# Full.net
KiCad netlist of a schematic drawn in EAGLE
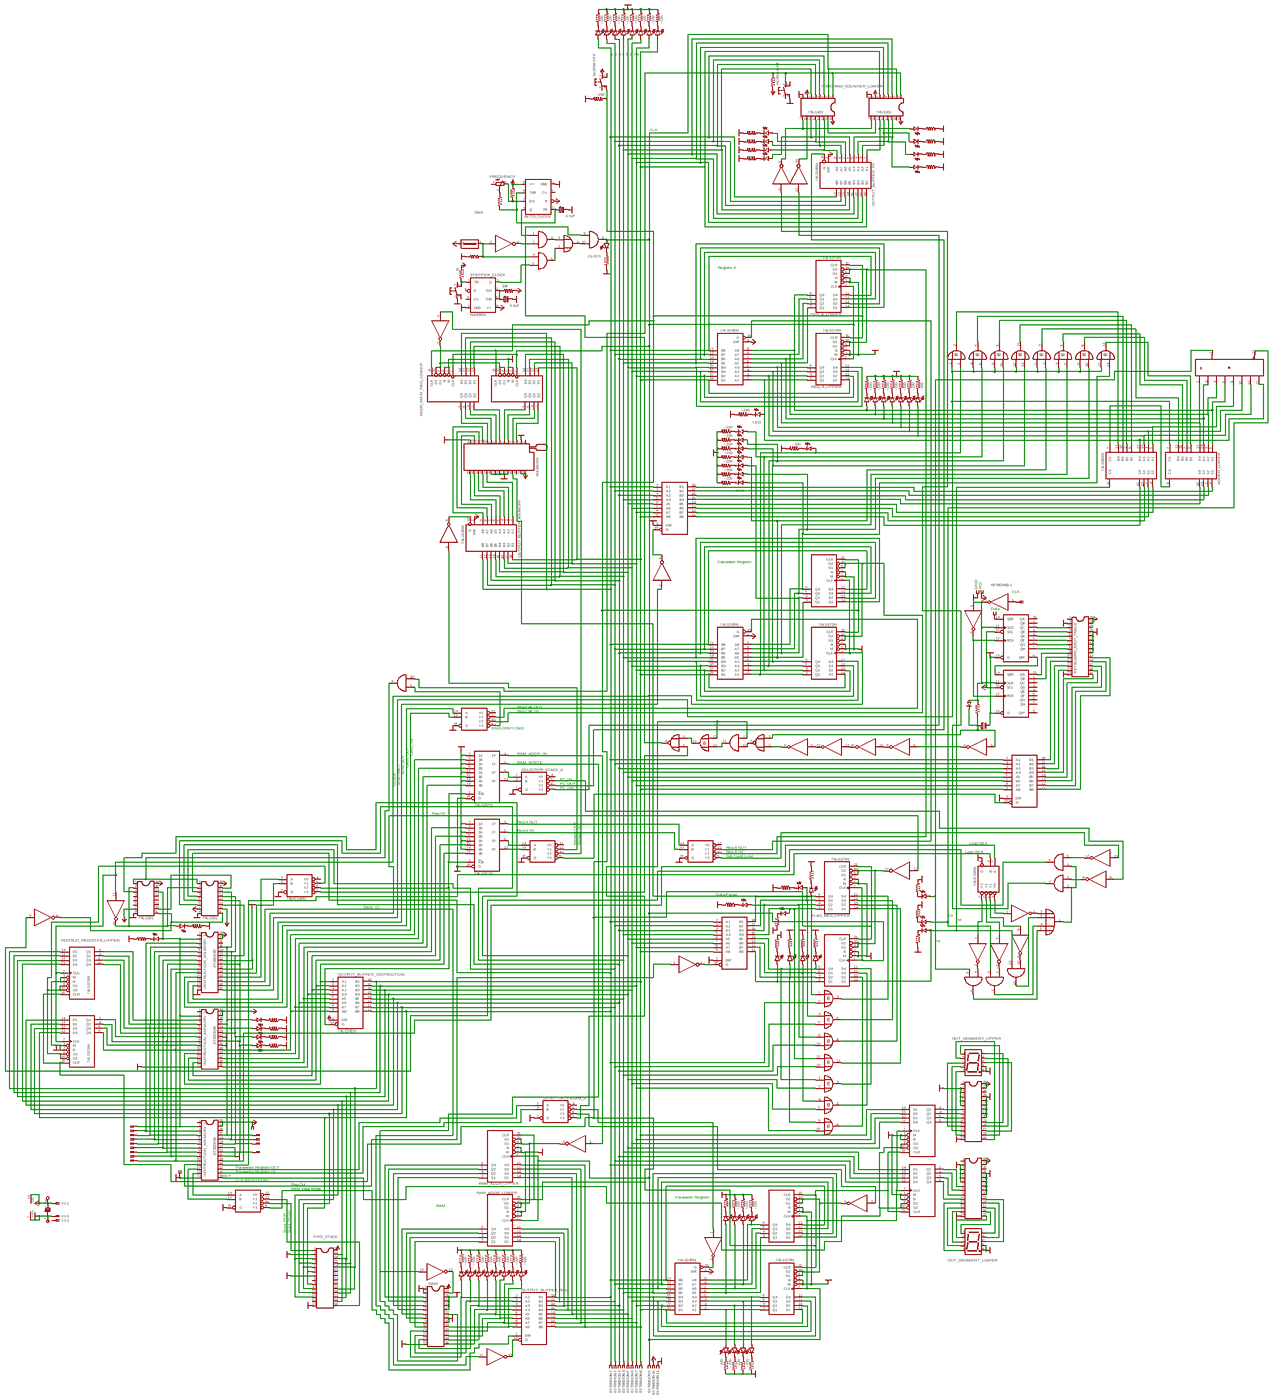
[diagram p0: schematic, sheet 1, overview]
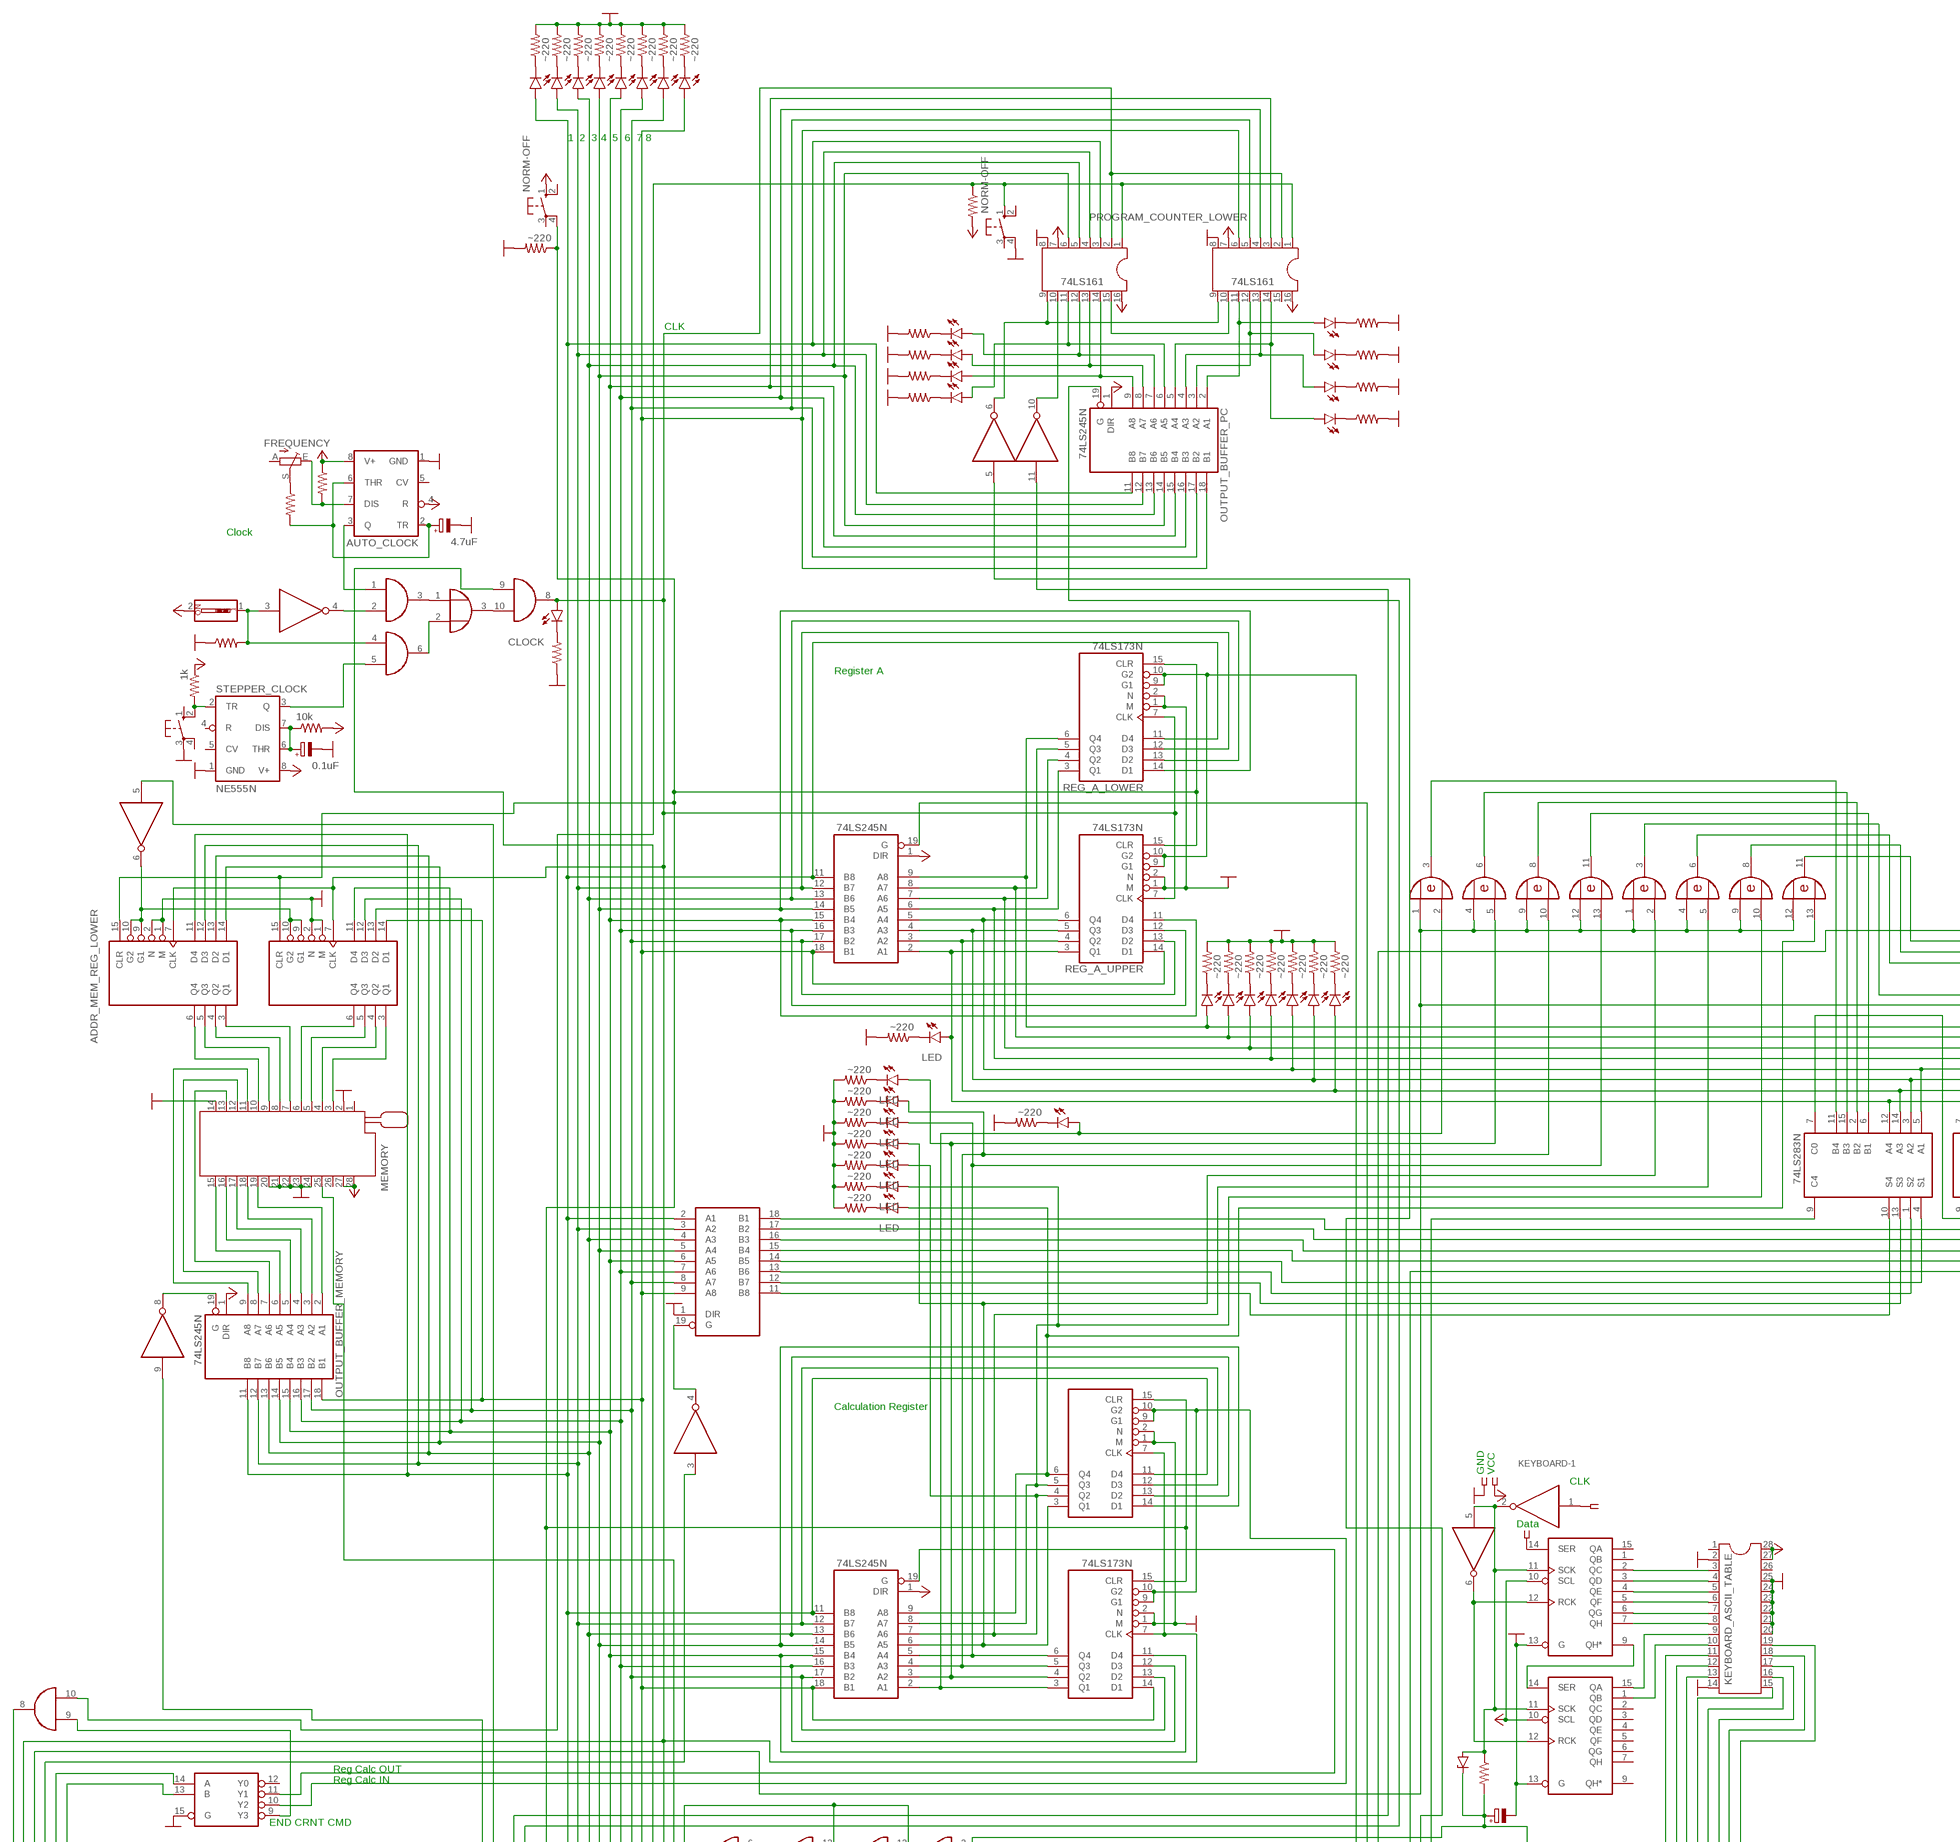
[diagram p1: schematic, sheet 1, part 1 of 4]
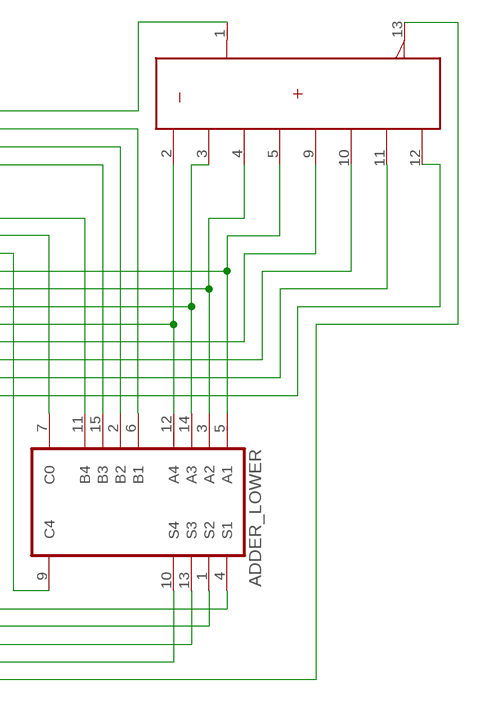
[diagram p2: schematic, sheet 1, part 2 of 4]
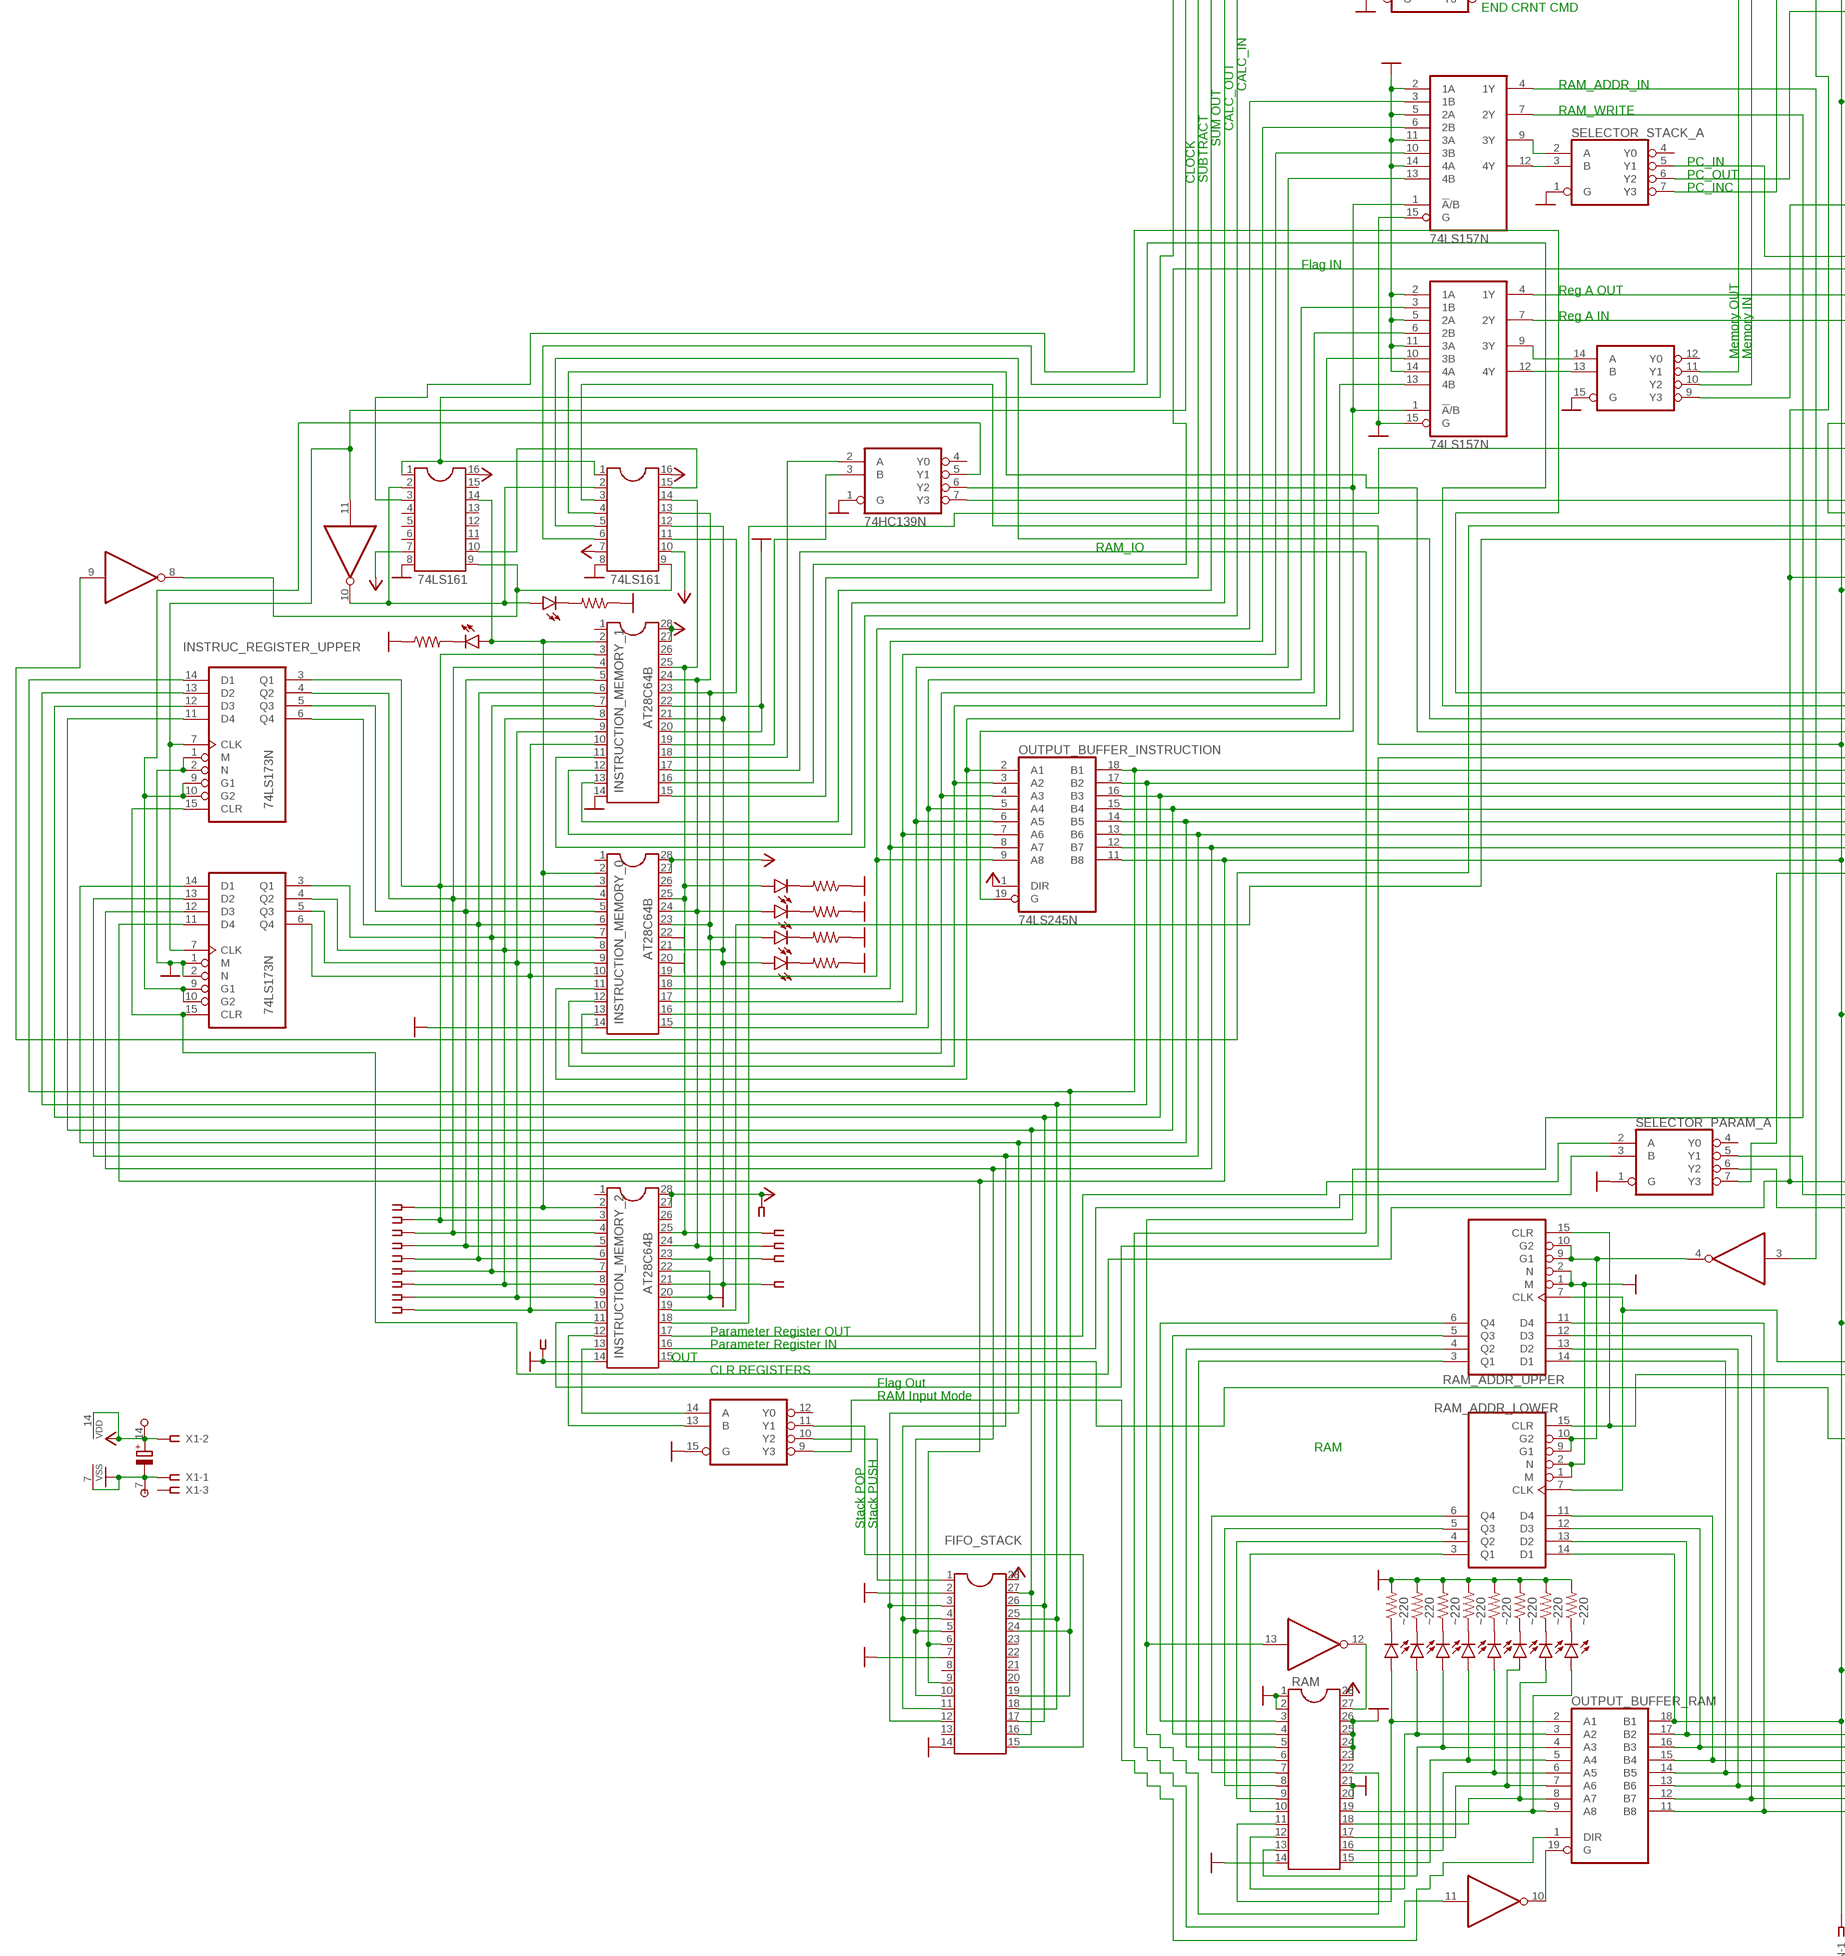
[diagram p3: schematic, sheet 1, part 3 of 4]
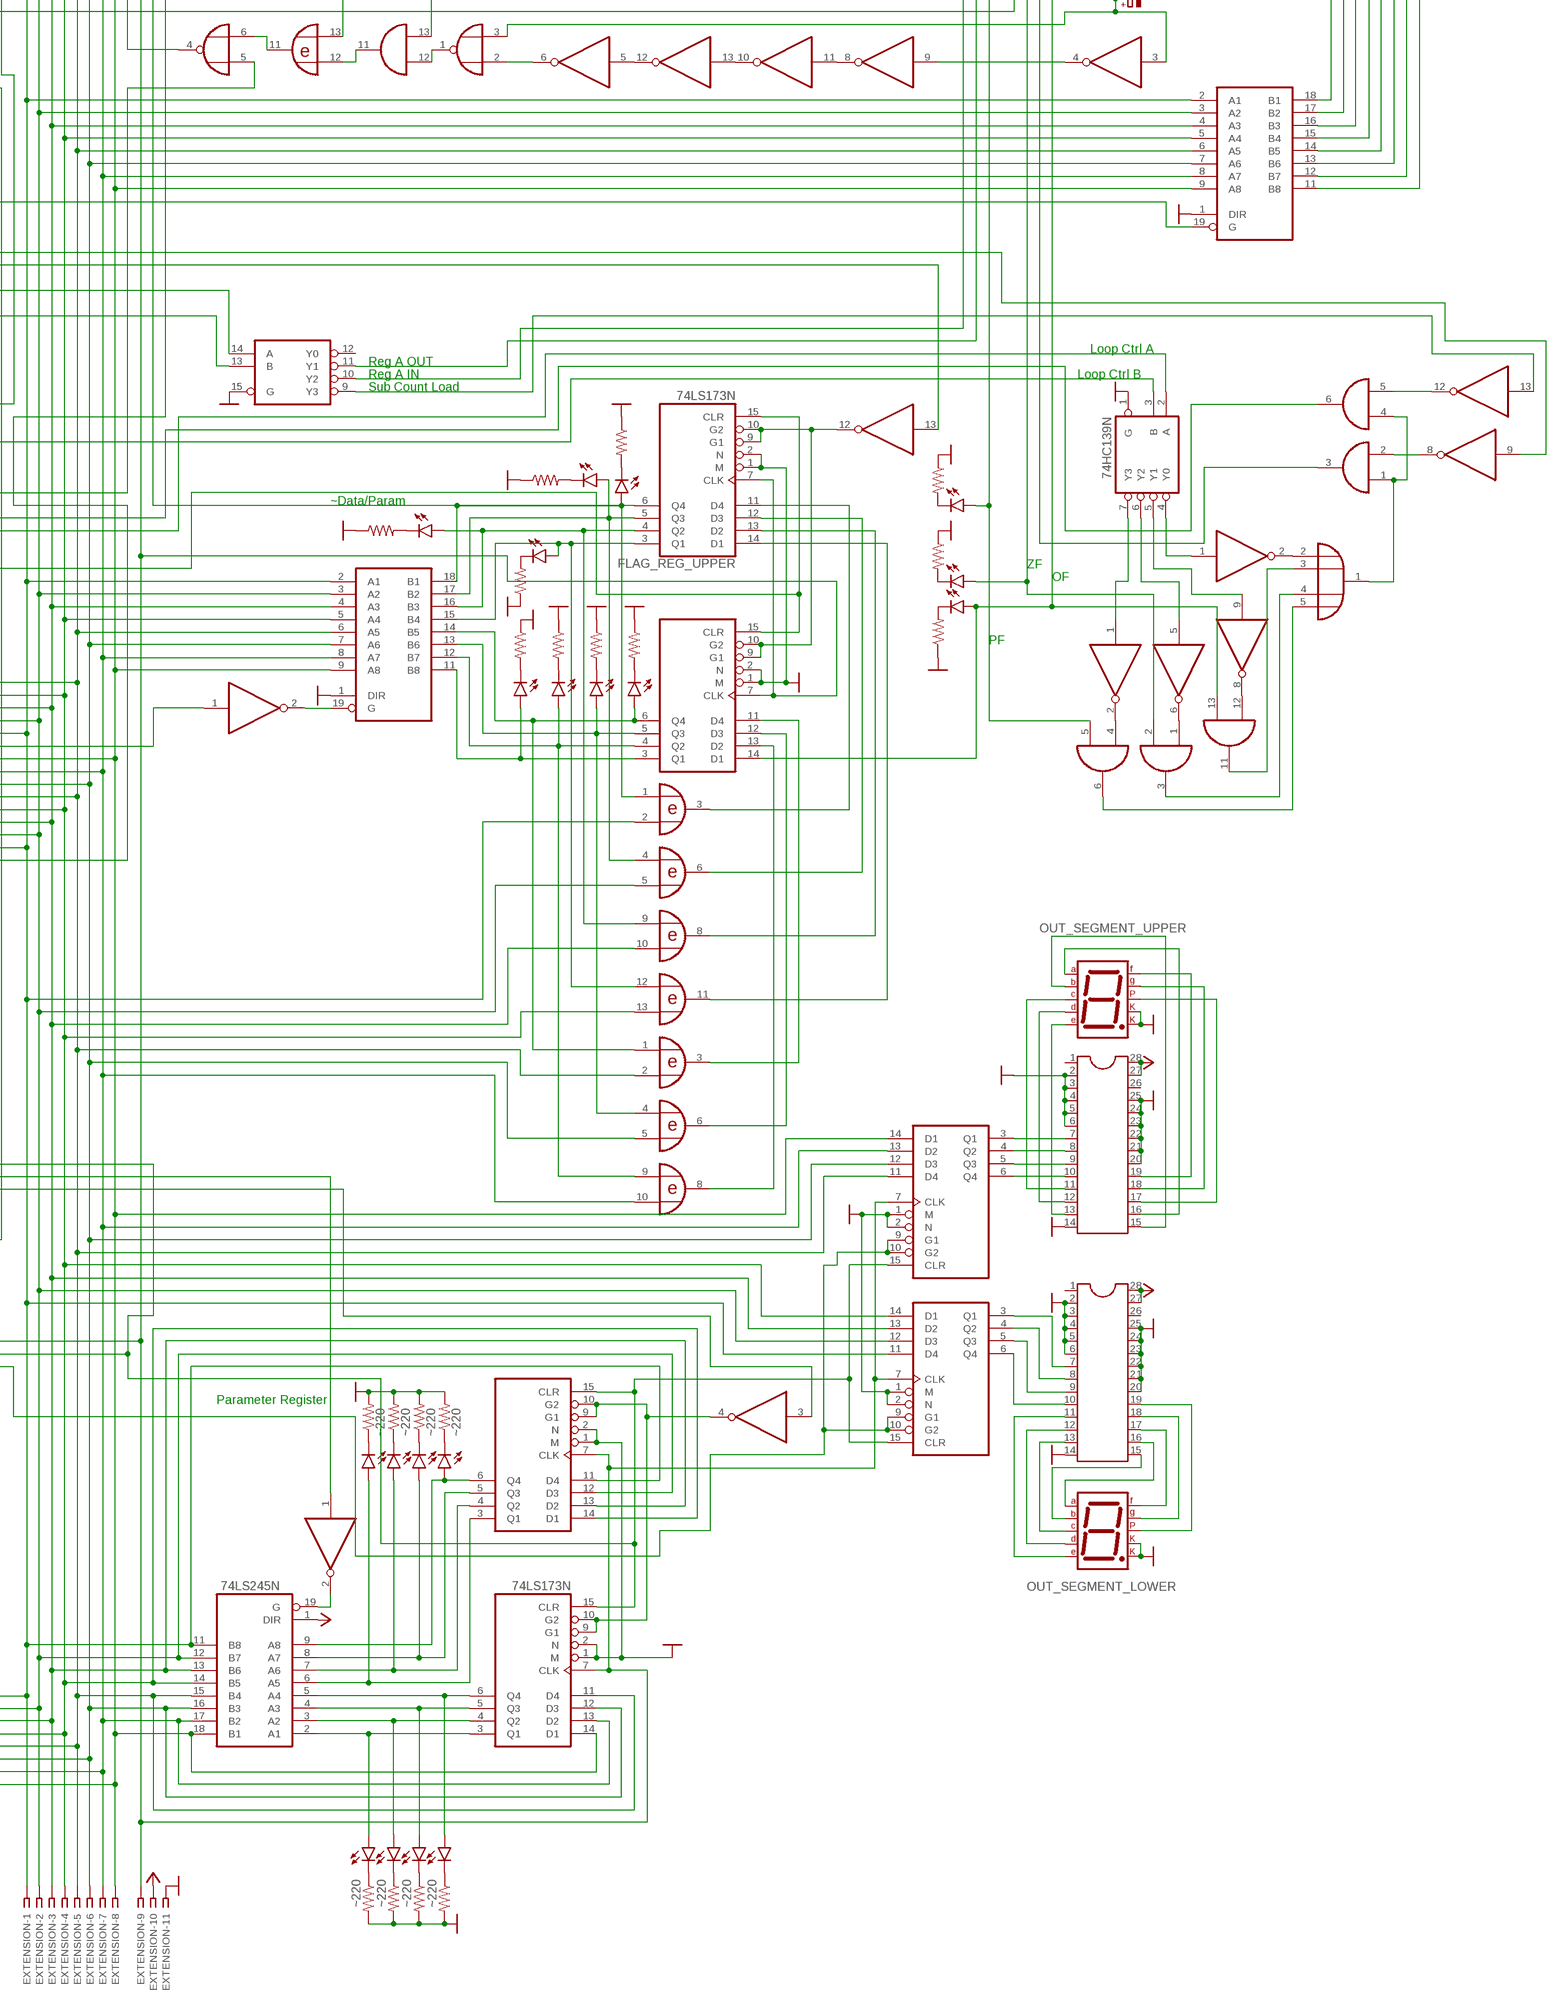
[diagram p4: schematic, sheet 1, part 4 of 4]

(export (version "E")
  (design (tool "Eeschema 10.0.6"))
  (components
    (comp (ref "4_INP_OR_GATE")
      (value "4072N")
      (footprint "eagle-import:DIL14")
      (libsource (lib "eagle-import") (part "4072N"))
    )
    (comp (ref "ADDER_LOWER")
      (value "74LS283N")
      (footprint "eagle-import:DIL16")
      (libsource (lib "eagle-import") (part "74283NLS"))
    )
    (comp (ref "ADDER_UPPER")
      (value "74LS283N")
      (footprint "eagle-import:DIL16")
      (libsource (lib "eagle-import") (part "74283NLS"))
    )
    (comp (ref "ADDR_MEM_REG_LOWER")
      (value "74LS173N")
      (footprint "eagle-import:DIL16")
      (libsource (lib "eagle-import") (part "74173NLS"))
    )
    (comp (ref "ADDR_MEM_REG_UPPER")
      (value "74LS173N")
      (footprint "eagle-import:DIL16")
      (libsource (lib "eagle-import") (part "74173NLS"))
    )
    (comp (ref "AND_GATE3_")
      (value "74LS08N")
      (footprint "eagle-import:DIL14")
      (libsource (lib "eagle-import") (part "7408NLS"))
    )
    (comp (ref "AND_GATE4_")
      (value "74LS08N")
      (footprint "eagle-import:DIL14")
      (libsource (lib "eagle-import") (part "7408NLS"))
    )
    (comp (ref "AND_GATE_")
      (value "74LS08N")
      (footprint "eagle-import:DIL14")
      (libsource (lib "eagle-import") (part "7408NLS"))
    )
    (comp (ref "AUTO_CLOCK")
      (value "NE555N")
      (footprint "eagle-import:DIL08")
      (libsource (lib "eagle-import") (part "555NNE"))
    )
    (comp (ref "C1")
      (value "4.7uF")
      (footprint "eagle-import:E2-5")
      (libsource (lib "eagle-import") (part "CPOL-EUE2-5"))
    )
    (comp (ref "C2")
      (value "0.1uF")
      (footprint "eagle-import:E2-5")
      (libsource (lib "eagle-import") (part "CPOL-EUE2-5"))
    )
    (comp (ref "C3")
      (value "0.1uF")
      (footprint "eagle-import:E2-5")
      (libsource (lib "eagle-import") (part "CPOL-EUE2-5"))
    )
    (comp (ref "C4")
      (value "0.1uF")
      (footprint "eagle-import:E2-5")
      (libsource (lib "eagle-import") (part "CPOL-EUE2-5"))
    )
    (comp (ref "CLK_MODE")
      (value "SWITCH")
      (footprint "eagle-import:EDG-01")
      (libsource (lib "eagle-import") (part "SW_DIP-1"))
    )
    (comp (ref "CLK_TRIGGER")
      (value "SWITCH")
      (footprint "eagle-import:B3F-10XX")
      (fields (field (name "MPN") "B3F-1000"))
      (libsource (lib "eagle-import") (part "10-XX"))
    )
    (comp (ref "CLOCK")
      (value "Yellow")
      (footprint "eagle-import:LED5MM")
      (libsource (lib "eagle-import") (part "LED5MM"))
    )
    (comp (ref "D1")
      (value "1N4728")
      (footprint "eagle-import:DO41Z10")
      (libsource (lib "eagle-import") (part "1N4728"))
    )
    (comp (ref "DATABUS_1")
      (value "LED")
      (footprint "eagle-import:LED5MM")
      (libsource (lib "eagle-import") (part "LED5MM"))
    )
    (comp (ref "DATABUS_2")
      (value "LED")
      (footprint "eagle-import:LED5MM")
      (libsource (lib "eagle-import") (part "LED5MM"))
    )
    (comp (ref "DATABUS_3")
      (value "LED")
      (footprint "eagle-import:LED5MM")
      (libsource (lib "eagle-import") (part "LED5MM"))
    )
    (comp (ref "DATABUS_4")
      (value "LED")
      (footprint "eagle-import:LED5MM")
      (libsource (lib "eagle-import") (part "LED5MM"))
    )
    (comp (ref "DATABUS_5")
      (value "LED")
      (footprint "eagle-import:LED5MM")
      (libsource (lib "eagle-import") (part "LED5MM"))
    )
    (comp (ref "DATABUS_6")
      (value "LED")
      (footprint "eagle-import:LED5MM")
      (libsource (lib "eagle-import") (part "LED5MM"))
    )
    (comp (ref "DATABUS_7")
      (value "LED")
      (footprint "eagle-import:LED5MM")
      (libsource (lib "eagle-import") (part "LED5MM"))
    )
    (comp (ref "DATABUS_8")
      (value "LED")
      (footprint "eagle-import:LED5MM")
      (libsource (lib "eagle-import") (part "LED5MM"))
    )
    (comp (ref "EXTENSION")
      (value "SSW-111-02-G-S")
      (footprint "eagle-import:SSW-111-02-G-S")
      (fields (field (name "MF") "Samtec Inc."))
      (libsource (lib "eagle-import") (part "SSW-111-02-G-S"))
    )
    (comp (ref "FIFO_STACK")
      (value "71256SA15TPG")
      (footprint "eagle-import:DIL28-3")
      (libsource (lib "eagle-import") (part "DIL28-3"))
    )
    (comp (ref "FLAG_1")
      (value "LED")
      (footprint "eagle-import:LED5MM")
      (libsource (lib "eagle-import") (part "LED5MM"))
    )
    (comp (ref "FLAG_2")
      (value "LED")
      (footprint "eagle-import:LED5MM")
      (libsource (lib "eagle-import") (part "LED5MM"))
    )
    (comp (ref "FLAG_3")
      (value "LED")
      (footprint "eagle-import:LED5MM")
      (libsource (lib "eagle-import") (part "LED5MM"))
    )
    (comp (ref "FLAG_4")
      (value "LED")
      (footprint "eagle-import:LED5MM")
      (libsource (lib "eagle-import") (part "LED5MM"))
    )
    (comp (ref "FLAG_5")
      (value "LED")
      (footprint "eagle-import:LED5MM")
      (libsource (lib "eagle-import") (part "LED5MM"))
    )
    (comp (ref "FLAG_6")
      (value "LED")
      (footprint "eagle-import:LED5MM")
      (libsource (lib "eagle-import") (part "LED5MM"))
    )
    (comp (ref "FLAG_7")
      (value "LED")
      (footprint "eagle-import:LED5MM")
      (libsource (lib "eagle-import") (part "LED5MM"))
    )
    (comp (ref "FLAG_8")
      (value "LED")
      (footprint "eagle-import:LED5MM")
      (libsource (lib "eagle-import") (part "LED5MM"))
    )
    (comp (ref "FLAG_REG_LOWER")
      (value "74LS173N")
      (footprint "eagle-import:DIL16")
      (libsource (lib "eagle-import") (part "74173NLS"))
    )
    (comp (ref "FLAG_REG_UPPER")
      (value "74LS173N")
      (footprint "eagle-import:DIL16")
      (libsource (lib "eagle-import") (part "74173NLS"))
    )
    (comp (ref "FREQUENCY")
      (value "100k")
      (footprint "eagle-import:RJ9W")
      (libsource (lib "eagle-import") (part "TRIM_EU-RJ9W"))
    )
    (comp (ref "INSTRUCTIONS_EXTENSION")
      (value "SSW-115-02-G-S")
      (footprint "eagle-import:SSW-115-02-G-S")
      (fields (field (name "MF") "Samtec Inc."))
      (libsource (lib "eagle-import") (part "SSW-115-02-G-S"))
    )
    (comp (ref "INSTRUCTION_MEMORY_0")
      (value "AT28C64B")
      (footprint "eagle-import:DIL28-6")
      (libsource (lib "eagle-import") (part "DIL28"))
    )
    (comp (ref "INSTRUCTION_MEMORY_1")
      (value "AT28C64B")
      (footprint "eagle-import:DIL28-6")
      (libsource (lib "eagle-import") (part "DIL28"))
    )
    (comp (ref "INSTRUCTION_MEMORY_2")
      (value "AT28C64B")
      (footprint "eagle-import:DIL28-6")
      (libsource (lib "eagle-import") (part "DIL28"))
    )
    (comp (ref "INSTRUC_REGISTER_LOWER")
      (value "74LS173N")
      (footprint "eagle-import:DIL16")
      (libsource (lib "eagle-import") (part "74173NLS"))
    )
    (comp (ref "INSTRUC_REGISTER_UPPER")
      (value "74LS173N")
      (footprint "eagle-import:DIL16")
      (libsource (lib "eagle-import") (part "74173NLS"))
    )
    (comp (ref "INVERTED_CLK_LED")
      (value "LED")
      (footprint "eagle-import:LED5MM")
      (libsource (lib "eagle-import") (part "LED5MM"))
    )
    (comp (ref "KEYBOARD")
      (value "SSW-104-02-G-S")
      (footprint "eagle-import:SSW-104-02-G-S")
      (fields (field (name "MF") "Samtec Inc."))
      (libsource (lib "eagle-import") (part "SSW-104-02-G-S"))
    )
    (comp (ref "KEYBOARD_ASCII_TABLE")
      (value "AT28C64B")
      (footprint "eagle-import:DIL28-6")
      (libsource (lib "eagle-import") (part "DIL28"))
    )
    (comp (ref "KEYBOARD_SHIFT_LOWER")
      (value "74LS595N")
      (footprint "eagle-import:DIL16")
      (libsource (lib "eagle-import") (part "74595NLS"))
    )
    (comp (ref "KEYBOARD_SHIFT_UPPER")
      (value "74LS595N")
      (footprint "eagle-import:DIL16")
      (libsource (lib "eagle-import") (part "74595NLS"))
    )
    (comp (ref "LED_A_REG_1")
      (value "LED")
      (footprint "eagle-import:LED5MM")
      (libsource (lib "eagle-import") (part "LED5MM"))
    )
    (comp (ref "LED_A_REG_2")
      (value "LED")
      (footprint "eagle-import:LED5MM")
      (libsource (lib "eagle-import") (part "LED5MM"))
    )
    (comp (ref "LED_A_REG_3")
      (value "LED")
      (footprint "eagle-import:LED5MM")
      (libsource (lib "eagle-import") (part "LED5MM"))
    )
    (comp (ref "LED_A_REG_4")
      (value "LED")
      (footprint "eagle-import:LED5MM")
      (libsource (lib "eagle-import") (part "LED5MM"))
    )
    (comp (ref "LED_A_REG_5")
      (value "LED")
      (footprint "eagle-import:LED5MM")
      (libsource (lib "eagle-import") (part "LED5MM"))
    )
    (comp (ref "LED_A_REG_6")
      (value "LED")
      (footprint "eagle-import:LED5MM")
      (libsource (lib "eagle-import") (part "LED5MM"))
    )
    (comp (ref "LED_A_REG_7")
      (value "LED")
      (footprint "eagle-import:LED5MM")
      (libsource (lib "eagle-import") (part "LED5MM"))
    )
    (comp (ref "LED_A_REG_8")
      (value "LED")
      (footprint "eagle-import:LED5MM")
      (libsource (lib "eagle-import") (part "LED5MM"))
    )
    (comp (ref "LED_B_REG_1")
      (value "LED")
      (footprint "eagle-import:LED5MM")
      (libsource (lib "eagle-import") (part "LED5MM"))
    )
    (comp (ref "LED_B_REG_2")
      (value "LED")
      (footprint "eagle-import:LED5MM")
      (libsource (lib "eagle-import") (part "LED5MM"))
    )
    (comp (ref "LED_B_REG_3")
      (value "LED")
      (footprint "eagle-import:LED5MM")
      (libsource (lib "eagle-import") (part "LED5MM"))
    )
    (comp (ref "LED_B_REG_4")
      (value "LED")
      (footprint "eagle-import:LED5MM")
      (libsource (lib "eagle-import") (part "LED5MM"))
    )
    (comp (ref "LED_B_REG_5")
      (value "LED")
      (footprint "eagle-import:LED5MM")
      (libsource (lib "eagle-import") (part "LED5MM"))
    )
    (comp (ref "LED_B_REG_6")
      (value "LED")
      (footprint "eagle-import:LED5MM")
      (libsource (lib "eagle-import") (part "LED5MM"))
    )
    (comp (ref "LED_B_REG_7")
      (value "LED")
      (footprint "eagle-import:LED5MM")
      (libsource (lib "eagle-import") (part "LED5MM"))
    )
    (comp (ref "LED_B_REG_8")
      (value "LED")
      (footprint "eagle-import:LED5MM")
      (libsource (lib "eagle-import") (part "LED5MM"))
    )
    (comp (ref "MEMORY")
      (value "228-1277-00-0602J")
      (footprint "eagle-import:228-1277-00-0602J")
      (fields (field (name "MF") "3M"))
      (libsource (lib "eagle-import") (part "228-?00-0602J1277-"))
    )
    (comp (ref "MICRO_COUNTER_LOWER")
      (value "74LS161")
      (footprint "eagle-import:DIL16")
      (libsource (lib "eagle-import") (part "DIL16"))
    )
    (comp (ref "MICRO_COUNTER_UPPER")
      (value "74LS161")
      (footprint "eagle-import:DIL16")
      (libsource (lib "eagle-import") (part "DIL16"))
    )
    (comp (ref "NOR_GATE_")
      (value "74LS02N")
      (footprint "eagle-import:DIL14")
      (libsource (lib "eagle-import") (part "7402NLS"))
    )
    (comp (ref "NOT_GATE1_")
      (value "74LS04N")
      (footprint "eagle-import:DIL14")
      (libsource (lib "eagle-import") (part "7404NLS"))
    )
    (comp (ref "NOT_GATE2_")
      (value "74LS04N")
      (footprint "eagle-import:DIL14")
      (libsource (lib "eagle-import") (part "7404NLS"))
    )
    (comp (ref "NOT_GATE3_")
      (value "74LS04N")
      (footprint "eagle-import:DIL14")
      (libsource (lib "eagle-import") (part "7404NLS"))
    )
    (comp (ref "NOT_GATE4_")
      (value "74LS04N")
      (footprint "eagle-import:DIL14")
      (fields (field (name "SPICEPREFIX") "B"))
      (libsource (lib "eagle-import") (part "7404NLS"))
    )
    (comp (ref "NOT_GATE_")
      (value "74LS04N")
      (footprint "eagle-import:DIL14")
      (libsource (lib "eagle-import") (part "7404NLS"))
    )
    (comp (ref "OR_GATE_")
      (value "74LS32N")
      (footprint "eagle-import:DIL14")
      (libsource (lib "eagle-import") (part "7432NLS"))
    )
    (comp (ref "OUTPUT_BUFFER_ALU")
      (value "74LS245N")
      (footprint "eagle-import:DIL20")
      (libsource (lib "eagle-import") (part "74245NLS"))
    )
    (comp (ref "OUTPUT_BUFFER_CALC_REG")
      (value "74LS245N")
      (footprint "eagle-import:DIL20")
      (libsource (lib "eagle-import") (part "74245NLS"))
    )
    (comp (ref "OUTPUT_BUFFER_FLAGS")
      (value "74HC245N")
      (footprint "eagle-import:DIL20")
      (libsource (lib "eagle-import") (part "74245NHC"))
    )
    (comp (ref "OUTPUT_BUFFER_INSTRUCTION")
      (value "74LS245N")
      (footprint "eagle-import:DIL20")
      (libsource (lib "eagle-import") (part "74xx-us_88_74245NLS"))
    )
    (comp (ref "OUTPUT_BUFFER_KEYBOARD")
      (value "74LS245N")
      (footprint "eagle-import:DIL20")
      (libsource (lib "eagle-import") (part "74245NLS"))
    )
    (comp (ref "OUTPUT_BUFFER_MEMORY")
      (value "74LS245N")
      (footprint "eagle-import:DIL20")
      (libsource (lib "eagle-import") (part "74245NLS"))
    )
    (comp (ref "OUTPUT_BUFFER_PARAM_REG")
      (value "74LS245N")
      (footprint "eagle-import:DIL20")
      (libsource (lib "eagle-import") (part "74245NLS"))
    )
    (comp (ref "OUTPUT_BUFFER_PC")
      (value "74LS245N")
      (footprint "eagle-import:DIL20")
      (libsource (lib "eagle-import") (part "74245NLS"))
    )
    (comp (ref "OUTPUT_BUFFER_RAM")
      (value "74HC245N")
      (footprint "eagle-import:DIL20")
      (libsource (lib "eagle-import") (part "74245NHC"))
    )
    (comp (ref "OUTPUT_BUFFER_REG_A")
      (value "74LS245N")
      (footprint "eagle-import:DIL20")
      (libsource (lib "eagle-import") (part "74245NLS"))
    )
    (comp (ref "OUT_REG_LOWER")
      (value "74LS173N")
      (footprint "eagle-import:DIL16")
      (libsource (lib "eagle-import") (part "74173NLS"))
    )
    (comp (ref "OUT_REG_UPPER")
      (value "74LS173N")
      (footprint "eagle-import:DIL16")
      (libsource (lib "eagle-import") (part "74173NLS"))
    )
    (comp (ref "OUT_ROM_LOWER")
      (value "AT28C64B")
      (footprint "eagle-import:DIL28-6")
      (libsource (lib "eagle-import") (part "DIL28"))
    )
    (comp (ref "OUT_ROM_UPPER")
      (value "AT28C64B")
      (footprint "eagle-import:DIL28-6")
      (libsource (lib "eagle-import") (part "DIL28"))
    )
    (comp (ref "OUT_SEGMENT_LOWER")
      (value "LED")
      (footprint "eagle-import:7SEG-13")
      (libsource (lib "eagle-import") (part "7SEG-CK"))
    )
    (comp (ref "OUT_SEGMENT_UPPER")
      (value "LED")
      (footprint "eagle-import:7SEG-13")
      (libsource (lib "eagle-import") (part "7SEG-CK"))
    )
    (comp (ref "OVERFLOW_FLAG")
      (value "LED")
      (footprint "eagle-import:LED5MM")
      (libsource (lib "eagle-import") (part "LED5MM"))
    )
    (comp (ref "PARAM_LED_1")
      (value "LED3MM")
      (footprint "eagle-import:LED3MM")
      (libsource (lib "eagle-import") (part "LED3MM"))
    )
    (comp (ref "PARAM_LED_2")
      (value "LED3MM")
      (footprint "eagle-import:LED3MM")
      (libsource (lib "eagle-import") (part "LED3MM"))
    )
    (comp (ref "PARAM_LED_3")
      (value "LED3MM")
      (footprint "eagle-import:LED3MM")
      (libsource (lib "eagle-import") (part "LED3MM"))
    )
    (comp (ref "PARAM_LED_4")
      (value "LED3MM")
      (footprint "eagle-import:LED3MM")
      (libsource (lib "eagle-import") (part "LED3MM"))
    )
    (comp (ref "PARAM_LED_5")
      (value "LED3MM")
      (footprint "eagle-import:LED3MM")
      (libsource (lib "eagle-import") (part "LED3MM"))
    )
    (comp (ref "PARAM_LED_6")
      (value "LED3MM")
      (footprint "eagle-import:LED3MM")
      (libsource (lib "eagle-import") (part "LED3MM"))
    )
    (comp (ref "PARAM_LED_7")
      (value "LED3MM")
      (footprint "eagle-import:LED3MM")
      (libsource (lib "eagle-import") (part "LED3MM"))
    )
    (comp (ref "PARAM_LED_8")
      (value "LED3MM")
      (footprint "eagle-import:LED3MM")
      (libsource (lib "eagle-import") (part "LED3MM"))
    )
    (comp (ref "PC_1")
      (value "LED5MM")
      (footprint "eagle-import:LED5MM")
      (libsource (lib "eagle-import") (part "LED5MM"))
    )
    (comp (ref "PC_2")
      (value "LED5MM")
      (footprint "eagle-import:LED5MM")
      (libsource (lib "eagle-import") (part "LED5MM"))
    )
    (comp (ref "PC_3")
      (value "LED5MM")
      (footprint "eagle-import:LED5MM")
      (libsource (lib "eagle-import") (part "LED5MM"))
    )
    (comp (ref "PC_4")
      (value "LED5MM")
      (footprint "eagle-import:LED5MM")
      (libsource (lib "eagle-import") (part "LED5MM"))
    )
    (comp (ref "PC_5")
      (value "LED5MM")
      (footprint "eagle-import:LED5MM")
      (libsource (lib "eagle-import") (part "LED5MM"))
    )
    (comp (ref "PC_6")
      (value "LED5MM")
      (footprint "eagle-import:LED5MM")
      (libsource (lib "eagle-import") (part "LED5MM"))
    )
    (comp (ref "PC_7")
      (value "LED5MM")
      (footprint "eagle-import:LED5MM")
      (libsource (lib "eagle-import") (part "LED5MM"))
    )
    (comp (ref "PC_8")
      (value "LED5MM")
      (footprint "eagle-import:LED5MM")
      (libsource (lib "eagle-import") (part "LED5MM"))
    )
    (comp (ref "POSITIVE_FLAG")
      (value "LED")
      (footprint "eagle-import:LED5MM")
      (libsource (lib "eagle-import") (part "LED5MM"))
    )
    (comp (ref "PROGRAM_COUNTER_LOWER")
      (value "74LS161")
      (footprint "eagle-import:DIL16")
      (libsource (lib "eagle-import") (part "DIL16"))
    )
    (comp (ref "PROGRAM_COUNTER_UPPER")
      (value "74LS161")
      (footprint "eagle-import:DIL16")
      (libsource (lib "eagle-import") (part "DIL16"))
    )
    (comp (ref "R1")
      (value "1k")
      (footprint "eagle-import:0204_7")
      (libsource (lib "eagle-import") (part "R-US_0204/7"))
    )
    (comp (ref "R2")
      (value "1k")
      (footprint "eagle-import:0204_7")
      (libsource (lib "eagle-import") (part "R-US_0204/7"))
    )
    (comp (ref "R3")
      (value "10k")
      (footprint "eagle-import:0204_7")
      (libsource (lib "eagle-import") (part "R-US_0204/7"))
    )
    (comp (ref "R4")
      (value "220")
      (footprint "eagle-import:0204_7")
      (libsource (lib "eagle-import") (part "R-US_0204/7"))
    )
    (comp (ref "R5")
      (value "~220")
      (footprint "eagle-import:0204_7")
      (libsource (lib "eagle-import") (part "R-US_0204/7"))
    )
    (comp (ref "R6")
      (value "~220")
      (footprint "eagle-import:0204_7")
      (libsource (lib "eagle-import") (part "R-US_0204/7"))
    )
    (comp (ref "R7")
      (value "220")
      (footprint "eagle-import:0204_7")
      (libsource (lib "eagle-import") (part "R-US_0204/7"))
    )
    (comp (ref "R8")
      (value "~220")
      (footprint "eagle-import:0204_7")
      (libsource (lib "eagle-import") (part "R-US_0204/7"))
    )
    (comp (ref "R9")
      (value "~220")
      (footprint "eagle-import:0204_7")
      (libsource (lib "eagle-import") (part "R-US_0204/7"))
    )
    (comp (ref "R10")
      (value "~220")
      (footprint "eagle-import:0204_7")
      (libsource (lib "eagle-import") (part "R-US_0204/7"))
    )
    (comp (ref "R11")
      (value "~220")
      (footprint "eagle-import:0204_7")
      (libsource (lib "eagle-import") (part "R-US_0204/7"))
    )
    (comp (ref "R12")
      (value "~220")
      (footprint "eagle-import:0204_7")
      (libsource (lib "eagle-import") (part "R-US_0204/7"))
    )
    (comp (ref "R13")
      (value "~220")
      (footprint "eagle-import:0204_7")
      (libsource (lib "eagle-import") (part "R-US_0204/7"))
    )
    (comp (ref "R14")
      (value "~220")
      (footprint "eagle-import:0204_7")
      (libsource (lib "eagle-import") (part "R-US_0204/7"))
    )
    (comp (ref "R15")
      (value "~220")
      (footprint "eagle-import:0204_7")
      (libsource (lib "eagle-import") (part "R-US_0204/7"))
    )
    (comp (ref "R16")
      (value "~220")
      (footprint "eagle-import:0204_7")
      (libsource (lib "eagle-import") (part "R-US_0204/7"))
    )
    (comp (ref "R17")
      (value "~220")
      (footprint "eagle-import:0204_7")
      (libsource (lib "eagle-import") (part "R-US_0204/7"))
    )
    (comp (ref "R18")
      (value "~220")
      (footprint "eagle-import:0204_7")
      (libsource (lib "eagle-import") (part "R-US_0204/7"))
    )
    (comp (ref "R19")
      (value "~220")
      (footprint "eagle-import:0204_7")
      (libsource (lib "eagle-import") (part "R-US_0204/7"))
    )
    (comp (ref "R20")
      (value "~220")
      (footprint "eagle-import:0204_7")
      (libsource (lib "eagle-import") (part "R-US_0204/7"))
    )
    (comp (ref "R21")
      (value "~220")
      (footprint "eagle-import:0204_7")
      (libsource (lib "eagle-import") (part "R-US_0204/7"))
    )
    (comp (ref "R22")
      (value "~220")
      (footprint "eagle-import:0204_7")
      (libsource (lib "eagle-import") (part "R-US_0204/7"))
    )
    (comp (ref "R23")
      (value "~220")
      (footprint "eagle-import:0204_7")
      (libsource (lib "eagle-import") (part "R-US_0204/7"))
    )
    (comp (ref "R24")
      (value "~220")
      (footprint "eagle-import:0204_7")
      (libsource (lib "eagle-import") (part "R-US_0204/7"))
    )
    (comp (ref "R25")
      (value "~220")
      (footprint "eagle-import:0204_7")
      (libsource (lib "eagle-import") (part "R-US_0204/7"))
    )
    (comp (ref "R26")
      (value "~220")
      (footprint "eagle-import:0204_7")
      (libsource (lib "eagle-import") (part "R-US_0204/7"))
    )
    (comp (ref "R27")
      (value "~220")
      (footprint "eagle-import:0204_7")
      (libsource (lib "eagle-import") (part "R-US_0204/7"))
    )
    (comp (ref "R28")
      (value "~220")
      (footprint "eagle-import:0204_7")
      (libsource (lib "eagle-import") (part "R-US_0204/7"))
    )
    (comp (ref "R29")
      (value "~220")
      (footprint "eagle-import:0204_7")
      (libsource (lib "eagle-import") (part "R-US_0204/7"))
    )
    (comp (ref "R30")
      (value "~220")
      (footprint "eagle-import:0204_7")
      (libsource (lib "eagle-import") (part "R-US_0204/7"))
    )
    (comp (ref "R31")
      (value "~220")
      (footprint "eagle-import:0204_7")
      (libsource (lib "eagle-import") (part "R-US_0204/7"))
    )
    (comp (ref "R32")
      (value "~220")
      (footprint "eagle-import:0204_7")
      (libsource (lib "eagle-import") (part "R-US_0204/7"))
    )
    (comp (ref "R33")
      (value "~220")
      (footprint "eagle-import:0204_7")
      (libsource (lib "eagle-import") (part "R-US_0204/7"))
    )
    (comp (ref "R34")
      (value "~220")
      (footprint "eagle-import:0204_7")
      (libsource (lib "eagle-import") (part "R-US_0204/7"))
    )
    (comp (ref "R35")
      (value "~220")
      (footprint "eagle-import:0204_7")
      (libsource (lib "eagle-import") (part "R-US_0204/7"))
    )
    (comp (ref "R36")
      (value "~220")
      (footprint "eagle-import:0204_7")
      (libsource (lib "eagle-import") (part "R-US_0204/7"))
    )
    (comp (ref "R37")
      (value "~220")
      (footprint "eagle-import:0204_7")
      (libsource (lib "eagle-import") (part "R-US_0204/7"))
    )
    (comp (ref "R38")
      (value "~220")
      (footprint "eagle-import:0204_7")
      (libsource (lib "eagle-import") (part "R-US_0204/7"))
    )
    (comp (ref "R39")
      (value "~220")
      (footprint "eagle-import:0204_7")
      (libsource (lib "eagle-import") (part "R-US_0204/7"))
    )
    (comp (ref "R40")
      (value "~220")
      (footprint "eagle-import:0204_7")
      (libsource (lib "eagle-import") (part "R-US_0204/7"))
    )
    (comp (ref "R41")
      (value "~220")
      (footprint "eagle-import:0204_7")
      (libsource (lib "eagle-import") (part "R-US_0204/7"))
    )
    (comp (ref "R42")
      (value "~220")
      (footprint "eagle-import:0204_7")
      (libsource (lib "eagle-import") (part "R-US_0204/7"))
    )
    (comp (ref "R43")
      (value "~220")
      (footprint "eagle-import:0204_7")
      (libsource (lib "eagle-import") (part "R-US_0204/7"))
    )
    (comp (ref "R44")
      (value "~220")
      (footprint "eagle-import:0204_7")
      (libsource (lib "eagle-import") (part "R-US_0204/7"))
    )
    (comp (ref "R45")
      (value "~220")
      (footprint "eagle-import:0204_7")
      (libsource (lib "eagle-import") (part "R-US_0204/7"))
    )
    (comp (ref "R53")
      (value "~220")
      (footprint "eagle-import:0204_7")
      (libsource (lib "eagle-import") (part "R-US_0204/7"))
    )
    (comp (ref "R54")
      (value "~220")
      (footprint "eagle-import:0204_7")
      (libsource (lib "eagle-import") (part "R-US_0204/7"))
    )
    (comp (ref "R55")
      (value "~220")
      (footprint "eagle-import:0204_7")
      (libsource (lib "eagle-import") (part "R-US_0204/7"))
    )
    (comp (ref "R56")
      (value "~220")
      (footprint "eagle-import:0204_7")
      (libsource (lib "eagle-import") (part "R-US_0204/7"))
    )
    (comp (ref "R57")
      (value "~220")
      (footprint "eagle-import:0204_7")
      (libsource (lib "eagle-import") (part "R-US_0204/7"))
    )
    (comp (ref "R58")
      (value "~220")
      (footprint "eagle-import:0204_7")
      (libsource (lib "eagle-import") (part "R-US_0204/7"))
    )
    (comp (ref "R59")
      (value "~220")
      (footprint "eagle-import:0204_7")
      (libsource (lib "eagle-import") (part "R-US_0204/7"))
    )
    (comp (ref "R60")
      (value "~220")
      (footprint "eagle-import:0204_7")
      (libsource (lib "eagle-import") (part "R-US_0204/7"))
    )
    (comp (ref "R61")
      (value "~220")
      (footprint "eagle-import:0204_7")
      (libsource (lib "eagle-import") (part "R-US_0204/7"))
    )
    (comp (ref "R62")
      (value "~220")
      (footprint "eagle-import:0204_7")
      (libsource (lib "eagle-import") (part "R-US_0204/7"))
    )
    (comp (ref "R63")
      (value "~220")
      (footprint "eagle-import:0204_7")
      (libsource (lib "eagle-import") (part "R-US_0204/7"))
    )
    (comp (ref "R64")
      (value "~220")
      (footprint "eagle-import:0204_7")
      (libsource (lib "eagle-import") (part "R-US_0204/7"))
    )
    (comp (ref "R65")
      (value "~220")
      (footprint "eagle-import:0204_7")
      (libsource (lib "eagle-import") (part "R-US_0204/7"))
    )
    (comp (ref "R66")
      (value "~220")
      (footprint "eagle-import:0204_7")
      (libsource (lib "eagle-import") (part "R-US_0204/7"))
    )
    (comp (ref "R67")
      (value "~220")
      (footprint "eagle-import:0204_7")
      (libsource (lib "eagle-import") (part "R-US_0204/7"))
    )
    (comp (ref "R68")
      (value "~220")
      (footprint "eagle-import:0204_7")
      (libsource (lib "eagle-import") (part "R-US_0204/7"))
    )
    (comp (ref "R69")
      (value "~220")
      (footprint "eagle-import:0204_7")
      (libsource (lib "eagle-import") (part "R-US_0204/7"))
    )
    (comp (ref "R70")
      (value "~220")
      (footprint "eagle-import:0204_7")
      (libsource (lib "eagle-import") (part "R-US_0204/7"))
    )
    (comp (ref "R71")
      (value "~220")
      (footprint "eagle-import:0204_7")
      (libsource (lib "eagle-import") (part "R-US_0204/7"))
    )
    (comp (ref "R72")
      (value "~220")
      (footprint "eagle-import:0204_7")
      (libsource (lib "eagle-import") (part "R-US_0204/7"))
    )
    (comp (ref "R73")
      (value "~220")
      (footprint "eagle-import:0204_7")
      (libsource (lib "eagle-import") (part "R-US_0204/7"))
    )
    (comp (ref "R74")
      (value "~220")
      (footprint "eagle-import:0204_7")
      (libsource (lib "eagle-import") (part "R-US_0204/7"))
    )
    (comp (ref "R75")
      (value "~220")
      (footprint "eagle-import:0204_7")
      (libsource (lib "eagle-import") (part "R-US_0204/7"))
    )
    (comp (ref "R76")
      (value "~220")
      (footprint "eagle-import:0204_7")
      (libsource (lib "eagle-import") (part "R-US_0204/7"))
    )
    (comp (ref "R77")
      (value "~220")
      (footprint "eagle-import:0204_7")
      (libsource (lib "eagle-import") (part "R-US_0204/7"))
    )
    (comp (ref "R78")
      (value "~220")
      (footprint "eagle-import:0204_7")
      (libsource (lib "eagle-import") (part "R-US_0204/7"))
    )
    (comp (ref "R79")
      (value "~220")
      (footprint "eagle-import:0204_7")
      (libsource (lib "eagle-import") (part "R-US_0204/7"))
    )
    (comp (ref "R80")
      (value "~220")
      (footprint "eagle-import:0204_7")
      (libsource (lib "eagle-import") (part "R-US_0204/7"))
    )
    (comp (ref "R81")
      (value "~220")
      (footprint "eagle-import:0204_7")
      (libsource (lib "eagle-import") (part "R-US_0204/7"))
    )
    (comp (ref "RAM")
      (value "71256SA15TPG")
      (footprint "eagle-import:DIL28-3")
      (libsource (lib "eagle-import") (part "DIL28-3"))
    )
    (comp (ref "RAM_ADDR_LOWER")
      (value "74LS173N")
      (footprint "eagle-import:DIL16")
      (libsource (lib "eagle-import") (part "74173NLS"))
    )
    (comp (ref "RAM_ADDR_UPPER")
      (value "74LS173N")
      (footprint "eagle-import:DIL16")
      (libsource (lib "eagle-import") (part "74173NLS"))
    )
    (comp (ref "RAM_LED_1")
      (value "LED3MM")
      (footprint "eagle-import:LED3MM")
      (libsource (lib "eagle-import") (part "LED3MM"))
    )
    (comp (ref "RAM_LED_2")
      (value "LED3MM")
      (footprint "eagle-import:LED3MM")
      (libsource (lib "eagle-import") (part "LED3MM"))
    )
    (comp (ref "RAM_LED_3")
      (value "LED3MM")
      (footprint "eagle-import:LED3MM")
      (libsource (lib "eagle-import") (part "LED3MM"))
    )
    (comp (ref "RAM_LED_4")
      (value "LED3MM")
      (footprint "eagle-import:LED3MM")
      (libsource (lib "eagle-import") (part "LED3MM"))
    )
    (comp (ref "RAM_LED_5")
      (value "LED3MM")
      (footprint "eagle-import:LED3MM")
      (libsource (lib "eagle-import") (part "LED3MM"))
    )
    (comp (ref "RAM_LED_6")
      (value "LED3MM")
      (footprint "eagle-import:LED3MM")
      (libsource (lib "eagle-import") (part "LED3MM"))
    )
    (comp (ref "RAM_LED_7")
      (value "LED3MM")
      (footprint "eagle-import:LED3MM")
      (libsource (lib "eagle-import") (part "LED3MM"))
    )
    (comp (ref "RAM_LED_8")
      (value "LED3MM")
      (footprint "eagle-import:LED3MM")
      (libsource (lib "eagle-import") (part "LED3MM"))
    )
    (comp (ref "REG_A_LOWER")
      (value "74LS173N")
      (footprint "eagle-import:DIL16")
      (libsource (lib "eagle-import") (part "74173NLS"))
    )
    (comp (ref "REG_A_UPPER")
      (value "74LS173N")
      (footprint "eagle-import:DIL16")
      (libsource (lib "eagle-import") (part "74173NLS"))
    )
    (comp (ref "REG_CALC_LOWER")
      (value "74LS173N")
      (footprint "eagle-import:DIL16")
      (libsource (lib "eagle-import") (part "74173NLS"))
    )
    (comp (ref "REG_CALC_UPPER")
      (value "74LS173N")
      (footprint "eagle-import:DIL16")
      (libsource (lib "eagle-import") (part "74173NLS"))
    )
    (comp (ref "REG_PARAM_LOWER")
      (value "74LS173N")
      (footprint "eagle-import:DIL16")
      (libsource (lib "eagle-import") (part "74173NLS"))
    )
    (comp (ref "REG_PARAM_UPPER")
      (value "74LS173N")
      (footprint "eagle-import:DIL16")
      (libsource (lib "eagle-import") (part "74173NLS"))
    )
    (comp (ref "RESET_PC")
      (value "NORM-OFF")
      (footprint "eagle-import:B3F-10XX")
      (fields (field (name "MPN") "B3F-1000"))
      (libsource (lib "eagle-import") (part "10-XX"))
    )
    (comp (ref "RESET_REGS")
      (value "NORM-OFF")
      (footprint "eagle-import:B3F-10XX")
      (fields (field (name "MPN") "B3F-1000"))
      (libsource (lib "eagle-import") (part "10-XX"))
    )
    (comp (ref "SELECTOR_BRANCH_")
      (value "74HC139N")
      (footprint "eagle-import:DIL16")
      (libsource (lib "eagle-import") (part "74139NHC"))
    )
    (comp (ref "SELECTOR_INSRUCTION_LOWER")
      (value "74LS157N")
      (footprint "eagle-import:DIL16")
      (libsource (lib "eagle-import") (part "74157NLS"))
    )
    (comp (ref "SELECTOR_INSRUCTION_UPPER")
      (value "74LS157N")
      (footprint "eagle-import:DIL16")
      (libsource (lib "eagle-import") (part "74157NLS"))
    )
    (comp (ref "SELECTOR_LOGIC_")
      (value "74HC139N")
      (footprint "eagle-import:DIL16")
      (libsource (lib "eagle-import") (part "74139NHC"))
    )
    (comp (ref "SELECTOR_PARAM_")
      (value "74LS139N")
      (footprint "eagle-import:DIL16")
      (libsource (lib "eagle-import") (part "74139NLS"))
    )
    (comp (ref "SELECTOR_STACK_")
      (value "74LS139N")
      (footprint "eagle-import:DIL16")
      (libsource (lib "eagle-import") (part "74139NLS"))
    )
    (comp (ref "STEPPER_CLOCK")
      (value "NE555N")
      (footprint "eagle-import:DIL08")
      (libsource (lib "eagle-import") (part "555NNE"))
    )
    (comp (ref "SUBTRACT_INVRTR_LOWER_")
      (value "74LS86N")
      (footprint "eagle-import:DIL14")
      (libsource (lib "eagle-import") (part "7486NLS"))
    )
    (comp (ref "SUBTRACT_INVRTR_UPPER_")
      (value "74LS86N")
      (footprint "eagle-import:DIL14")
      (libsource (lib "eagle-import") (part "7486NLS"))
    )
    (comp (ref "USTEP_1")
      (value "LED")
      (footprint "eagle-import:LED5MM")
      (libsource (lib "eagle-import") (part "LED5MM"))
    )
    (comp (ref "USTEP_2")
      (value "LED")
      (footprint "eagle-import:LED5MM")
      (libsource (lib "eagle-import") (part "LED5MM"))
    )
    (comp (ref "USTEP_3")
      (value "LED")
      (footprint "eagle-import:LED5MM")
      (libsource (lib "eagle-import") (part "LED5MM"))
    )
    (comp (ref "USTEP_4")
      (value "LED")
      (footprint "eagle-import:LED5MM")
      (libsource (lib "eagle-import") (part "LED5MM"))
    )
    (comp (ref "USTEP_5")
      (value "LED")
      (footprint "eagle-import:LED5MM")
      (libsource (lib "eagle-import") (part "LED5MM"))
    )
    (comp (ref "X1")
      (value "SSW-103-02-G-S")
      (footprint "eagle-import:SSW-103-02-G-S")
      (fields (field (name "MF") "Samtec Inc."))
      (libsource (lib "eagle-import") (part "SSW-103-02-G-S"))
    )
    (comp (ref "XOR_GATE_1")
      (value "74LS86N")
      (footprint "eagle-import:DIL14")
      (libsource (lib "eagle-import") (part "7486NLS"))
    )
    (comp (ref "XOR_GATE_2")
      (value "74LS86N")
      (footprint "eagle-import:DIL14")
      (libsource (lib "eagle-import") (part "7486NLS"))
    )
    (comp (ref "ZERO_FLAG")
      (value "220")
      (footprint "eagle-import:LED5MM")
      (libsource (lib "eagle-import") (part "LED5MM"))
    )
    (comp (ref "ZERO_POS_FLAG_IDENTIFIER")
      (value "744078N")
      (footprint "eagle-import:DIL14")
      (libsource (lib "eagle-import") (part "744078N"))
    )
  )
  (nets
    (net (code "1") (name "GND") (class "Default")
      (node (ref "4_INP_OR_GATE") (pin "7") (pinfunction "VSS_7") (pintype "power_in"))
      (node (ref "ADDR_MEM_REG_LOWER") (pin "1") (pinfunction "M_1") (pintype "input"))
      (node (ref "ADDR_MEM_REG_LOWER") (pin "2") (pinfunction "N_2") (pintype "input"))
      (node (ref "ADDR_MEM_REG_UPPER") (pin "1") (pinfunction "M_1") (pintype "input"))
      (node (ref "ADDR_MEM_REG_UPPER") (pin "2") (pinfunction "N_2") (pintype "input"))
      (node (ref "AUTO_CLOCK") (pin "1") (pinfunction "GND_1") (pintype "power_in"))
      (node (ref "C1") (pin "-") (pinfunction "-_-") (pintype "passive"))
      (node (ref "C2") (pin "-") (pinfunction "-_-") (pintype "passive"))
      (node (ref "C3") (pin "-") (pinfunction "-_-") (pintype "passive"))
      (node (ref "C4") (pin "-") (pinfunction "-_-") (pintype "passive"))
      (node (ref "CLK_TRIGGER") (pin "3") (pinfunction "P_3") (pintype "passive"))
      (node (ref "EXTENSION") (pin "11") (pinfunction "1_11") (pintype "passive"))
      (node (ref "FIFO_STACK") (pin "14") (pinfunction "14_14") (pintype "passive"))
      (node (ref "FIFO_STACK") (pin "2") (pinfunction "2_2") (pintype "passive"))
      (node (ref "FIFO_STACK") (pin "7") (pinfunction "7_7") (pintype "passive"))
      (node (ref "FLAG_REG_LOWER") (pin "1") (pinfunction "M_1") (pintype "input"))
      (node (ref "FLAG_REG_LOWER") (pin "2") (pinfunction "N_2") (pintype "input"))
      (node (ref "FLAG_REG_UPPER") (pin "1") (pinfunction "M_1") (pintype "input"))
      (node (ref "FLAG_REG_UPPER") (pin "2") (pinfunction "N_2") (pintype "input"))
      (node (ref "INSTRUCTIONS_EXTENSION") (pin "15") (pinfunction "1_15") (pintype "passive"))
      (node (ref "INSTRUCTION_MEMORY_0") (pin "14") (pinfunction "14_14") (pintype "passive"))
      (node (ref "INSTRUCTION_MEMORY_0") (pin "20") (pinfunction "20_20") (pintype "passive"))
      (node (ref "INSTRUCTION_MEMORY_0") (pin "22") (pinfunction "22_22") (pintype "passive"))
      (node (ref "INSTRUCTION_MEMORY_1") (pin "14") (pinfunction "14_14") (pintype "passive"))
      (node (ref "INSTRUCTION_MEMORY_1") (pin "20") (pinfunction "20_20") (pintype "passive"))
      (node (ref "INSTRUCTION_MEMORY_1") (pin "22") (pinfunction "22_22") (pintype "passive"))
      (node (ref "INSTRUCTION_MEMORY_2") (pin "14") (pinfunction "14_14") (pintype "passive"))
      (node (ref "INSTRUCTION_MEMORY_2") (pin "20") (pinfunction "20_20") (pintype "passive"))
      (node (ref "INSTRUCTION_MEMORY_2") (pin "22") (pinfunction "22_22") (pintype "passive"))
      (node (ref "INSTRUC_REGISTER_LOWER") (pin "1") (pinfunction "M_1") (pintype "input"))
      (node (ref "INSTRUC_REGISTER_LOWER") (pin "2") (pinfunction "N_2") (pintype "input"))
      (node (ref "INSTRUC_REGISTER_UPPER") (pin "1") (pinfunction "M_1") (pintype "input"))
      (node (ref "INSTRUC_REGISTER_UPPER") (pin "2") (pinfunction "N_2") (pintype "input"))
      (node (ref "KEYBOARD") (pin "4") (pinfunction "1_4") (pintype "passive"))
      (node (ref "KEYBOARD_ASCII_TABLE") (pin "14") (pinfunction "14_14") (pintype "passive"))
      (node (ref "KEYBOARD_ASCII_TABLE") (pin "2") (pinfunction "2_2") (pintype "passive"))
      (node (ref "KEYBOARD_ASCII_TABLE") (pin "20") (pinfunction "20_20") (pintype "passive"))
      (node (ref "KEYBOARD_ASCII_TABLE") (pin "21") (pinfunction "21_21") (pintype "passive"))
      (node (ref "KEYBOARD_ASCII_TABLE") (pin "22") (pinfunction "22_22") (pintype "passive"))
      (node (ref "KEYBOARD_ASCII_TABLE") (pin "23") (pinfunction "23_23") (pintype "passive"))
      (node (ref "KEYBOARD_ASCII_TABLE") (pin "24") (pinfunction "24_24") (pintype "passive"))
      (node (ref "KEYBOARD_ASCII_TABLE") (pin "25") (pinfunction "25_25") (pintype "passive"))
      (node (ref "KEYBOARD_SHIFT_LOWER") (pin "13") (pinfunction "G_13") (pintype "input"))
      (node (ref "KEYBOARD_SHIFT_UPPER") (pin "13") (pinfunction "G_13") (pintype "input"))
      (node (ref "MEMORY") (pin "14") (pinfunction "14_14") (pintype "passive"))
      (node (ref "MEMORY") (pin "2") (pinfunction "2_2") (pintype "passive"))
      (node (ref "MEMORY") (pin "20") (pinfunction "20_20") (pintype "passive"))
      (node (ref "MEMORY") (pin "21") (pinfunction "21_21") (pintype "passive"))
      (node (ref "MEMORY") (pin "22") (pinfunction "22_22") (pintype "passive"))
      (node (ref "MEMORY") (pin "23") (pinfunction "23_23") (pintype "passive"))
      (node (ref "MEMORY") (pin "24") (pinfunction "24_24") (pintype "passive"))
      (node (ref "MICRO_COUNTER_LOWER") (pin "8") (pinfunction "8_8") (pintype "passive"))
      (node (ref "MICRO_COUNTER_UPPER") (pin "8") (pinfunction "8_8") (pintype "passive"))
      (node (ref "OUTPUT_BUFFER_ALU") (pin "1") (pinfunction "DIR_1") (pintype "input"))
      (node (ref "OUTPUT_BUFFER_FLAGS") (pin "1") (pinfunction "DIR_1") (pintype "input"))
      (node (ref "OUTPUT_BUFFER_KEYBOARD") (pin "1") (pinfunction "DIR_1") (pintype "input"))
      (node (ref "OUT_REG_LOWER") (pin "1") (pinfunction "M_1") (pintype "input"))
      (node (ref "OUT_REG_LOWER") (pin "2") (pinfunction "N_2") (pintype "input"))
      (node (ref "OUT_REG_UPPER") (pin "1") (pinfunction "M_1") (pintype "input"))
      (node (ref "OUT_REG_UPPER") (pin "2") (pinfunction "N_2") (pintype "input"))
      (node (ref "OUT_ROM_LOWER") (pin "14") (pinfunction "14_14") (pintype "passive"))
      (node (ref "OUT_ROM_LOWER") (pin "2") (pinfunction "2_2") (pintype "passive"))
      (node (ref "OUT_ROM_LOWER") (pin "20") (pinfunction "20_20") (pintype "passive"))
      (node (ref "OUT_ROM_LOWER") (pin "21") (pinfunction "21_21") (pintype "passive"))
      (node (ref "OUT_ROM_LOWER") (pin "22") (pinfunction "22_22") (pintype "passive"))
      (node (ref "OUT_ROM_LOWER") (pin "23") (pinfunction "23_23") (pintype "passive"))
      (node (ref "OUT_ROM_LOWER") (pin "24") (pinfunction "24_24") (pintype "passive"))
      (node (ref "OUT_ROM_LOWER") (pin "25") (pinfunction "25_25") (pintype "passive"))
      (node (ref "OUT_ROM_LOWER") (pin "3") (pinfunction "3_3") (pintype "passive"))
      (node (ref "OUT_ROM_LOWER") (pin "4") (pinfunction "4_4") (pintype "passive"))
      (node (ref "OUT_ROM_LOWER") (pin "5") (pinfunction "5_5") (pintype "passive"))
      (node (ref "OUT_ROM_LOWER") (pin "6") (pinfunction "6_6") (pintype "passive"))
      (node (ref "OUT_ROM_UPPER") (pin "14") (pinfunction "14_14") (pintype "passive"))
      (node (ref "OUT_ROM_UPPER") (pin "2") (pinfunction "2_2") (pintype "passive"))
      (node (ref "OUT_ROM_UPPER") (pin "20") (pinfunction "20_20") (pintype "passive"))
      (node (ref "OUT_ROM_UPPER") (pin "21") (pinfunction "21_21") (pintype "passive"))
      (node (ref "OUT_ROM_UPPER") (pin "22") (pinfunction "22_22") (pintype "passive"))
      (node (ref "OUT_ROM_UPPER") (pin "23") (pinfunction "23_23") (pintype "passive"))
      (node (ref "OUT_ROM_UPPER") (pin "24") (pinfunction "24_24") (pintype "passive"))
      (node (ref "OUT_ROM_UPPER") (pin "25") (pinfunction "25_25") (pintype "passive"))
      (node (ref "OUT_ROM_UPPER") (pin "3") (pinfunction "3_3") (pintype "passive"))
      (node (ref "OUT_ROM_UPPER") (pin "4") (pinfunction "4_4") (pintype "passive"))
      (node (ref "OUT_ROM_UPPER") (pin "5") (pinfunction "5_5") (pintype "passive"))
      (node (ref "OUT_ROM_UPPER") (pin "6") (pinfunction "6_6") (pintype "passive"))
      (node (ref "OUT_SEGMENT_LOWER") (pin "3") (pinfunction "CK1_3") (pintype "passive"))
      (node (ref "OUT_SEGMENT_LOWER") (pin "8") (pinfunction "CK2_8") (pintype "passive"))
      (node (ref "OUT_SEGMENT_UPPER") (pin "3") (pinfunction "CK1_3") (pintype "passive"))
      (node (ref "OUT_SEGMENT_UPPER") (pin "8") (pinfunction "CK2_8") (pintype "passive"))
      (node (ref "PROGRAM_COUNTER_LOWER") (pin "8") (pinfunction "8_8") (pintype "passive"))
      (node (ref "PROGRAM_COUNTER_UPPER") (pin "8") (pinfunction "8_8") (pintype "passive"))
      (node (ref "R10") (pin "1") (pinfunction "1_1") (pintype "passive"))
      (node (ref "R11") (pin "1") (pinfunction "1_1") (pintype "passive"))
      (node (ref "R12") (pin "1") (pinfunction "1_1") (pintype "passive"))
      (node (ref "R13") (pin "1") (pinfunction "1_1") (pintype "passive"))
      (node (ref "R14") (pin "1") (pinfunction "1_1") (pintype "passive"))
      (node (ref "R15") (pin "1") (pinfunction "1_1") (pintype "passive"))
      (node (ref "R16") (pin "2") (pinfunction "2_2") (pintype "passive"))
      (node (ref "R17") (pin "2") (pinfunction "2_2") (pintype "passive"))
      (node (ref "R18") (pin "2") (pinfunction "2_2") (pintype "passive"))
      (node (ref "R19") (pin "2") (pinfunction "2_2") (pintype "passive"))
      (node (ref "R20") (pin "2") (pinfunction "2_2") (pintype "passive"))
      (node (ref "R21") (pin "2") (pinfunction "2_2") (pintype "passive"))
      (node (ref "R22") (pin "2") (pinfunction "2_2") (pintype "passive"))
      (node (ref "R23") (pin "2") (pinfunction "2_2") (pintype "passive"))
      (node (ref "R24") (pin "2") (pinfunction "2_2") (pintype "passive"))
      (node (ref "R25") (pin "2") (pinfunction "2_2") (pintype "passive"))
      (node (ref "R26") (pin "2") (pinfunction "2_2") (pintype "passive"))
      (node (ref "R27") (pin "2") (pinfunction "2_2") (pintype "passive"))
      (node (ref "R28") (pin "2") (pinfunction "2_2") (pintype "passive"))
      (node (ref "R29") (pin "2") (pinfunction "2_2") (pintype "passive"))
      (node (ref "R30") (pin "2") (pinfunction "2_2") (pintype "passive"))
      (node (ref "R31") (pin "2") (pinfunction "2_2") (pintype "passive"))
      (node (ref "R32") (pin "2") (pinfunction "2_2") (pintype "passive"))
      (node (ref "R33") (pin "2") (pinfunction "2_2") (pintype "passive"))
      (node (ref "R34") (pin "2") (pinfunction "2_2") (pintype "passive"))
      (node (ref "R35") (pin "2") (pinfunction "2_2") (pintype "passive"))
      (node (ref "R36") (pin "2") (pinfunction "2_2") (pintype "passive"))
      (node (ref "R37") (pin "2") (pinfunction "2_2") (pintype "passive"))
      (node (ref "R38") (pin "2") (pinfunction "2_2") (pintype "passive"))
      (node (ref "R39") (pin "2") (pinfunction "2_2") (pintype "passive"))
      (node (ref "R4") (pin "1") (pinfunction "1_1") (pintype "passive"))
      (node (ref "R40") (pin "1") (pinfunction "1_1") (pintype "passive"))
      (node (ref "R41") (pin "1") (pinfunction "1_1") (pintype "passive"))
      (node (ref "R42") (pin "1") (pinfunction "1_1") (pintype "passive"))
      (node (ref "R43") (pin "1") (pinfunction "1_1") (pintype "passive"))
      (node (ref "R44") (pin "1") (pinfunction "1_1") (pintype "passive"))
      (node (ref "R45") (pin "1") (pinfunction "1_1") (pintype "passive"))
      (node (ref "R5") (pin "1") (pinfunction "1_1") (pintype "passive"))
      (node (ref "R53") (pin "2") (pinfunction "2_2") (pintype "passive"))
      (node (ref "R54") (pin "2") (pinfunction "2_2") (pintype "passive"))
      (node (ref "R55") (pin "2") (pinfunction "2_2") (pintype "passive"))
      (node (ref "R56") (pin "2") (pinfunction "2_2") (pintype "passive"))
      (node (ref "R57") (pin "2") (pinfunction "2_2") (pintype "passive"))
      (node (ref "R58") (pin "2") (pinfunction "2_2") (pintype "passive"))
      (node (ref "R59") (pin "2") (pinfunction "2_2") (pintype "passive"))
      (node (ref "R60") (pin "2") (pinfunction "2_2") (pintype "passive"))
      (node (ref "R61") (pin "2") (pinfunction "2_2") (pintype "passive"))
      (node (ref "R62") (pin "2") (pinfunction "2_2") (pintype "passive"))
      (node (ref "R63") (pin "2") (pinfunction "2_2") (pintype "passive"))
      (node (ref "R64") (pin "2") (pinfunction "2_2") (pintype "passive"))
      (node (ref "R65") (pin "2") (pinfunction "2_2") (pintype "passive"))
      (node (ref "R66") (pin "2") (pinfunction "2_2") (pintype "passive"))
      (node (ref "R67") (pin "2") (pinfunction "2_2") (pintype "passive"))
      (node (ref "R68") (pin "2") (pinfunction "2_2") (pintype "passive"))
      (node (ref "R69") (pin "2") (pinfunction "2_2") (pintype "passive"))
      (node (ref "R70") (pin "2") (pinfunction "2_2") (pintype "passive"))
      (node (ref "R71") (pin "2") (pinfunction "2_2") (pintype "passive"))
      (node (ref "R72") (pin "2") (pinfunction "2_2") (pintype "passive"))
      (node (ref "R73") (pin "2") (pinfunction "2_2") (pintype "passive"))
      (node (ref "R74") (pin "2") (pinfunction "2_2") (pintype "passive"))
      (node (ref "R75") (pin "2") (pinfunction "2_2") (pintype "passive"))
      (node (ref "R76") (pin "2") (pinfunction "2_2") (pintype "passive"))
      (node (ref "R77") (pin "1") (pinfunction "1_1") (pintype "passive"))
      (node (ref "R78") (pin "1") (pinfunction "1_1") (pintype "passive"))
      (node (ref "R79") (pin "1") (pinfunction "1_1") (pintype "passive"))
      (node (ref "R8") (pin "1") (pinfunction "1_1") (pintype "passive"))
      (node (ref "R81") (pin "2") (pinfunction "2_2") (pintype "passive"))
      (node (ref "R9") (pin "1") (pinfunction "1_1") (pintype "passive"))
      (node (ref "RAM") (pin "1") (pinfunction "1_1") (pintype "passive"))
      (node (ref "RAM") (pin "14") (pinfunction "14_14") (pintype "passive"))
      (node (ref "RAM") (pin "2") (pinfunction "2_2") (pintype "passive"))
      (node (ref "RAM") (pin "20") (pinfunction "20_20") (pintype "passive"))
      (node (ref "RAM") (pin "21") (pinfunction "21_21") (pintype "passive"))
      (node (ref "RAM") (pin "23") (pinfunction "23_23") (pintype "passive"))
      (node (ref "RAM") (pin "24") (pinfunction "24_24") (pintype "passive"))
      (node (ref "RAM") (pin "25") (pinfunction "25_25") (pintype "passive"))
      (node (ref "RAM") (pin "26") (pinfunction "26_26") (pintype "passive"))
      (node (ref "RAM_ADDR_LOWER") (pin "1") (pinfunction "M_1") (pintype "input"))
      (node (ref "RAM_ADDR_LOWER") (pin "2") (pinfunction "N_2") (pintype "input"))
      (node (ref "RAM_ADDR_UPPER") (pin "1") (pinfunction "M_1") (pintype "input"))
      (node (ref "RAM_ADDR_UPPER") (pin "2") (pinfunction "N_2") (pintype "input"))
      (node (ref "REG_A_LOWER") (pin "1") (pinfunction "M_1") (pintype "input"))
      (node (ref "REG_A_LOWER") (pin "2") (pinfunction "N_2") (pintype "input"))
      (node (ref "REG_A_UPPER") (pin "1") (pinfunction "M_1") (pintype "input"))
      (node (ref "REG_A_UPPER") (pin "2") (pinfunction "N_2") (pintype "input"))
      (node (ref "REG_CALC_LOWER") (pin "1") (pinfunction "M_1") (pintype "input"))
      (node (ref "REG_CALC_LOWER") (pin "2") (pinfunction "N_2") (pintype "input"))
      (node (ref "REG_CALC_UPPER") (pin "1") (pinfunction "M_1") (pintype "input"))
      (node (ref "REG_CALC_UPPER") (pin "2") (pinfunction "N_2") (pintype "input"))
      (node (ref "REG_PARAM_LOWER") (pin "1") (pinfunction "M_1") (pintype "input"))
      (node (ref "REG_PARAM_LOWER") (pin "2") (pinfunction "N_2") (pintype "input"))
      (node (ref "REG_PARAM_UPPER") (pin "1") (pinfunction "M_1") (pintype "input"))
      (node (ref "REG_PARAM_UPPER") (pin "2") (pinfunction "N_2") (pintype "input"))
      (node (ref "RESET_PC") (pin "4") (pinfunction "P1_4") (pintype "passive"))
      (node (ref "SELECTOR_BRANCH_") (pin "1") (pinfunction "G_1") (pintype "input"))
      (node (ref "SELECTOR_BRANCH_") (pin "15") (pinfunction "G_15") (pintype "input"))
      (node (ref "SELECTOR_INSRUCTION_LOWER") (pin "11") (pinfunction "3A_11") (pintype "input"))
      (node (ref "SELECTOR_INSRUCTION_LOWER") (pin "14") (pinfunction "4A_14") (pintype "input"))
      (node (ref "SELECTOR_INSRUCTION_LOWER") (pin "15") (pinfunction "G_15") (pintype "input"))
      (node (ref "SELECTOR_INSRUCTION_LOWER") (pin "2") (pinfunction "1A_2") (pintype "input"))
      (node (ref "SELECTOR_INSRUCTION_LOWER") (pin "5") (pinfunction "2A_5") (pintype "input"))
      (node (ref "SELECTOR_INSRUCTION_UPPER") (pin "11") (pinfunction "3A_11") (pintype "input"))
      (node (ref "SELECTOR_INSRUCTION_UPPER") (pin "14") (pinfunction "4A_14") (pintype "input"))
      (node (ref "SELECTOR_INSRUCTION_UPPER") (pin "15") (pinfunction "G_15") (pintype "input"))
      (node (ref "SELECTOR_INSRUCTION_UPPER") (pin "2") (pinfunction "1A_2") (pintype "input"))
      (node (ref "SELECTOR_INSRUCTION_UPPER") (pin "5") (pinfunction "2A_5") (pintype "input"))
      (node (ref "SELECTOR_LOGIC_") (pin "1") (pinfunction "G_1") (pintype "input"))
      (node (ref "SELECTOR_LOGIC_") (pin "15") (pinfunction "G_15") (pintype "input"))
      (node (ref "SELECTOR_PARAM_") (pin "1") (pinfunction "G_1") (pintype "input"))
      (node (ref "SELECTOR_PARAM_") (pin "15") (pinfunction "G_15") (pintype "input"))
      (node (ref "SELECTOR_STACK_") (pin "1") (pinfunction "G_1") (pintype "input"))
      (node (ref "SELECTOR_STACK_") (pin "15") (pinfunction "G_15") (pintype "input"))
      (node (ref "STEPPER_CLOCK") (pin "1") (pinfunction "GND_1") (pintype "power_in"))
      (node (ref "X1") (pin "1") (pinfunction "1_1") (pintype "passive"))
      (node (ref "ZERO_POS_FLAG_IDENTIFIER") (pin "7") (pinfunction "-UB_7") (pintype "power_in"))
    )
    (net (code "2") (name "Net-(4_INP_OR_GATEA-I0)") (class "Default")
      (node (ref "4_INP_OR_GATE") (pin "2") (pinfunction "I0_2") (pintype "input"))
      (node (ref "NOT_GATE4_") (pin "2") (pinfunction "O_2") (pintype "output"))
    )
    (net (code "3") (name "Net-(4_INP_OR_GATEA-I1)") (class "Default")
      (node (ref "4_INP_OR_GATE") (pin "3") (pinfunction "I1_3") (pintype "input"))
      (node (ref "AND_GATE3_") (pin "11") (pinfunction "O_11") (pintype "output"))
    )
    (net (code "4") (name "Net-(4_INP_OR_GATEA-I2)") (class "Default")
      (node (ref "4_INP_OR_GATE") (pin "4") (pinfunction "I2_4") (pintype "input"))
      (node (ref "AND_GATE4_") (pin "3") (pinfunction "O_3") (pintype "output"))
    )
    (net (code "5") (name "Net-(4_INP_OR_GATEA-I3)") (class "Default")
      (node (ref "4_INP_OR_GATE") (pin "5") (pinfunction "I3_5") (pintype "input"))
      (node (ref "AND_GATE4_") (pin "6") (pinfunction "O_6") (pintype "output"))
    )
    (net (code "6") (name "Net-(4_INP_OR_GATEA-O)") (class "Default")
      (node (ref "4_INP_OR_GATE") (pin "1") (pinfunction "O_1") (pintype "output"))
      (node (ref "AND_GATE3_") (pin "1") (pinfunction "I0_1") (pintype "input"))
      (node (ref "AND_GATE3_") (pin "4") (pinfunction "I0_4") (pintype "input"))
    )
    (net (code "7") (name "Net-(ADDER_LOWERA-A1)") (class "Default")
      (node (ref "ADDER_LOWER") (pin "5") (pinfunction "A1_5") (pintype "input"))
      (node (ref "LED_A_REG_1") (pin "A") (pinfunction "A_A") (pintype "passive"))
      (node (ref "OUTPUT_BUFFER_REG_A") (pin "9") (pinfunction "A8_9") (pintype "bidirectional"))
      (node (ref "REG_A_LOWER") (pin "6") (pinfunction "Q4_6") (pintype "tri_state"))
      (node (ref "ZERO_POS_FLAG_IDENTIFIER") (pin "5") (pinfunction "D_5") (pintype "input"))
    )
    (net (code "8") (name "Net-(ADDER_LOWERA-A2)") (class "Default")
      (node (ref "ADDER_LOWER") (pin "3") (pinfunction "A2_3") (pintype "input"))
      (node (ref "LED_A_REG_2") (pin "A") (pinfunction "A_A") (pintype "passive"))
      (node (ref "OUTPUT_BUFFER_REG_A") (pin "8") (pinfunction "A7_8") (pintype "bidirectional"))
      (node (ref "REG_A_LOWER") (pin "5") (pinfunction "Q3_5") (pintype "tri_state"))
      (node (ref "ZERO_POS_FLAG_IDENTIFIER") (pin "4") (pinfunction "C_4") (pintype "input"))
    )
    (net (code "9") (name "Net-(ADDER_LOWERA-A3)") (class "Default")
      (node (ref "ADDER_LOWER") (pin "14") (pinfunction "A3_14") (pintype "input"))
      (node (ref "LED_A_REG_3") (pin "A") (pinfunction "A_A") (pintype "passive"))
      (node (ref "OUTPUT_BUFFER_REG_A") (pin "7") (pinfunction "A6_7") (pintype "bidirectional"))
      (node (ref "REG_A_LOWER") (pin "4") (pinfunction "Q2_4") (pintype "tri_state"))
      (node (ref "ZERO_POS_FLAG_IDENTIFIER") (pin "3") (pinfunction "B_3") (pintype "input"))
    )
    (net (code "10") (name "Net-(ADDER_LOWERA-A4)") (class "Default")
      (node (ref "ADDER_LOWER") (pin "12") (pinfunction "A4_12") (pintype "input"))
      (node (ref "LED_A_REG_4") (pin "A") (pinfunction "A_A") (pintype "passive"))
      (node (ref "OUTPUT_BUFFER_REG_A") (pin "6") (pinfunction "A5_6") (pintype "bidirectional"))
      (node (ref "REG_A_LOWER") (pin "3") (pinfunction "Q1_3") (pintype "tri_state"))
      (node (ref "ZERO_POS_FLAG_IDENTIFIER") (pin "2") (pinfunction "A_2") (pintype "input"))
    )
    (net (code "11") (name "Net-(ADDER_LOWERA-B1)") (class "Default")
      (node (ref "ADDER_LOWER") (pin "6") (pinfunction "B1_6") (pintype "input"))
      (node (ref "SUBTRACT_INVRTR_LOWER_") (pin "11") (pinfunction "O_11") (pintype "output"))
    )
    (net (code "12") (name "Net-(ADDER_LOWERA-B2)") (class "Default")
      (node (ref "ADDER_LOWER") (pin "2") (pinfunction "B2_2") (pintype "input"))
      (node (ref "SUBTRACT_INVRTR_LOWER_") (pin "8") (pinfunction "O_8") (pintype "output"))
    )
    (net (code "13") (name "Net-(ADDER_LOWERA-B3)") (class "Default")
      (node (ref "ADDER_LOWER") (pin "15") (pinfunction "B3_15") (pintype "input"))
      (node (ref "SUBTRACT_INVRTR_LOWER_") (pin "6") (pinfunction "O_6") (pintype "output"))
    )
    (net (code "14") (name "Net-(ADDER_LOWERA-B4)") (class "Default")
      (node (ref "ADDER_LOWER") (pin "11") (pinfunction "B4_11") (pintype "input"))
      (node (ref "SUBTRACT_INVRTR_LOWER_") (pin "3") (pinfunction "O_3") (pintype "output"))
    )
    (net (code "15") (name "Net-(ADDER_LOWERA-C0)") (class "Default")
      (node (ref "ADDER_LOWER") (pin "7") (pinfunction "C0_7") (pintype "input"))
      (node (ref "INSTRUCTION_MEMORY_1") (pin "15") (pinfunction "15_15") (pintype "passive"))
      (node (ref "SUBTRACT_INVRTR_LOWER_") (pin "1") (pinfunction "I0_1") (pintype "input"))
      (node (ref "SUBTRACT_INVRTR_LOWER_") (pin "12") (pinfunction "I0_12") (pintype "input"))
      (node (ref "SUBTRACT_INVRTR_LOWER_") (pin "4") (pinfunction "I0_4") (pintype "input"))
      (node (ref "SUBTRACT_INVRTR_LOWER_") (pin "9") (pinfunction "I0_9") (pintype "input"))
      (node (ref "SUBTRACT_INVRTR_UPPER_") (pin "1") (pinfunction "I0_1") (pintype "input"))
      (node (ref "SUBTRACT_INVRTR_UPPER_") (pin "12") (pinfunction "I0_12") (pintype "input"))
      (node (ref "SUBTRACT_INVRTR_UPPER_") (pin "4") (pinfunction "I0_4") (pintype "input"))
      (node (ref "SUBTRACT_INVRTR_UPPER_") (pin "9") (pinfunction "I0_9") (pintype "input"))
    )
    (net (code "16") (name "Net-(ADDER_LOWERA-C4)") (class "Default")
      (node (ref "ADDER_LOWER") (pin "9") (pinfunction "C4_9") (pintype "output"))
      (node (ref "ADDER_UPPER") (pin "7") (pinfunction "C0_7") (pintype "input"))
    )
    (net (code "17") (name "Net-(ADDER_LOWERA-S1)") (class "Default")
      (node (ref "ADDER_LOWER") (pin "4") (pinfunction "S1_4") (pintype "output"))
      (node (ref "OUTPUT_BUFFER_ALU") (pin "18") (pinfunction "B1_18") (pintype "bidirectional"))
    )
    (net (code "18") (name "Net-(ADDER_LOWERA-S2)") (class "Default")
      (node (ref "ADDER_LOWER") (pin "1") (pinfunction "S2_1") (pintype "output"))
      (node (ref "OUTPUT_BUFFER_ALU") (pin "17") (pinfunction "B2_17") (pintype "bidirectional"))
    )
    (net (code "19") (name "Net-(ADDER_LOWERA-S3)") (class "Default")
      (node (ref "ADDER_LOWER") (pin "13") (pinfunction "S3_13") (pintype "output"))
      (node (ref "OUTPUT_BUFFER_ALU") (pin "16") (pinfunction "B3_16") (pintype "bidirectional"))
    )
    (net (code "20") (name "Net-(ADDER_LOWERA-S4)") (class "Default")
      (node (ref "ADDER_LOWER") (pin "10") (pinfunction "S4_10") (pintype "output"))
      (node (ref "OUTPUT_BUFFER_ALU") (pin "15") (pinfunction "B4_15") (pintype "bidirectional"))
    )
    (net (code "21") (name "Net-(ADDER_UPPERA-A1)") (class "Default")
      (node (ref "ADDER_UPPER") (pin "5") (pinfunction "A1_5") (pintype "input"))
      (node (ref "LED_A_REG_5") (pin "A") (pinfunction "A_A") (pintype "passive"))
      (node (ref "OUTPUT_BUFFER_REG_A") (pin "5") (pinfunction "A4_5") (pintype "bidirectional"))
      (node (ref "REG_A_UPPER") (pin "6") (pinfunction "Q4_6") (pintype "tri_state"))
      (node (ref "ZERO_POS_FLAG_IDENTIFIER") (pin "9") (pinfunction "E_9") (pintype "input"))
    )
    (net (code "22") (name "Net-(ADDER_UPPERA-A2)") (class "Default")
      (node (ref "ADDER_UPPER") (pin "3") (pinfunction "A2_3") (pintype "input"))
      (node (ref "LED_A_REG_6") (pin "A") (pinfunction "A_A") (pintype "passive"))
      (node (ref "OUTPUT_BUFFER_REG_A") (pin "4") (pinfunction "A3_4") (pintype "bidirectional"))
      (node (ref "REG_A_UPPER") (pin "5") (pinfunction "Q3_5") (pintype "tri_state"))
      (node (ref "ZERO_POS_FLAG_IDENTIFIER") (pin "10") (pinfunction "F_10") (pintype "input"))
    )
    (net (code "23") (name "Net-(ADDER_UPPERA-A3)") (class "Default")
      (node (ref "ADDER_UPPER") (pin "14") (pinfunction "A3_14") (pintype "input"))
      (node (ref "LED_A_REG_7") (pin "A") (pinfunction "A_A") (pintype "passive"))
      (node (ref "OUTPUT_BUFFER_REG_A") (pin "3") (pinfunction "A2_3") (pintype "bidirectional"))
      (node (ref "REG_A_UPPER") (pin "4") (pinfunction "Q2_4") (pintype "tri_state"))
      (node (ref "ZERO_POS_FLAG_IDENTIFIER") (pin "11") (pinfunction "G_11") (pintype "input"))
    )
    (net (code "24") (name "Net-(ADDER_UPPERA-A4)") (class "Default")
      (node (ref "ADDER_UPPER") (pin "12") (pinfunction "A4_12") (pintype "input"))
      (node (ref "LED_A_REG_8") (pin "A") (pinfunction "A_A") (pintype "passive"))
      (node (ref "OUTPUT_BUFFER_REG_A") (pin "2") (pinfunction "A1_2") (pintype "bidirectional"))
      (node (ref "REG_A_UPPER") (pin "3") (pinfunction "Q1_3") (pintype "tri_state"))
      (node (ref "ZERO_POS_FLAG_IDENTIFIER") (pin "12") (pinfunction "H_12") (pintype "input"))
    )
    (net (code "25") (name "Net-(ADDER_UPPERA-B1)") (class "Default")
      (node (ref "ADDER_UPPER") (pin "6") (pinfunction "B1_6") (pintype "input"))
      (node (ref "SUBTRACT_INVRTR_UPPER_") (pin "11") (pinfunction "O_11") (pintype "output"))
    )
    (net (code "26") (name "Net-(ADDER_UPPERA-B2)") (class "Default")
      (node (ref "ADDER_UPPER") (pin "2") (pinfunction "B2_2") (pintype "input"))
      (node (ref "SUBTRACT_INVRTR_UPPER_") (pin "8") (pinfunction "O_8") (pintype "output"))
    )
    (net (code "27") (name "Net-(ADDER_UPPERA-B3)") (class "Default")
      (node (ref "ADDER_UPPER") (pin "15") (pinfunction "B3_15") (pintype "input"))
      (node (ref "SUBTRACT_INVRTR_UPPER_") (pin "6") (pinfunction "O_6") (pintype "output"))
    )
    (net (code "28") (name "Net-(ADDER_UPPERA-B4)") (class "Default")
      (node (ref "ADDER_UPPER") (pin "11") (pinfunction "B4_11") (pintype "input"))
      (node (ref "SUBTRACT_INVRTR_UPPER_") (pin "3") (pinfunction "O_3") (pintype "output"))
    )
    (net (code "29") (name "Net-(ADDER_UPPERA-C4)") (class "Default")
      (node (ref "ADDER_UPPER") (pin "9") (pinfunction "C4_9") (pintype "output"))
      (node (ref "AND_GATE3_") (pin "13") (pinfunction "I1_13") (pintype "input"))
      (node (ref "FLAG_REG_LOWER") (pin "14") (pinfunction "D1_14") (pintype "input"))
      (node (ref "OVERFLOW_FLAG") (pin "A") (pinfunction "A_A") (pintype "passive"))
    )
    (net (code "30") (name "Net-(ADDER_UPPERA-S1)") (class "Default")
      (node (ref "ADDER_UPPER") (pin "4") (pinfunction "S1_4") (pintype "output"))
      (node (ref "OUTPUT_BUFFER_ALU") (pin "14") (pinfunction "B5_14") (pintype "bidirectional"))
    )
    (net (code "31") (name "Net-(ADDER_UPPERA-S2)") (class "Default")
      (node (ref "ADDER_UPPER") (pin "1") (pinfunction "S2_1") (pintype "output"))
      (node (ref "OUTPUT_BUFFER_ALU") (pin "13") (pinfunction "B6_13") (pintype "bidirectional"))
    )
    (net (code "32") (name "Net-(ADDER_UPPERA-S3)") (class "Default")
      (node (ref "ADDER_UPPER") (pin "13") (pinfunction "S3_13") (pintype "output"))
      (node (ref "OUTPUT_BUFFER_ALU") (pin "12") (pinfunction "B7_12") (pintype "bidirectional"))
    )
    (net (code "33") (name "Net-(ADDER_UPPERA-S4)") (class "Default")
      (node (ref "ADDER_UPPER") (pin "10") (pinfunction "S4_10") (pintype "output"))
      (node (ref "OUTPUT_BUFFER_ALU") (pin "11") (pinfunction "B8_11") (pintype "bidirectional"))
    )
    (net (code "34") (name "Net-(ADDR_MEM_REG_LOWERA-CLK)") (class "Default")
      (node (ref "ADDR_MEM_REG_LOWER") (pin "7") (pinfunction "CLK_7") (pintype "input"))
      (node (ref "ADDR_MEM_REG_UPPER") (pin "7") (pinfunction "CLK_7") (pintype "input"))
      (node (ref "AND_GATE_") (pin "8") (pinfunction "O_8") (pintype "output"))
      (node (ref "CLOCK") (pin "A") (pinfunction "A_A") (pintype "passive"))
      (node (ref "EXTENSION") (pin "9") (pinfunction "1_9") (pintype "passive"))
      (node (ref "FLAG_REG_LOWER") (pin "7") (pinfunction "CLK_7") (pintype "input"))
      (node (ref "FLAG_REG_UPPER") (pin "7") (pinfunction "CLK_7") (pintype "input"))
      (node (ref "INSTRUC_REGISTER_LOWER") (pin "7") (pinfunction "CLK_7") (pintype "input"))
      (node (ref "INSTRUC_REGISTER_UPPER") (pin "7") (pinfunction "CLK_7") (pintype "input"))
      (node (ref "NOT_GATE1_") (pin "11") (pinfunction "I_11") (pintype "input"))
      (node (ref "OUT_REG_LOWER") (pin "7") (pinfunction "CLK_7") (pintype "input"))
      (node (ref "OUT_REG_UPPER") (pin "7") (pinfunction "CLK_7") (pintype "input"))
      (node (ref "PROGRAM_COUNTER_LOWER") (pin "2") (pinfunction "2_2") (pintype "passive"))
      (node (ref "PROGRAM_COUNTER_UPPER") (pin "2") (pinfunction "2_2") (pintype "passive"))
      (node (ref "RAM_ADDR_LOWER") (pin "7") (pinfunction "CLK_7") (pintype "input"))
      (node (ref "RAM_ADDR_UPPER") (pin "7") (pinfunction "CLK_7") (pintype "input"))
      (node (ref "REG_A_LOWER") (pin "7") (pinfunction "CLK_7") (pintype "input"))
      (node (ref "REG_A_UPPER") (pin "7") (pinfunction "CLK_7") (pintype "input"))
      (node (ref "REG_CALC_LOWER") (pin "7") (pinfunction "CLK_7") (pintype "input"))
      (node (ref "REG_CALC_UPPER") (pin "7") (pinfunction "CLK_7") (pintype "input"))
      (node (ref "REG_PARAM_LOWER") (pin "7") (pinfunction "CLK_7") (pintype "input"))
      (node (ref "REG_PARAM_UPPER") (pin "7") (pinfunction "CLK_7") (pintype "input"))
    )
    (net (code "35") (name "Net-(ADDR_MEM_REG_LOWERA-CLR)") (class "Default")
      (node (ref "ADDR_MEM_REG_LOWER") (pin "15") (pinfunction "CLR_15") (pintype "input"))
      (node (ref "ADDR_MEM_REG_UPPER") (pin "15") (pinfunction "CLR_15") (pintype "input"))
      (node (ref "FLAG_REG_LOWER") (pin "15") (pinfunction "CLR_15") (pintype "input"))
      (node (ref "FLAG_REG_UPPER") (pin "15") (pinfunction "CLR_15") (pintype "input"))
      (node (ref "INSTRUC_REGISTER_LOWER") (pin "15") (pinfunction "CLR_15") (pintype "input"))
      (node (ref "INSTRUC_REGISTER_UPPER") (pin "15") (pinfunction "CLR_15") (pintype "input"))
      (node (ref "OUT_REG_LOWER") (pin "15") (pinfunction "CLR_15") (pintype "input"))
      (node (ref "OUT_REG_UPPER") (pin "15") (pinfunction "CLR_15") (pintype "input"))
      (node (ref "R81") (pin "1") (pinfunction "1_1") (pintype "passive"))
      (node (ref "RAM_ADDR_LOWER") (pin "15") (pinfunction "CLR_15") (pintype "input"))
      (node (ref "RAM_ADDR_UPPER") (pin "15") (pinfunction "CLR_15") (pintype "input"))
      (node (ref "REG_A_LOWER") (pin "15") (pinfunction "CLR_15") (pintype "input"))
      (node (ref "REG_A_UPPER") (pin "15") (pinfunction "CLR_15") (pintype "input"))
      (node (ref "REG_CALC_LOWER") (pin "15") (pinfunction "CLR_15") (pintype "input"))
      (node (ref "REG_CALC_UPPER") (pin "15") (pinfunction "CLR_15") (pintype "input"))
      (node (ref "REG_PARAM_LOWER") (pin "15") (pinfunction "CLR_15") (pintype "input"))
      (node (ref "REG_PARAM_UPPER") (pin "15") (pinfunction "CLR_15") (pintype "input"))
      (node (ref "RESET_REGS") (pin "4") (pinfunction "P1_4") (pintype "passive"))
    )
    (net (code "36") (name "Net-(ADDR_MEM_REG_LOWERA-D1)") (class "Default")
      (node (ref "ADDR_MEM_REG_LOWER") (pin "14") (pinfunction "D1_14") (pintype "input"))
      (node (ref "DATABUS_4") (pin "A") (pinfunction "A_A") (pintype "passive"))
      (node (ref "EXTENSION") (pin "4") (pinfunction "1_4") (pintype "passive"))
      (node (ref "FIFO_STACK") (pin "12") (pinfunction "12_12") (pintype "passive"))
      (node (ref "FIFO_STACK") (pin "3") (pinfunction "3_3") (pintype "passive"))
      (node (ref "INSTRUC_REGISTER_LOWER") (pin "14") (pinfunction "D1_14") (pintype "input"))
      (node (ref "MICRO_COUNTER_LOWER") (pin "6") (pinfunction "6_6") (pintype "passive"))
      (node (ref "OUTPUT_BUFFER_ALU") (pin "5") (pinfunction "A4_5") (pintype "bidirectional"))
      (node (ref "OUTPUT_BUFFER_CALC_REG") (pin "14") (pinfunction "B5_14") (pintype "bidirectional"))
      (node (ref "OUTPUT_BUFFER_FLAGS") (pin "5") (pinfunction "A4_5") (pintype "bidirectional"))
      (node (ref "OUTPUT_BUFFER_INSTRUCTION") (pin "14") (pinfunction "B5_14") (pintype "bidirectional"))
      (node (ref "OUTPUT_BUFFER_KEYBOARD") (pin "5") (pinfunction "A4_5") (pintype "bidirectional"))
      (node (ref "OUTPUT_BUFFER_MEMORY") (pin "14") (pinfunction "B5_14") (pintype "bidirectional"))
      (node (ref "OUTPUT_BUFFER_PARAM_REG") (pin "14") (pinfunction "B5_14") (pintype "bidirectional"))
      (node (ref "OUTPUT_BUFFER_PC") (pin "14") (pinfunction "B5_14") (pintype "bidirectional"))
      (node (ref "OUTPUT_BUFFER_RAM") (pin "15") (pinfunction "B4_15") (pintype "bidirectional"))
      (node (ref "OUTPUT_BUFFER_REG_A") (pin "14") (pinfunction "B5_14") (pintype "bidirectional"))
      (node (ref "OUT_REG_LOWER") (pin "14") (pinfunction "D1_14") (pintype "input"))
      (node (ref "PROGRAM_COUNTER_LOWER") (pin "6") (pinfunction "6_6") (pintype "passive"))
      (node (ref "RAM_ADDR_LOWER") (pin "11") (pinfunction "D4_11") (pintype "input"))
      (node (ref "REG_A_LOWER") (pin "14") (pinfunction "D1_14") (pintype "input"))
      (node (ref "REG_CALC_LOWER") (pin "14") (pinfunction "D1_14") (pintype "input"))
      (node (ref "REG_PARAM_LOWER") (pin "14") (pinfunction "D1_14") (pintype "input"))
      (node (ref "XOR_GATE_1") (pin "13") (pinfunction "I1_13") (pintype "input"))
    )
    (net (code "37") (name "Net-(ADDR_MEM_REG_LOWERA-D2)") (class "Default")
      (node (ref "ADDR_MEM_REG_LOWER") (pin "13") (pinfunction "D2_13") (pintype "input"))
      (node (ref "DATABUS_3") (pin "A") (pinfunction "A_A") (pintype "passive"))
      (node (ref "EXTENSION") (pin "3") (pinfunction "1_3") (pintype "passive"))
      (node (ref "FIFO_STACK") (pin "11") (pinfunction "11_11") (pintype "passive"))
      (node (ref "FIFO_STACK") (pin "4") (pinfunction "4_4") (pintype "passive"))
      (node (ref "INSTRUC_REGISTER_LOWER") (pin "13") (pinfunction "D2_13") (pintype "input"))
      (node (ref "MICRO_COUNTER_LOWER") (pin "5") (pinfunction "5_5") (pintype "passive"))
      (node (ref "OUTPUT_BUFFER_ALU") (pin "4") (pinfunction "A3_4") (pintype "bidirectional"))
      (node (ref "OUTPUT_BUFFER_CALC_REG") (pin "13") (pinfunction "B6_13") (pintype "bidirectional"))
      (node (ref "OUTPUT_BUFFER_FLAGS") (pin "4") (pinfunction "A3_4") (pintype "bidirectional"))
      (node (ref "OUTPUT_BUFFER_INSTRUCTION") (pin "13") (pinfunction "B6_13") (pintype "bidirectional"))
      (node (ref "OUTPUT_BUFFER_KEYBOARD") (pin "4") (pinfunction "A3_4") (pintype "bidirectional"))
      (node (ref "OUTPUT_BUFFER_MEMORY") (pin "13") (pinfunction "B6_13") (pintype "bidirectional"))
      (node (ref "OUTPUT_BUFFER_PARAM_REG") (pin "13") (pinfunction "B6_13") (pintype "bidirectional"))
      (node (ref "OUTPUT_BUFFER_PC") (pin "13") (pinfunction "B6_13") (pintype "bidirectional"))
      (node (ref "OUTPUT_BUFFER_RAM") (pin "16") (pinfunction "B3_16") (pintype "bidirectional"))
      (node (ref "OUTPUT_BUFFER_REG_A") (pin "13") (pinfunction "B6_13") (pintype "bidirectional"))
      (node (ref "OUT_REG_LOWER") (pin "13") (pinfunction "D2_13") (pintype "input"))
      (node (ref "PROGRAM_COUNTER_LOWER") (pin "5") (pinfunction "5_5") (pintype "passive"))
      (node (ref "RAM_ADDR_LOWER") (pin "12") (pinfunction "D3_12") (pintype "input"))
      (node (ref "REG_A_LOWER") (pin "13") (pinfunction "D2_13") (pintype "input"))
      (node (ref "REG_CALC_LOWER") (pin "13") (pinfunction "D2_13") (pintype "input"))
      (node (ref "REG_PARAM_LOWER") (pin "13") (pinfunction "D2_13") (pintype "input"))
      (node (ref "XOR_GATE_1") (pin "10") (pinfunction "I1_10") (pintype "input"))
    )
    (net (code "38") (name "Net-(ADDR_MEM_REG_LOWERA-D3)") (class "Default")
      (node (ref "ADDR_MEM_REG_LOWER") (pin "12") (pinfunction "D3_12") (pintype "input"))
      (node (ref "DATABUS_2") (pin "A") (pinfunction "A_A") (pintype "passive"))
      (node (ref "EXTENSION") (pin "2") (pinfunction "1_2") (pintype "passive"))
      (node (ref "FIFO_STACK") (pin "10") (pinfunction "10_10") (pintype "passive"))
      (node (ref "FIFO_STACK") (pin "5") (pinfunction "5_5") (pintype "passive"))
      (node (ref "INSTRUC_REGISTER_LOWER") (pin "12") (pinfunction "D3_12") (pintype "input"))
      (node (ref "MICRO_COUNTER_LOWER") (pin "4") (pinfunction "4_4") (pintype "passive"))
      (node (ref "OUTPUT_BUFFER_ALU") (pin "3") (pinfunction "A2_3") (pintype "bidirectional"))
      (node (ref "OUTPUT_BUFFER_CALC_REG") (pin "12") (pinfunction "B7_12") (pintype "bidirectional"))
      (node (ref "OUTPUT_BUFFER_FLAGS") (pin "3") (pinfunction "A2_3") (pintype "bidirectional"))
      (node (ref "OUTPUT_BUFFER_INSTRUCTION") (pin "12") (pinfunction "B7_12") (pintype "bidirectional"))
      (node (ref "OUTPUT_BUFFER_KEYBOARD") (pin "3") (pinfunction "A2_3") (pintype "bidirectional"))
      (node (ref "OUTPUT_BUFFER_MEMORY") (pin "12") (pinfunction "B7_12") (pintype "bidirectional"))
      (node (ref "OUTPUT_BUFFER_PARAM_REG") (pin "12") (pinfunction "B7_12") (pintype "bidirectional"))
      (node (ref "OUTPUT_BUFFER_PC") (pin "12") (pinfunction "B7_12") (pintype "bidirectional"))
      (node (ref "OUTPUT_BUFFER_RAM") (pin "17") (pinfunction "B2_17") (pintype "bidirectional"))
      (node (ref "OUTPUT_BUFFER_REG_A") (pin "12") (pinfunction "B7_12") (pintype "bidirectional"))
      (node (ref "OUT_REG_LOWER") (pin "12") (pinfunction "D3_12") (pintype "input"))
      (node (ref "PROGRAM_COUNTER_LOWER") (pin "4") (pinfunction "4_4") (pintype "passive"))
      (node (ref "RAM_ADDR_LOWER") (pin "13") (pinfunction "D2_13") (pintype "input"))
      (node (ref "REG_A_LOWER") (pin "12") (pinfunction "D3_12") (pintype "input"))
      (node (ref "REG_CALC_LOWER") (pin "12") (pinfunction "D3_12") (pintype "input"))
      (node (ref "REG_PARAM_LOWER") (pin "12") (pinfunction "D3_12") (pintype "input"))
      (node (ref "XOR_GATE_1") (pin "5") (pinfunction "I1_5") (pintype "input"))
    )
    (net (code "39") (name "Net-(ADDR_MEM_REG_LOWERA-D4)") (class "Default")
      (node (ref "ADDR_MEM_REG_LOWER") (pin "11") (pinfunction "D4_11") (pintype "input"))
      (node (ref "DATABUS_1") (pin "A") (pinfunction "A_A") (pintype "passive"))
      (node (ref "EXTENSION") (pin "1") (pinfunction "1_1") (pintype "passive"))
      (node (ref "FIFO_STACK") (pin "6") (pinfunction "6_6") (pintype "passive"))
      (node (ref "FIFO_STACK") (pin "9") (pinfunction "9_9") (pintype "passive"))
      (node (ref "INSTRUC_REGISTER_LOWER") (pin "11") (pinfunction "D4_11") (pintype "input"))
      (node (ref "MICRO_COUNTER_LOWER") (pin "3") (pinfunction "3_3") (pintype "passive"))
      (node (ref "OUTPUT_BUFFER_ALU") (pin "2") (pinfunction "A1_2") (pintype "bidirectional"))
      (node (ref "OUTPUT_BUFFER_CALC_REG") (pin "11") (pinfunction "B8_11") (pintype "bidirectional"))
      (node (ref "OUTPUT_BUFFER_FLAGS") (pin "2") (pinfunction "A1_2") (pintype "bidirectional"))
      (node (ref "OUTPUT_BUFFER_INSTRUCTION") (pin "11") (pinfunction "B8_11") (pintype "bidirectional"))
      (node (ref "OUTPUT_BUFFER_KEYBOARD") (pin "2") (pinfunction "A1_2") (pintype "bidirectional"))
      (node (ref "OUTPUT_BUFFER_MEMORY") (pin "11") (pinfunction "B8_11") (pintype "bidirectional"))
      (node (ref "OUTPUT_BUFFER_PARAM_REG") (pin "11") (pinfunction "B8_11") (pintype "bidirectional"))
      (node (ref "OUTPUT_BUFFER_PC") (pin "11") (pinfunction "B8_11") (pintype "bidirectional"))
      (node (ref "OUTPUT_BUFFER_RAM") (pin "18") (pinfunction "B1_18") (pintype "bidirectional"))
      (node (ref "OUTPUT_BUFFER_REG_A") (pin "11") (pinfunction "B8_11") (pintype "bidirectional"))
      (node (ref "OUT_REG_LOWER") (pin "11") (pinfunction "D4_11") (pintype "input"))
      (node (ref "PROGRAM_COUNTER_LOWER") (pin "3") (pinfunction "3_3") (pintype "passive"))
      (node (ref "RAM_ADDR_LOWER") (pin "14") (pinfunction "D1_14") (pintype "input"))
      (node (ref "REG_A_LOWER") (pin "11") (pinfunction "D4_11") (pintype "input"))
      (node (ref "REG_CALC_LOWER") (pin "11") (pinfunction "D4_11") (pintype "input"))
      (node (ref "REG_PARAM_LOWER") (pin "11") (pinfunction "D4_11") (pintype "input"))
      (node (ref "XOR_GATE_1") (pin "2") (pinfunction "I1_2") (pintype "input"))
    )
    (net (code "40") (name "Net-(ADDR_MEM_REG_LOWERA-G1)") (class "Default")
      (node (ref "ADDR_MEM_REG_LOWER") (pin "10") (pinfunction "G2_10") (pintype "input"))
      (node (ref "ADDR_MEM_REG_LOWER") (pin "9") (pinfunction "G1_9") (pintype "input"))
      (node (ref "ADDR_MEM_REG_UPPER") (pin "10") (pinfunction "G2_10") (pintype "input"))
      (node (ref "ADDR_MEM_REG_UPPER") (pin "9") (pinfunction "G1_9") (pintype "input"))
      (node (ref "NOT_GATE1_") (pin "6") (pinfunction "O_6") (pintype "output"))
    )
    (net (code "41") (name "Net-(ADDR_MEM_REG_LOWERA-Q1)") (class "Default")
      (node (ref "ADDR_MEM_REG_LOWER") (pin "3") (pinfunction "Q1_3") (pintype "tri_state"))
      (node (ref "MEMORY") (pin "7") (pinfunction "7_7") (pintype "passive"))
    )
    (net (code "42") (name "Net-(ADDR_MEM_REG_LOWERA-Q2)") (class "Default")
      (node (ref "ADDR_MEM_REG_LOWER") (pin "4") (pinfunction "Q2_4") (pintype "tri_state"))
      (node (ref "MEMORY") (pin "8") (pinfunction "8_8") (pintype "passive"))
    )
    (net (code "43") (name "Net-(ADDR_MEM_REG_LOWERA-Q3)") (class "Default")
      (node (ref "ADDR_MEM_REG_LOWER") (pin "5") (pinfunction "Q3_5") (pintype "tri_state"))
      (node (ref "MEMORY") (pin "9") (pinfunction "9_9") (pintype "passive"))
    )
    (net (code "44") (name "Net-(ADDR_MEM_REG_LOWERA-Q4)") (class "Default")
      (node (ref "ADDR_MEM_REG_LOWER") (pin "6") (pinfunction "Q4_6") (pintype "tri_state"))
      (node (ref "MEMORY") (pin "10") (pinfunction "10_10") (pintype "passive"))
    )
    (net (code "45") (name "Net-(ADDR_MEM_REG_UPPERA-D1)") (class "Default")
      (node (ref "ADDR_MEM_REG_UPPER") (pin "14") (pinfunction "D1_14") (pintype "input"))
      (node (ref "DATABUS_8") (pin "A") (pinfunction "A_A") (pintype "passive"))
      (node (ref "EXTENSION") (pin "8") (pinfunction "1_8") (pintype "passive"))
      (node (ref "FIFO_STACK") (pin "19") (pinfunction "19_19") (pintype "passive"))
      (node (ref "FIFO_STACK") (pin "24") (pinfunction "24_24") (pintype "passive"))
      (node (ref "INSTRUC_REGISTER_UPPER") (pin "14") (pinfunction "D1_14") (pintype "input"))
      (node (ref "OUTPUT_BUFFER_ALU") (pin "9") (pinfunction "A8_9") (pintype "bidirectional"))
      (node (ref "OUTPUT_BUFFER_CALC_REG") (pin "18") (pinfunction "B1_18") (pintype "bidirectional"))
      (node (ref "OUTPUT_BUFFER_FLAGS") (pin "9") (pinfunction "A8_9") (pintype "bidirectional"))
      (node (ref "OUTPUT_BUFFER_INSTRUCTION") (pin "18") (pinfunction "B1_18") (pintype "bidirectional"))
      (node (ref "OUTPUT_BUFFER_KEYBOARD") (pin "9") (pinfunction "A8_9") (pintype "bidirectional"))
      (node (ref "OUTPUT_BUFFER_MEMORY") (pin "18") (pinfunction "B1_18") (pintype "bidirectional"))
      (node (ref "OUTPUT_BUFFER_PARAM_REG") (pin "18") (pinfunction "B1_18") (pintype "bidirectional"))
      (node (ref "OUTPUT_BUFFER_PC") (pin "18") (pinfunction "B1_18") (pintype "bidirectional"))
      (node (ref "OUTPUT_BUFFER_RAM") (pin "11") (pinfunction "B8_11") (pintype "bidirectional"))
      (node (ref "OUTPUT_BUFFER_REG_A") (pin "18") (pinfunction "B1_18") (pintype "bidirectional"))
      (node (ref "OUT_REG_UPPER") (pin "14") (pinfunction "D1_14") (pintype "input"))
      (node (ref "PROGRAM_COUNTER_UPPER") (pin "6") (pinfunction "6_6") (pintype "passive"))
      (node (ref "RAM_ADDR_UPPER") (pin "11") (pinfunction "D4_11") (pintype "input"))
      (node (ref "REG_A_UPPER") (pin "14") (pinfunction "D1_14") (pintype "input"))
      (node (ref "REG_CALC_UPPER") (pin "14") (pinfunction "D1_14") (pintype "input"))
      (node (ref "REG_PARAM_UPPER") (pin "14") (pinfunction "D1_14") (pintype "input"))
    )
    (net (code "46") (name "Net-(ADDR_MEM_REG_UPPERA-D2)") (class "Default")
      (node (ref "ADDR_MEM_REG_UPPER") (pin "13") (pinfunction "D2_13") (pintype "input"))
      (node (ref "DATABUS_7") (pin "A") (pinfunction "A_A") (pintype "passive"))
      (node (ref "EXTENSION") (pin "7") (pinfunction "1_7") (pintype "passive"))
      (node (ref "FIFO_STACK") (pin "18") (pinfunction "18_18") (pintype "passive"))
      (node (ref "FIFO_STACK") (pin "25") (pinfunction "25_25") (pintype "passive"))
      (node (ref "INSTRUC_REGISTER_UPPER") (pin "13") (pinfunction "D2_13") (pintype "input"))
      (node (ref "OUTPUT_BUFFER_ALU") (pin "8") (pinfunction "A7_8") (pintype "bidirectional"))
      (node (ref "OUTPUT_BUFFER_CALC_REG") (pin "17") (pinfunction "B2_17") (pintype "bidirectional"))
      (node (ref "OUTPUT_BUFFER_FLAGS") (pin "8") (pinfunction "A7_8") (pintype "bidirectional"))
      (node (ref "OUTPUT_BUFFER_INSTRUCTION") (pin "17") (pinfunction "B2_17") (pintype "bidirectional"))
      (node (ref "OUTPUT_BUFFER_KEYBOARD") (pin "8") (pinfunction "A7_8") (pintype "bidirectional"))
      (node (ref "OUTPUT_BUFFER_MEMORY") (pin "17") (pinfunction "B2_17") (pintype "bidirectional"))
      (node (ref "OUTPUT_BUFFER_PARAM_REG") (pin "17") (pinfunction "B2_17") (pintype "bidirectional"))
      (node (ref "OUTPUT_BUFFER_PC") (pin "17") (pinfunction "B2_17") (pintype "bidirectional"))
      (node (ref "OUTPUT_BUFFER_RAM") (pin "12") (pinfunction "B7_12") (pintype "bidirectional"))
      (node (ref "OUTPUT_BUFFER_REG_A") (pin "17") (pinfunction "B2_17") (pintype "bidirectional"))
      (node (ref "OUT_REG_UPPER") (pin "13") (pinfunction "D2_13") (pintype "input"))
      (node (ref "PROGRAM_COUNTER_UPPER") (pin "5") (pinfunction "5_5") (pintype "passive"))
      (node (ref "RAM_ADDR_UPPER") (pin "12") (pinfunction "D3_12") (pintype "input"))
      (node (ref "REG_A_UPPER") (pin "13") (pinfunction "D2_13") (pintype "input"))
      (node (ref "REG_CALC_UPPER") (pin "13") (pinfunction "D2_13") (pintype "input"))
      (node (ref "REG_PARAM_UPPER") (pin "13") (pinfunction "D2_13") (pintype "input"))
      (node (ref "XOR_GATE_2") (pin "10") (pinfunction "I1_10") (pintype "input"))
    )
    (net (code "47") (name "Net-(ADDR_MEM_REG_UPPERA-D3)") (class "Default")
      (node (ref "ADDR_MEM_REG_UPPER") (pin "12") (pinfunction "D3_12") (pintype "input"))
      (node (ref "DATABUS_6") (pin "A") (pinfunction "A_A") (pintype "passive"))
      (node (ref "EXTENSION") (pin "6") (pinfunction "1_6") (pintype "passive"))
      (node (ref "FIFO_STACK") (pin "17") (pinfunction "17_17") (pintype "passive"))
      (node (ref "FIFO_STACK") (pin "26") (pinfunction "26_26") (pintype "passive"))
      (node (ref "INSTRUC_REGISTER_UPPER") (pin "12") (pinfunction "D3_12") (pintype "input"))
      (node (ref "OUTPUT_BUFFER_ALU") (pin "7") (pinfunction "A6_7") (pintype "bidirectional"))
      (node (ref "OUTPUT_BUFFER_CALC_REG") (pin "16") (pinfunction "B3_16") (pintype "bidirectional"))
      (node (ref "OUTPUT_BUFFER_FLAGS") (pin "7") (pinfunction "A6_7") (pintype "bidirectional"))
      (node (ref "OUTPUT_BUFFER_INSTRUCTION") (pin "16") (pinfunction "B3_16") (pintype "bidirectional"))
      (node (ref "OUTPUT_BUFFER_KEYBOARD") (pin "7") (pinfunction "A6_7") (pintype "bidirectional"))
      (node (ref "OUTPUT_BUFFER_MEMORY") (pin "16") (pinfunction "B3_16") (pintype "bidirectional"))
      (node (ref "OUTPUT_BUFFER_PARAM_REG") (pin "16") (pinfunction "B3_16") (pintype "bidirectional"))
      (node (ref "OUTPUT_BUFFER_PC") (pin "16") (pinfunction "B3_16") (pintype "bidirectional"))
      (node (ref "OUTPUT_BUFFER_RAM") (pin "13") (pinfunction "B6_13") (pintype "bidirectional"))
      (node (ref "OUTPUT_BUFFER_REG_A") (pin "16") (pinfunction "B3_16") (pintype "bidirectional"))
      (node (ref "OUT_REG_UPPER") (pin "12") (pinfunction "D3_12") (pintype "input"))
      (node (ref "PROGRAM_COUNTER_UPPER") (pin "4") (pinfunction "4_4") (pintype "passive"))
      (node (ref "RAM_ADDR_UPPER") (pin "13") (pinfunction "D2_13") (pintype "input"))
      (node (ref "REG_A_UPPER") (pin "12") (pinfunction "D3_12") (pintype "input"))
      (node (ref "REG_CALC_UPPER") (pin "12") (pinfunction "D3_12") (pintype "input"))
      (node (ref "REG_PARAM_UPPER") (pin "12") (pinfunction "D3_12") (pintype "input"))
      (node (ref "XOR_GATE_2") (pin "5") (pinfunction "I1_5") (pintype "input"))
    )
    (net (code "48") (name "Net-(ADDR_MEM_REG_UPPERA-D4)") (class "Default")
      (node (ref "ADDR_MEM_REG_UPPER") (pin "11") (pinfunction "D4_11") (pintype "input"))
      (node (ref "DATABUS_5") (pin "A") (pinfunction "A_A") (pintype "passive"))
      (node (ref "EXTENSION") (pin "5") (pinfunction "1_5") (pintype "passive"))
      (node (ref "FIFO_STACK") (pin "16") (pinfunction "16_16") (pintype "passive"))
      (node (ref "FIFO_STACK") (pin "27") (pinfunction "27_27") (pintype "passive"))
      (node (ref "INSTRUC_REGISTER_UPPER") (pin "11") (pinfunction "D4_11") (pintype "input"))
      (node (ref "MICRO_COUNTER_UPPER") (pin "3") (pinfunction "3_3") (pintype "passive"))
      (node (ref "OUTPUT_BUFFER_ALU") (pin "6") (pinfunction "A5_6") (pintype "bidirectional"))
      (node (ref "OUTPUT_BUFFER_CALC_REG") (pin "15") (pinfunction "B4_15") (pintype "bidirectional"))
      (node (ref "OUTPUT_BUFFER_FLAGS") (pin "6") (pinfunction "A5_6") (pintype "bidirectional"))
      (node (ref "OUTPUT_BUFFER_INSTRUCTION") (pin "15") (pinfunction "B4_15") (pintype "bidirectional"))
      (node (ref "OUTPUT_BUFFER_KEYBOARD") (pin "6") (pinfunction "A5_6") (pintype "bidirectional"))
      (node (ref "OUTPUT_BUFFER_MEMORY") (pin "15") (pinfunction "B4_15") (pintype "bidirectional"))
      (node (ref "OUTPUT_BUFFER_PARAM_REG") (pin "15") (pinfunction "B4_15") (pintype "bidirectional"))
      (node (ref "OUTPUT_BUFFER_PC") (pin "15") (pinfunction "B4_15") (pintype "bidirectional"))
      (node (ref "OUTPUT_BUFFER_RAM") (pin "14") (pinfunction "B5_14") (pintype "bidirectional"))
      (node (ref "OUTPUT_BUFFER_REG_A") (pin "15") (pinfunction "B4_15") (pintype "bidirectional"))
      (node (ref "OUT_REG_UPPER") (pin "11") (pinfunction "D4_11") (pintype "input"))
      (node (ref "PROGRAM_COUNTER_UPPER") (pin "3") (pinfunction "3_3") (pintype "passive"))
      (node (ref "RAM_ADDR_UPPER") (pin "14") (pinfunction "D1_14") (pintype "input"))
      (node (ref "REG_A_UPPER") (pin "11") (pinfunction "D4_11") (pintype "input"))
      (node (ref "REG_CALC_UPPER") (pin "11") (pinfunction "D4_11") (pintype "input"))
      (node (ref "REG_PARAM_UPPER") (pin "11") (pinfunction "D4_11") (pintype "input"))
      (node (ref "XOR_GATE_2") (pin "2") (pinfunction "I1_2") (pintype "input"))
    )
    (net (code "49") (name "Net-(ADDR_MEM_REG_UPPERA-Q1)") (class "Default")
      (node (ref "ADDR_MEM_REG_UPPER") (pin "3") (pinfunction "Q1_3") (pintype "tri_state"))
      (node (ref "MEMORY") (pin "3") (pinfunction "3_3") (pintype "passive"))
    )
    (net (code "50") (name "Net-(ADDR_MEM_REG_UPPERA-Q2)") (class "Default")
      (node (ref "ADDR_MEM_REG_UPPER") (pin "4") (pinfunction "Q2_4") (pintype "tri_state"))
      (node (ref "MEMORY") (pin "4") (pinfunction "4_4") (pintype "passive"))
    )
    (net (code "51") (name "Net-(ADDR_MEM_REG_UPPERA-Q3)") (class "Default")
      (node (ref "ADDR_MEM_REG_UPPER") (pin "5") (pinfunction "Q3_5") (pintype "tri_state"))
      (node (ref "MEMORY") (pin "5") (pinfunction "5_5") (pintype "passive"))
    )
    (net (code "52") (name "Net-(ADDR_MEM_REG_UPPERA-Q4)") (class "Default")
      (node (ref "ADDR_MEM_REG_UPPER") (pin "6") (pinfunction "Q4_6") (pintype "tri_state"))
      (node (ref "MEMORY") (pin "6") (pinfunction "6_6") (pintype "passive"))
    )
    (net (code "53") (name "Net-(AND_GATE3_A-I1)") (class "Default")
      (node (ref "AND_GATE3_") (pin "2") (pinfunction "I1_2") (pintype "input"))
      (node (ref "NOT_GATE_") (pin "8") (pinfunction "O_8") (pintype "output"))
    )
    (net (code "54") (name "Net-(AND_GATE3_A-O)") (class "Default")
      (node (ref "AND_GATE3_") (pin "3") (pinfunction "O_3") (pintype "output"))
      (node (ref "NOT_GATE4_") (pin "5") (pinfunction "I_5") (pintype "input"))
    )
    (net (code "55") (name "Net-(AND_GATE3_B-I1)") (class "Default")
      (node (ref "AND_GATE3_") (pin "5") (pinfunction "I1_5") (pintype "input"))
      (node (ref "NOT_GATE4_") (pin "12") (pinfunction "O_12") (pintype "output"))
    )
    (net (code "56") (name "Net-(AND_GATE3_B-O)") (class "Default")
      (node (ref "AND_GATE3_") (pin "6") (pinfunction "O_6") (pintype "output"))
      (node (ref "NOT_GATE4_") (pin "9") (pinfunction "I_9") (pintype "input"))
    )
    (net (code "57") (name "Net-(AND_GATE3_C-I0)") (class "Default")
      (node (ref "AND_GATE3_") (pin "9") (pinfunction "I0_9") (pintype "input"))
      (node (ref "SELECTOR_LOGIC_") (pin "9") (pinfunction "Y3_9") (pintype "output"))
    )
    (net (code "58") (name "Net-(AND_GATE3_C-I1)") (class "Default")
      (node (ref "AND_GATE3_") (pin "10") (pinfunction "I1_10") (pintype "input"))
      (node (ref "PROGRAM_COUNTER_LOWER") (pin "1") (pinfunction "1_1") (pintype "passive"))
      (node (ref "PROGRAM_COUNTER_UPPER") (pin "1") (pinfunction "1_1") (pintype "passive"))
      (node (ref "R80") (pin "1") (pinfunction "1_1") (pintype "passive"))
      (node (ref "RESET_PC") (pin "1") (pinfunction "S_1") (pintype "passive"))
    )
    (net (code "59") (name "Net-(AND_GATE3_C-O)") (class "Default")
      (node (ref "AND_GATE3_") (pin "8") (pinfunction "O_8") (pintype "output"))
      (node (ref "MICRO_COUNTER_LOWER") (pin "1") (pinfunction "1_1") (pintype "passive"))
      (node (ref "MICRO_COUNTER_UPPER") (pin "1") (pinfunction "1_1") (pintype "passive"))
    )
    (net (code "60") (name "Net-(AND_GATE3_D-I0)") (class "Default")
      (node (ref "AND_GATE3_") (pin "12") (pinfunction "I0_12") (pintype "input"))
      (node (ref "NOT_GATE2_") (pin "8") (pinfunction "O_8") (pintype "output"))
    )
    (net (code "61") (name "Net-(AND_GATE4_A-I0)") (class "Default")
      (node (ref "AND_GATE4_") (pin "1") (pinfunction "I0_1") (pintype "input"))
      (node (ref "NOT_GATE2_") (pin "6") (pinfunction "O_6") (pintype "output"))
    )
    (net (code "62") (name "Net-(AND_GATE4_A-I1)") (class "Default")
      (node (ref "AND_GATE4_") (pin "2") (pinfunction "I1_2") (pintype "input"))
      (node (ref "ZERO_FLAG") (pin "A") (pinfunction "A_A") (pintype "passive"))
      (node (ref "ZERO_POS_FLAG_IDENTIFIER") (pin "13") (pinfunction "W_13") (pintype "output"))
    )
    (net (code "63") (name "Net-(AND_GATE4_B-I0)") (class "Default")
      (node (ref "AND_GATE4_") (pin "4") (pinfunction "I0_4") (pintype "input"))
      (node (ref "NOT_GATE1_") (pin "2") (pinfunction "O_2") (pintype "output"))
    )
    (net (code "64") (name "Net-(AND_GATE4_B-I1)") (class "Default")
      (node (ref "AND_GATE4_") (pin "5") (pinfunction "I1_5") (pintype "input"))
      (node (ref "POSITIVE_FLAG") (pin "A") (pinfunction "A_A") (pintype "passive"))
      (node (ref "ZERO_POS_FLAG_IDENTIFIER") (pin "1") (pinfunction "Y_1") (pintype "output"))
    )
    (net (code "65") (name "Net-(AND_GATE_A-I0)") (class "Default")
      (node (ref "AND_GATE_") (pin "1") (pinfunction "I0_1") (pintype "input"))
      (node (ref "AUTO_CLOCK") (pin "3") (pinfunction "Q_3") (pintype "output"))
    )
    (net (code "66") (name "Net-(AND_GATE_A-I1)") (class "Default")
      (node (ref "AND_GATE_") (pin "2") (pinfunction "I1_2") (pintype "input"))
      (node (ref "NOT_GATE1_") (pin "4") (pinfunction "O_4") (pintype "output"))
    )
    (net (code "67") (name "Net-(AND_GATE_A-O)") (class "Default")
      (node (ref "AND_GATE_") (pin "3") (pinfunction "O_3") (pintype "output"))
      (node (ref "OR_GATE_") (pin "1") (pinfunction "I0_1") (pintype "input"))
    )
    (net (code "68") (name "Net-(AND_GATE_B-I0)") (class "Default")
      (node (ref "AND_GATE_") (pin "4") (pinfunction "I0_4") (pintype "input"))
      (node (ref "CLK_MODE") (pin "1") (pinfunction "1_1") (pintype "passive"))
      (node (ref "NOT_GATE1_") (pin "3") (pinfunction "I_3") (pintype "input"))
      (node (ref "R4") (pin "2") (pinfunction "2_2") (pintype "passive"))
    )
    (net (code "69") (name "Net-(AND_GATE_B-I1)") (class "Default")
      (node (ref "AND_GATE_") (pin "5") (pinfunction "I1_5") (pintype "input"))
      (node (ref "STEPPER_CLOCK") (pin "3") (pinfunction "Q_3") (pintype "output"))
    )
    (net (code "70") (name "Net-(AND_GATE_B-O)") (class "Default")
      (node (ref "AND_GATE_") (pin "6") (pinfunction "O_6") (pintype "output"))
      (node (ref "OR_GATE_") (pin "2") (pinfunction "I1_2") (pintype "input"))
    )
    (net (code "71") (name "Net-(AND_GATE_C-I0)") (class "Default")
      (node (ref "AND_GATE_") (pin "9") (pinfunction "I0_9") (pintype "input"))
      (node (ref "NOR_GATE_") (pin "4") (pinfunction "O_4") (pintype "output"))
    )
    (net (code "72") (name "Net-(AND_GATE_C-I1)") (class "Default")
      (node (ref "AND_GATE_") (pin "10") (pinfunction "I1_10") (pintype "input"))
      (node (ref "OR_GATE_") (pin "3") (pinfunction "O_3") (pintype "output"))
    )
    (net (code "73") (name "Net-(AND_GATE_D-I0)") (class "Default")
      (node (ref "AND_GATE_") (pin "12") (pinfunction "I0_12") (pintype "input"))
      (node (ref "NOR_GATE_") (pin "1") (pinfunction "O_1") (pintype "output"))
    )
    (net (code "74") (name "Net-(AND_GATE_D-I1)") (class "Default")
      (node (ref "AND_GATE_") (pin "13") (pinfunction "I1_13") (pintype "input"))
      (node (ref "SELECTOR_PARAM_") (pin "7") (pinfunction "Y3_7") (pintype "output"))
      (node (ref "XOR_GATE_2") (pin "13") (pinfunction "I1_13") (pintype "input"))
    )
    (net (code "75") (name "Net-(AND_GATE_D-O)") (class "Default")
      (node (ref "AND_GATE_") (pin "11") (pinfunction "O_11") (pintype "output"))
      (node (ref "XOR_GATE_2") (pin "12") (pinfunction "I0_12") (pintype "input"))
    )
    (net (code "76") (name "Net-(AUTO_CLOCK-DIS)") (class "Default")
      (node (ref "AUTO_CLOCK") (pin "7") (pinfunction "DIS_7") (pintype "input"))
      (node (ref "FREQUENCY") (pin "E") (pinfunction "E_E") (pintype "passive"))
      (node (ref "R1") (pin "2") (pinfunction "2_2") (pintype "passive"))
    )
    (net (code "77") (name "Net-(AUTO_CLOCK-THR)") (class "Default")
      (node (ref "AUTO_CLOCK") (pin "2") (pinfunction "TR_2") (pintype "input"))
      (node (ref "AUTO_CLOCK") (pin "6") (pinfunction "THR_6") (pintype "input"))
      (node (ref "C1") (pin "+") (pinfunction "+_+") (pintype "passive"))
      (node (ref "R7") (pin "2") (pinfunction "2_2") (pintype "passive"))
    )
    (net (code "78") (name "Net-(CLK_TRIGGER-S1)") (class "Default")
      (node (ref "CLK_TRIGGER") (pin "2") (pinfunction "S1_2") (pintype "passive"))
      (node (ref "R2") (pin "2") (pinfunction "2_2") (pintype "passive"))
      (node (ref "STEPPER_CLOCK") (pin "2") (pinfunction "TR_2") (pintype "input"))
    )
    (net (code "79") (name "Net-(CLOCK-C)") (class "Default")
      (node (ref "CLOCK") (pin "K") (pinfunction "C_K") (pintype "passive"))
      (node (ref "R5") (pin "2") (pinfunction "2_2") (pintype "passive"))
    )
    (net (code "80") (name "Net-(DATABUS_1-C)") (class "Default")
      (node (ref "DATABUS_1") (pin "K") (pinfunction "C_K") (pintype "passive"))
      (node (ref "R24") (pin "1") (pinfunction "1_1") (pintype "passive"))
    )
    (net (code "81") (name "Net-(DATABUS_2-C)") (class "Default")
      (node (ref "DATABUS_2") (pin "K") (pinfunction "C_K") (pintype "passive"))
      (node (ref "R25") (pin "1") (pinfunction "1_1") (pintype "passive"))
    )
    (net (code "82") (name "Net-(DATABUS_3-C)") (class "Default")
      (node (ref "DATABUS_3") (pin "K") (pinfunction "C_K") (pintype "passive"))
      (node (ref "R26") (pin "1") (pinfunction "1_1") (pintype "passive"))
    )
    (net (code "83") (name "Net-(DATABUS_4-C)") (class "Default")
      (node (ref "DATABUS_4") (pin "K") (pinfunction "C_K") (pintype "passive"))
      (node (ref "R27") (pin "1") (pinfunction "1_1") (pintype "passive"))
    )
    (net (code "84") (name "Net-(DATABUS_5-C)") (class "Default")
      (node (ref "DATABUS_5") (pin "K") (pinfunction "C_K") (pintype "passive"))
      (node (ref "R28") (pin "1") (pinfunction "1_1") (pintype "passive"))
    )
    (net (code "85") (name "Net-(DATABUS_6-C)") (class "Default")
      (node (ref "DATABUS_6") (pin "K") (pinfunction "C_K") (pintype "passive"))
      (node (ref "R29") (pin "1") (pinfunction "1_1") (pintype "passive"))
    )
    (net (code "86") (name "Net-(DATABUS_7-C)") (class "Default")
      (node (ref "DATABUS_7") (pin "K") (pinfunction "C_K") (pintype "passive"))
      (node (ref "R30") (pin "1") (pinfunction "1_1") (pintype "passive"))
    )
    (net (code "87") (name "Net-(DATABUS_8-C)") (class "Default")
      (node (ref "DATABUS_8") (pin "K") (pinfunction "C_K") (pintype "passive"))
      (node (ref "R31") (pin "1") (pinfunction "1_1") (pintype "passive"))
    )
    (net (code "88") (name "Net-(FLAG_1-C)") (class "Default")
      (node (ref "FLAG_1") (pin "K") (pinfunction "C_K") (pintype "passive"))
      (node (ref "R15") (pin "2") (pinfunction "2_2") (pintype "passive"))
    )
    (net (code "89") (name "Net-(FLAG_2-C)") (class "Default")
      (node (ref "FLAG_2") (pin "K") (pinfunction "C_K") (pintype "passive"))
      (node (ref "R77") (pin "2") (pinfunction "2_2") (pintype "passive"))
    )
    (net (code "90") (name "Net-(FLAG_3-C)") (class "Default")
      (node (ref "FLAG_3") (pin "K") (pinfunction "C_K") (pintype "passive"))
      (node (ref "R78") (pin "2") (pinfunction "2_2") (pintype "passive"))
    )
    (net (code "91") (name "Net-(FLAG_4-C)") (class "Default")
      (node (ref "FLAG_4") (pin "K") (pinfunction "C_K") (pintype "passive"))
      (node (ref "R79") (pin "2") (pinfunction "2_2") (pintype "passive"))
    )
    (net (code "92") (name "Net-(FLAG_5-C)") (class "Default")
      (node (ref "FLAG_5") (pin "K") (pinfunction "C_K") (pintype "passive"))
      (node (ref "R11") (pin "2") (pinfunction "2_2") (pintype "passive"))
    )
    (net (code "93") (name "Net-(FLAG_6-C)") (class "Default")
      (node (ref "FLAG_6") (pin "K") (pinfunction "C_K") (pintype "passive"))
      (node (ref "R10") (pin "2") (pinfunction "2_2") (pintype "passive"))
    )
    (net (code "94") (name "Net-(FLAG_7-C)") (class "Default")
      (node (ref "FLAG_7") (pin "K") (pinfunction "C_K") (pintype "passive"))
      (node (ref "R9") (pin "2") (pinfunction "2_2") (pintype "passive"))
    )
    (net (code "95") (name "Net-(FLAG_8-C)") (class "Default")
      (node (ref "FLAG_8") (pin "K") (pinfunction "C_K") (pintype "passive"))
      (node (ref "R8") (pin "2") (pinfunction "2_2") (pintype "passive"))
    )
    (net (code "96") (name "Net-(FLAG_REG_LOWERA-D2)") (class "Default")
      (node (ref "FLAG_REG_LOWER") (pin "13") (pinfunction "D2_13") (pintype "input"))
      (node (ref "XOR_GATE_2") (pin "8") (pinfunction "O_8") (pintype "output"))
    )
    (net (code "97") (name "Net-(FLAG_REG_LOWERA-D3)") (class "Default")
      (node (ref "FLAG_REG_LOWER") (pin "12") (pinfunction "D3_12") (pintype "input"))
      (node (ref "XOR_GATE_2") (pin "6") (pinfunction "O_6") (pintype "output"))
    )
    (net (code "98") (name "Net-(FLAG_REG_LOWERA-D4)") (class "Default")
      (node (ref "FLAG_REG_LOWER") (pin "11") (pinfunction "D4_11") (pintype "input"))
      (node (ref "XOR_GATE_2") (pin "3") (pinfunction "O_3") (pintype "output"))
    )
    (net (code "99") (name "Net-(FLAG_REG_LOWERA-G1)") (class "Default")
      (node (ref "FLAG_REG_LOWER") (pin "10") (pinfunction "G2_10") (pintype "input"))
      (node (ref "FLAG_REG_LOWER") (pin "9") (pinfunction "G1_9") (pintype "input"))
      (node (ref "FLAG_REG_UPPER") (pin "10") (pinfunction "G2_10") (pintype "input"))
      (node (ref "FLAG_REG_UPPER") (pin "9") (pinfunction "G1_9") (pintype "input"))
      (node (ref "NOT_GATE1_") (pin "12") (pinfunction "O_12") (pintype "output"))
    )
    (net (code "100") (name "Net-(FLAG_REG_LOWERA-Q1)") (class "Default")
      (node (ref "FLAG_8") (pin "A") (pinfunction "A_A") (pintype "passive"))
      (node (ref "FLAG_REG_LOWER") (pin "3") (pinfunction "Q1_3") (pintype "tri_state"))
      (node (ref "OUTPUT_BUFFER_FLAGS") (pin "11") (pinfunction "B8_11") (pintype "bidirectional"))
    )
    (net (code "101") (name "Net-(FLAG_REG_LOWERA-Q2)") (class "Default")
      (node (ref "FLAG_7") (pin "A") (pinfunction "A_A") (pintype "passive"))
      (node (ref "FLAG_REG_LOWER") (pin "4") (pinfunction "Q2_4") (pintype "tri_state"))
      (node (ref "OUTPUT_BUFFER_FLAGS") (pin "12") (pinfunction "B7_12") (pintype "bidirectional"))
      (node (ref "XOR_GATE_2") (pin "9") (pinfunction "I0_9") (pintype "input"))
    )
    (net (code "102") (name "Net-(FLAG_REG_LOWERA-Q3)") (class "Default")
      (node (ref "FLAG_6") (pin "A") (pinfunction "A_A") (pintype "passive"))
      (node (ref "FLAG_REG_LOWER") (pin "5") (pinfunction "Q3_5") (pintype "tri_state"))
      (node (ref "OUTPUT_BUFFER_FLAGS") (pin "13") (pinfunction "B6_13") (pintype "bidirectional"))
      (node (ref "XOR_GATE_2") (pin "4") (pinfunction "I0_4") (pintype "input"))
    )
    (net (code "103") (name "Net-(FLAG_REG_LOWERA-Q4)") (class "Default")
      (node (ref "FLAG_5") (pin "A") (pinfunction "A_A") (pintype "passive"))
      (node (ref "FLAG_REG_LOWER") (pin "6") (pinfunction "Q4_6") (pintype "tri_state"))
      (node (ref "OUTPUT_BUFFER_FLAGS") (pin "14") (pinfunction "B5_14") (pintype "bidirectional"))
      (node (ref "XOR_GATE_2") (pin "1") (pinfunction "I0_1") (pintype "input"))
    )
    (net (code "104") (name "Net-(FLAG_REG_UPPERA-D1)") (class "Default")
      (node (ref "FLAG_REG_UPPER") (pin "14") (pinfunction "D1_14") (pintype "input"))
      (node (ref "XOR_GATE_1") (pin "11") (pinfunction "O_11") (pintype "output"))
    )
    (net (code "105") (name "Net-(FLAG_REG_UPPERA-D2)") (class "Default")
      (node (ref "FLAG_REG_UPPER") (pin "13") (pinfunction "D2_13") (pintype "input"))
      (node (ref "XOR_GATE_1") (pin "8") (pinfunction "O_8") (pintype "output"))
    )
    (net (code "106") (name "Net-(FLAG_REG_UPPERA-D3)") (class "Default")
      (node (ref "FLAG_REG_UPPER") (pin "12") (pinfunction "D3_12") (pintype "input"))
      (node (ref "XOR_GATE_1") (pin "6") (pinfunction "O_6") (pintype "output"))
    )
    (net (code "107") (name "Net-(FLAG_REG_UPPERA-D4)") (class "Default")
      (node (ref "FLAG_REG_UPPER") (pin "11") (pinfunction "D4_11") (pintype "input"))
      (node (ref "XOR_GATE_1") (pin "3") (pinfunction "O_3") (pintype "output"))
    )
    (net (code "108") (name "Net-(FLAG_REG_UPPERA-Q1)") (class "Default")
      (node (ref "FLAG_4") (pin "A") (pinfunction "A_A") (pintype "passive"))
      (node (ref "FLAG_REG_UPPER") (pin "3") (pinfunction "Q1_3") (pintype "tri_state"))
      (node (ref "OUTPUT_BUFFER_FLAGS") (pin "15") (pinfunction "B4_15") (pintype "bidirectional"))
      (node (ref "XOR_GATE_1") (pin "12") (pinfunction "I0_12") (pintype "input"))
    )
    (net (code "109") (name "Net-(FLAG_REG_UPPERA-Q2)") (class "Default")
      (node (ref "FLAG_3") (pin "A") (pinfunction "A_A") (pintype "passive"))
      (node (ref "FLAG_REG_UPPER") (pin "4") (pinfunction "Q2_4") (pintype "tri_state"))
      (node (ref "OUTPUT_BUFFER_FLAGS") (pin "16") (pinfunction "B3_16") (pintype "bidirectional"))
      (node (ref "XOR_GATE_1") (pin "9") (pinfunction "I0_9") (pintype "input"))
    )
    (net (code "110") (name "Net-(FLAG_REG_UPPERA-Q3)") (class "Default")
      (node (ref "FLAG_2") (pin "A") (pinfunction "A_A") (pintype "passive"))
      (node (ref "FLAG_REG_UPPER") (pin "5") (pinfunction "Q3_5") (pintype "tri_state"))
      (node (ref "OUTPUT_BUFFER_FLAGS") (pin "17") (pinfunction "B2_17") (pintype "bidirectional"))
      (node (ref "XOR_GATE_1") (pin "4") (pinfunction "I0_4") (pintype "input"))
    )
    (net (code "111") (name "Net-(FLAG_REG_UPPERA-Q4)") (class "Default")
      (node (ref "FLAG_1") (pin "A") (pinfunction "A_A") (pintype "passive"))
      (node (ref "FLAG_REG_UPPER") (pin "6") (pinfunction "Q4_6") (pintype "tri_state"))
      (node (ref "MEMORY") (pin "25") (pinfunction "25_25") (pintype "passive"))
      (node (ref "OUTPUT_BUFFER_FLAGS") (pin "18") (pinfunction "B1_18") (pintype "bidirectional"))
      (node (ref "XOR_GATE_1") (pin "1") (pinfunction "I0_1") (pintype "input"))
    )
    (net (code "112") (name "Net-(FREQUENCY-PadS)") (class "Default")
      (node (ref "FREQUENCY") (pin "S") (pinfunction "S_S") (pintype "passive"))
      (node (ref "R7") (pin "1") (pinfunction "1_1") (pintype "passive"))
    )
    (net (code "113") (name "Net-(INSTRUCTIONS_EXTENSIONB-1)") (class "Default")
      (node (ref "INSTRUCTIONS_EXTENSION") (pin "10") (pinfunction "1_10") (pintype "passive"))
      (node (ref "INSTRUCTION_MEMORY_0") (pin "24") (pinfunction "24_24") (pintype "passive"))
      (node (ref "INSTRUCTION_MEMORY_1") (pin "24") (pinfunction "24_24") (pintype "passive"))
      (node (ref "INSTRUCTION_MEMORY_2") (pin "24") (pinfunction "24_24") (pintype "passive"))
      (node (ref "MICRO_COUNTER_LOWER") (pin "13") (pinfunction "13_13") (pintype "passive"))
      (node (ref "USTEP_2") (pin "A") (pinfunction "A_A") (pintype "passive"))
    )
    (net (code "114") (name "Net-(INSTRUCTIONS_EXTENSIONC-1)") (class "Default")
      (node (ref "INSTRUCTIONS_EXTENSION") (pin "11") (pinfunction "1_11") (pintype "passive"))
      (node (ref "INSTRUCTION_MEMORY_0") (pin "21") (pinfunction "21_21") (pintype "passive"))
      (node (ref "INSTRUCTION_MEMORY_1") (pin "21") (pinfunction "21_21") (pintype "passive"))
      (node (ref "INSTRUCTION_MEMORY_2") (pin "21") (pinfunction "21_21") (pintype "passive"))
      (node (ref "MICRO_COUNTER_LOWER") (pin "12") (pinfunction "12_12") (pintype "passive"))
      (node (ref "USTEP_4") (pin "A") (pinfunction "A_A") (pintype "passive"))
    )
    (net (code "115") (name "Net-(INSTRUCTIONS_EXTENSIOND-1)") (class "Default")
      (node (ref "INSTRUCTIONS_EXTENSION") (pin "12") (pinfunction "1_12") (pintype "passive"))
      (node (ref "INSTRUCTION_MEMORY_0") (pin "23") (pinfunction "23_23") (pintype "passive"))
      (node (ref "INSTRUCTION_MEMORY_1") (pin "23") (pinfunction "23_23") (pintype "passive"))
      (node (ref "INSTRUCTION_MEMORY_2") (pin "23") (pinfunction "23_23") (pintype "passive"))
      (node (ref "MICRO_COUNTER_LOWER") (pin "11") (pinfunction "11_11") (pintype "passive"))
      (node (ref "USTEP_3") (pin "A") (pinfunction "A_A") (pintype "passive"))
    )
    (net (code "116") (name "Net-(INSTRUCTIONS_EXTENSIONE-1)") (class "Default")
      (node (ref "INSTRUCTIONS_EXTENSION") (pin "13") (pinfunction "1_13") (pintype "passive"))
      (node (ref "INSTRUCTION_MEMORY_0") (pin "2") (pinfunction "2_2") (pintype "passive"))
      (node (ref "INSTRUCTION_MEMORY_1") (pin "2") (pinfunction "2_2") (pintype "passive"))
      (node (ref "INSTRUCTION_MEMORY_2") (pin "2") (pinfunction "2_2") (pintype "passive"))
      (node (ref "MICRO_COUNTER_UPPER") (pin "14") (pinfunction "14_14") (pintype "passive"))
      (node (ref "USTEP_5") (pin "A") (pinfunction "A_A") (pintype "passive"))
    )
    (net (code "117") (name "Net-(INSTRUCTIONS_EXTENSIONH-1)") (class "Default")
      (node (ref "INSTRUCTIONS_EXTENSION") (pin "2") (pinfunction "1_2") (pintype "passive"))
      (node (ref "INSTRUCTION_MEMORY_0") (pin "9") (pinfunction "9_9") (pintype "passive"))
      (node (ref "INSTRUCTION_MEMORY_1") (pin "9") (pinfunction "9_9") (pintype "passive"))
      (node (ref "INSTRUCTION_MEMORY_2") (pin "9") (pinfunction "9_9") (pintype "passive"))
      (node (ref "INSTRUC_REGISTER_LOWER") (pin "5") (pinfunction "Q3_5") (pintype "tri_state"))
    )
    (net (code "118") (name "Net-(INSTRUCTIONS_EXTENSIONI-1)") (class "Default")
      (node (ref "INSTRUCTIONS_EXTENSION") (pin "3") (pinfunction "1_3") (pintype "passive"))
      (node (ref "INSTRUCTION_MEMORY_0") (pin "8") (pinfunction "8_8") (pintype "passive"))
      (node (ref "INSTRUCTION_MEMORY_1") (pin "8") (pinfunction "8_8") (pintype "passive"))
      (node (ref "INSTRUCTION_MEMORY_2") (pin "8") (pinfunction "8_8") (pintype "passive"))
      (node (ref "INSTRUC_REGISTER_LOWER") (pin "4") (pinfunction "Q2_4") (pintype "tri_state"))
    )
    (net (code "119") (name "Net-(INSTRUCTIONS_EXTENSIONJ-1)") (class "Default")
      (node (ref "INSTRUCTIONS_EXTENSION") (pin "4") (pinfunction "1_4") (pintype "passive"))
      (node (ref "INSTRUCTION_MEMORY_0") (pin "7") (pinfunction "7_7") (pintype "passive"))
      (node (ref "INSTRUCTION_MEMORY_1") (pin "7") (pinfunction "7_7") (pintype "passive"))
      (node (ref "INSTRUCTION_MEMORY_2") (pin "7") (pinfunction "7_7") (pintype "passive"))
      (node (ref "INSTRUC_REGISTER_LOWER") (pin "3") (pinfunction "Q1_3") (pintype "tri_state"))
    )
    (net (code "120") (name "Net-(INSTRUCTIONS_EXTENSIONK-1)") (class "Default")
      (node (ref "INSTRUCTIONS_EXTENSION") (pin "5") (pinfunction "1_5") (pintype "passive"))
      (node (ref "INSTRUCTION_MEMORY_0") (pin "6") (pinfunction "6_6") (pintype "passive"))
      (node (ref "INSTRUCTION_MEMORY_1") (pin "6") (pinfunction "6_6") (pintype "passive"))
      (node (ref "INSTRUCTION_MEMORY_2") (pin "6") (pinfunction "6_6") (pintype "passive"))
      (node (ref "INSTRUC_REGISTER_UPPER") (pin "6") (pinfunction "Q4_6") (pintype "tri_state"))
    )
    (net (code "121") (name "Net-(INSTRUCTIONS_EXTENSIONL-1)") (class "Default")
      (node (ref "INSTRUCTIONS_EXTENSION") (pin "6") (pinfunction "1_6") (pintype "passive"))
      (node (ref "INSTRUCTION_MEMORY_0") (pin "5") (pinfunction "5_5") (pintype "passive"))
      (node (ref "INSTRUCTION_MEMORY_1") (pin "5") (pinfunction "5_5") (pintype "passive"))
      (node (ref "INSTRUCTION_MEMORY_2") (pin "5") (pinfunction "5_5") (pintype "passive"))
      (node (ref "INSTRUC_REGISTER_UPPER") (pin "5") (pinfunction "Q3_5") (pintype "tri_state"))
    )
    (net (code "122") (name "Net-(INSTRUCTIONS_EXTENSIONM-1)") (class "Default")
      (node (ref "INSTRUCTIONS_EXTENSION") (pin "7") (pinfunction "1_7") (pintype "passive"))
      (node (ref "INSTRUCTION_MEMORY_0") (pin "4") (pinfunction "4_4") (pintype "passive"))
      (node (ref "INSTRUCTION_MEMORY_1") (pin "4") (pinfunction "4_4") (pintype "passive"))
      (node (ref "INSTRUCTION_MEMORY_2") (pin "4") (pinfunction "4_4") (pintype "passive"))
      (node (ref "INSTRUC_REGISTER_UPPER") (pin "4") (pinfunction "Q2_4") (pintype "tri_state"))
    )
    (net (code "123") (name "Net-(INSTRUCTIONS_EXTENSIONN-1)") (class "Default")
      (node (ref "INSTRUCTIONS_EXTENSION") (pin "8") (pinfunction "1_8") (pintype "passive"))
      (node (ref "INSTRUCTION_MEMORY_0") (pin "3") (pinfunction "3_3") (pintype "passive"))
      (node (ref "INSTRUCTION_MEMORY_1") (pin "3") (pinfunction "3_3") (pintype "passive"))
      (node (ref "INSTRUCTION_MEMORY_2") (pin "3") (pinfunction "3_3") (pintype "passive"))
      (node (ref "INSTRUC_REGISTER_UPPER") (pin "3") (pinfunction "Q1_3") (pintype "tri_state"))
    )
    (net (code "124") (name "Net-(INSTRUCTIONS_EXTENSIONO-1)") (class "Default")
      (node (ref "INSTRUCTIONS_EXTENSION") (pin "9") (pinfunction "1_9") (pintype "passive"))
      (node (ref "INSTRUCTION_MEMORY_0") (pin "25") (pinfunction "25_25") (pintype "passive"))
      (node (ref "INSTRUCTION_MEMORY_1") (pin "25") (pinfunction "25_25") (pintype "passive"))
      (node (ref "INSTRUCTION_MEMORY_2") (pin "25") (pinfunction "25_25") (pintype "passive"))
      (node (ref "MICRO_COUNTER_LOWER") (pin "14") (pinfunction "14_14") (pintype "passive"))
      (node (ref "USTEP_1") (pin "A") (pinfunction "A_A") (pintype "passive"))
    )
    (net (code "125") (name "Net-(INSTRUC_REGISTER_LOWERA-G1)") (class "Default")
      (node (ref "INSTRUC_REGISTER_LOWER") (pin "10") (pinfunction "G2_10") (pintype "input"))
      (node (ref "INSTRUC_REGISTER_LOWER") (pin "9") (pinfunction "G1_9") (pintype "input"))
      (node (ref "INSTRUC_REGISTER_UPPER") (pin "10") (pinfunction "G2_10") (pintype "input"))
      (node (ref "INSTRUC_REGISTER_UPPER") (pin "9") (pinfunction "G1_9") (pintype "input"))
      (node (ref "SELECTOR_LOGIC_") (pin "5") (pinfunction "Y1_5") (pintype "output"))
    )
    (net (code "126") (name "Net-(INSTRUC_REGISTER_LOWERA-Q4)") (class "Default")
      (node (ref "INSTRUCTIONS_EXTENSION") (pin "1") (pinfunction "1_1") (pintype "passive"))
      (node (ref "INSTRUCTION_MEMORY_0") (pin "10") (pinfunction "10_10") (pintype "passive"))
      (node (ref "INSTRUCTION_MEMORY_1") (pin "10") (pinfunction "10_10") (pintype "passive"))
      (node (ref "INSTRUCTION_MEMORY_2") (pin "10") (pinfunction "10_10") (pintype "passive"))
      (node (ref "INSTRUC_REGISTER_LOWER") (pin "6") (pinfunction "Q4_6") (pintype "tri_state"))
    )
    (net (code "127") (name "Net-(INVERTED_CLK_LED-C)") (class "Default")
      (node (ref "INVERTED_CLK_LED") (pin "K") (pinfunction "C_K") (pintype "passive"))
      (node (ref "R45") (pin "2") (pinfunction "2_2") (pintype "passive"))
    )
    (net (code "128") (name "Net-(KEYBOARDB-1)") (class "Default")
      (node (ref "KEYBOARD") (pin "2") (pinfunction "1_2") (pintype "passive"))
      (node (ref "KEYBOARD_SHIFT_UPPER") (pin "14") (pinfunction "SER_14") (pintype "input"))
    )
    (net (code "129") (name "Net-(KEYBOARDC-1)") (class "Default")
      (node (ref "KEYBOARD") (pin "3") (pinfunction "1_3") (pintype "passive"))
      (node (ref "NOT_GATE3_") (pin "1") (pinfunction "I_1") (pintype "input"))
    )
    (net (code "130") (name "Net-(KEYBOARD_SHIFT_LOWERA-QA)") (class "Default")
      (node (ref "KEYBOARD_ASCII_TABLE") (pin "9") (pinfunction "9_9") (pintype "passive"))
      (node (ref "KEYBOARD_SHIFT_LOWER") (pin "15") (pinfunction "QA_15") (pintype "tri_state"))
    )
    (net (code "131") (name "Net-(KEYBOARD_SHIFT_LOWERA-QB)") (class "Default")
      (node (ref "KEYBOARD_ASCII_TABLE") (pin "10") (pinfunction "10_10") (pintype "passive"))
      (node (ref "KEYBOARD_SHIFT_LOWER") (pin "1") (pinfunction "QB_1") (pintype "tri_state"))
    )
    (net (code "132") (name "Net-(KEYBOARD_SHIFT_LOWERA-RCK)") (class "Default")
      (node (ref "KEYBOARD_SHIFT_LOWER") (pin "12") (pinfunction "RCK_12") (pintype "input"))
      (node (ref "KEYBOARD_SHIFT_UPPER") (pin "12") (pinfunction "RCK_12") (pintype "input"))
      (node (ref "NOT_GATE3_") (pin "6") (pinfunction "O_6") (pintype "output"))
    )
    (net (code "133") (name "Net-(KEYBOARD_SHIFT_LOWERA-SCK)") (class "Default")
      (node (ref "D1") (pin "A") (pinfunction "A_A") (pintype "passive"))
      (node (ref "KEYBOARD_SHIFT_LOWER") (pin "11") (pinfunction "SCK_11") (pintype "input"))
      (node (ref "KEYBOARD_SHIFT_UPPER") (pin "11") (pinfunction "SCK_11") (pintype "input"))
      (node (ref "NOT_GATE3_") (pin "2") (pinfunction "O_2") (pintype "output"))
      (node (ref "NOT_GATE3_") (pin "5") (pinfunction "I_5") (pintype "input"))
      (node (ref "R6") (pin "1") (pinfunction "1_1") (pintype "passive"))
    )
    (net (code "134") (name "Net-(KEYBOARD_SHIFT_LOWERA-SER)") (class "Default")
      (node (ref "KEYBOARD_SHIFT_LOWER") (pin "14") (pinfunction "SER_14") (pintype "input"))
      (node (ref "KEYBOARD_SHIFT_UPPER") (pin "9") (pinfunction "QH*_9") (pintype "tri_state"))
    )
    (net (code "135") (name "Net-(KEYBOARD_SHIFT_UPPERA-QC)") (class "Default")
      (node (ref "KEYBOARD_ASCII_TABLE") (pin "3") (pinfunction "3_3") (pintype "passive"))
      (node (ref "KEYBOARD_SHIFT_UPPER") (pin "2") (pinfunction "QC_2") (pintype "tri_state"))
    )
    (net (code "136") (name "Net-(KEYBOARD_SHIFT_UPPERA-QD)") (class "Default")
      (node (ref "KEYBOARD_ASCII_TABLE") (pin "4") (pinfunction "4_4") (pintype "passive"))
      (node (ref "KEYBOARD_SHIFT_UPPER") (pin "3") (pinfunction "QD_3") (pintype "tri_state"))
    )
    (net (code "137") (name "Net-(KEYBOARD_SHIFT_UPPERA-QE)") (class "Default")
      (node (ref "KEYBOARD_ASCII_TABLE") (pin "5") (pinfunction "5_5") (pintype "passive"))
      (node (ref "KEYBOARD_SHIFT_UPPER") (pin "4") (pinfunction "QE_4") (pintype "tri_state"))
    )
    (net (code "138") (name "Net-(KEYBOARD_SHIFT_UPPERA-QF)") (class "Default")
      (node (ref "KEYBOARD_ASCII_TABLE") (pin "6") (pinfunction "6_6") (pintype "passive"))
      (node (ref "KEYBOARD_SHIFT_UPPER") (pin "5") (pinfunction "QF_5") (pintype "tri_state"))
    )
    (net (code "139") (name "Net-(KEYBOARD_SHIFT_UPPERA-QG)") (class "Default")
      (node (ref "KEYBOARD_ASCII_TABLE") (pin "7") (pinfunction "7_7") (pintype "passive"))
      (node (ref "KEYBOARD_SHIFT_UPPER") (pin "6") (pinfunction "QG_6") (pintype "tri_state"))
    )
    (net (code "140") (name "Net-(KEYBOARD_SHIFT_UPPERA-QH)") (class "Default")
      (node (ref "KEYBOARD_ASCII_TABLE") (pin "8") (pinfunction "8_8") (pintype "passive"))
      (node (ref "KEYBOARD_SHIFT_UPPER") (pin "7") (pinfunction "QH_7") (pintype "tri_state"))
    )
    (net (code "141") (name "Net-(LED_A_REG_1-C)") (class "Default")
      (node (ref "LED_A_REG_1") (pin "K") (pinfunction "C_K") (pintype "passive"))
      (node (ref "R53") (pin "1") (pinfunction "1_1") (pintype "passive"))
    )
    (net (code "142") (name "Net-(LED_A_REG_2-C)") (class "Default")
      (node (ref "LED_A_REG_2") (pin "K") (pinfunction "C_K") (pintype "passive"))
      (node (ref "R54") (pin "1") (pinfunction "1_1") (pintype "passive"))
    )
    (net (code "143") (name "Net-(LED_A_REG_3-C)") (class "Default")
      (node (ref "LED_A_REG_3") (pin "K") (pinfunction "C_K") (pintype "passive"))
      (node (ref "R55") (pin "1") (pinfunction "1_1") (pintype "passive"))
    )
    (net (code "144") (name "Net-(LED_A_REG_4-C)") (class "Default")
      (node (ref "LED_A_REG_4") (pin "K") (pinfunction "C_K") (pintype "passive"))
      (node (ref "R56") (pin "1") (pinfunction "1_1") (pintype "passive"))
    )
    (net (code "145") (name "Net-(LED_A_REG_5-C)") (class "Default")
      (node (ref "LED_A_REG_5") (pin "K") (pinfunction "C_K") (pintype "passive"))
      (node (ref "R57") (pin "1") (pinfunction "1_1") (pintype "passive"))
    )
    (net (code "146") (name "Net-(LED_A_REG_6-C)") (class "Default")
      (node (ref "LED_A_REG_6") (pin "K") (pinfunction "C_K") (pintype "passive"))
      (node (ref "R58") (pin "1") (pinfunction "1_1") (pintype "passive"))
    )
    (net (code "147") (name "Net-(LED_A_REG_7-C)") (class "Default")
      (node (ref "LED_A_REG_7") (pin "K") (pinfunction "C_K") (pintype "passive"))
      (node (ref "R59") (pin "1") (pinfunction "1_1") (pintype "passive"))
    )
    (net (code "148") (name "Net-(LED_A_REG_8-C)") (class "Default")
      (node (ref "LED_A_REG_8") (pin "K") (pinfunction "C_K") (pintype "passive"))
      (node (ref "R60") (pin "1") (pinfunction "1_1") (pintype "passive"))
    )
    (net (code "149") (name "Net-(LED_B_REG_1-C)") (class "Default")
      (node (ref "LED_B_REG_1") (pin "K") (pinfunction "C_K") (pintype "passive"))
      (node (ref "R61") (pin "1") (pinfunction "1_1") (pintype "passive"))
    )
    (net (code "150") (name "Net-(LED_B_REG_2-C)") (class "Default")
      (node (ref "LED_B_REG_2") (pin "K") (pinfunction "C_K") (pintype "passive"))
      (node (ref "R62") (pin "1") (pinfunction "1_1") (pintype "passive"))
    )
    (net (code "151") (name "Net-(LED_B_REG_3-C)") (class "Default")
      (node (ref "LED_B_REG_3") (pin "K") (pinfunction "C_K") (pintype "passive"))
      (node (ref "R63") (pin "1") (pinfunction "1_1") (pintype "passive"))
    )
    (net (code "152") (name "Net-(LED_B_REG_4-C)") (class "Default")
      (node (ref "LED_B_REG_4") (pin "K") (pinfunction "C_K") (pintype "passive"))
      (node (ref "R64") (pin "1") (pinfunction "1_1") (pintype "passive"))
    )
    (net (code "153") (name "Net-(LED_B_REG_5-C)") (class "Default")
      (node (ref "LED_B_REG_5") (pin "K") (pinfunction "C_K") (pintype "passive"))
      (node (ref "R65") (pin "1") (pinfunction "1_1") (pintype "passive"))
    )
    (net (code "154") (name "Net-(LED_B_REG_6-C)") (class "Default")
      (node (ref "LED_B_REG_6") (pin "K") (pinfunction "C_K") (pintype "passive"))
      (node (ref "R66") (pin "1") (pinfunction "1_1") (pintype "passive"))
    )
    (net (code "155") (name "Net-(LED_B_REG_7-C)") (class "Default")
      (node (ref "LED_B_REG_7") (pin "K") (pinfunction "C_K") (pintype "passive"))
      (node (ref "R67") (pin "1") (pinfunction "1_1") (pintype "passive"))
    )
    (net (code "156") (name "Net-(LED_B_REG_8-C)") (class "Default")
      (node (ref "LED_B_REG_8") (pin "K") (pinfunction "C_K") (pintype "passive"))
      (node (ref "R68") (pin "1") (pinfunction "1_1") (pintype "passive"))
    )
    (net (code "157") (name "Net-(MICRO_COUNTER_LOWER-Pad15)") (class "Default")
      (node (ref "MICRO_COUNTER_LOWER") (pin "15") (pinfunction "15_15") (pintype "passive"))
      (node (ref "MICRO_COUNTER_UPPER") (pin "10") (pinfunction "10_10") (pintype "passive"))
    )
    (net (code "158") (name "Net-(NOR_GATE_A-I0)") (class "Default")
      (node (ref "NOR_GATE_") (pin "2") (pinfunction "I0_2") (pintype "input"))
      (node (ref "NOT_GATE_") (pin "6") (pinfunction "O_6") (pintype "output"))
    )
    (net (code "159") (name "Net-(NOR_GATE_A-I1)") (class "Default")
      (node (ref "C4") (pin "+") (pinfunction "+_+") (pintype "passive"))
      (node (ref "D1") (pin "C") (pinfunction "C_C") (pintype "passive"))
      (node (ref "NOR_GATE_") (pin "3") (pinfunction "I1_3") (pintype "input"))
      (node (ref "NOT_GATE_") (pin "3") (pinfunction "I_3") (pintype "input"))
      (node (ref "R6") (pin "2") (pinfunction "2_2") (pintype "passive"))
    )
    (net (code "160") (name "Net-(NOR_GATE_B-I0)") (class "Default")
      (node (ref "NOR_GATE_") (pin "5") (pinfunction "I0_5") (pintype "input"))
      (node (ref "SELECTOR_LOGIC_") (pin "7") (pinfunction "Y3_7") (pintype "output"))
    )
    (net (code "161") (name "Net-(NOR_GATE_B-I1)") (class "Default")
      (node (ref "NOR_GATE_") (pin "6") (pinfunction "I1_6") (pintype "input"))
      (node (ref "XOR_GATE_2") (pin "11") (pinfunction "O_11") (pintype "output"))
    )
    (net (code "162") (name "Net-(NOT_GATE1_A-I)") (class "Default")
      (node (ref "NOT_GATE1_") (pin "1") (pinfunction "I_1") (pintype "input"))
      (node (ref "SELECTOR_BRANCH_") (pin "7") (pinfunction "Y3_7") (pintype "output"))
    )
    (net (code "163") (name "Net-(NOT_GATE1_C-I)") (class "Default")
      (node (ref "NOT_GATE1_") (pin "5") (pinfunction "I_5") (pintype "input"))
      (node (ref "SELECTOR_PARAM_") (pin "10") (pinfunction "Y2_10") (pintype "output"))
    )
    (net (code "164") (name "Net-(NOT_GATE1_D-I)") (class "Default")
      (node (ref "NOT_GATE1_") (pin "9") (pinfunction "I_9") (pintype "input"))
      (node (ref "SELECTOR_PARAM_") (pin "11") (pinfunction "Y1_11") (pintype "output"))
    )
    (net (code "165") (name "Net-(NOT_GATE1_D-O)") (class "Default")
      (node (ref "NOT_GATE1_") (pin "8") (pinfunction "O_8") (pintype "output"))
      (node (ref "OUTPUT_BUFFER_MEMORY") (pin "19") (pinfunction "G_19") (pintype "input"))
    )
    (net (code "166") (name "Net-(NOT_GATE1_E-O)") (class "Default")
      (node (ref "INVERTED_CLK_LED") (pin "A") (pinfunction "A_A") (pintype "passive"))
      (node (ref "MICRO_COUNTER_LOWER") (pin "2") (pinfunction "2_2") (pintype "passive"))
      (node (ref "MICRO_COUNTER_UPPER") (pin "2") (pinfunction "2_2") (pintype "passive"))
      (node (ref "NOT_GATE1_") (pin "10") (pinfunction "O_10") (pintype "output"))
    )
    (net (code "167") (name "Net-(NOT_GATE1_F-I)") (class "Default")
      (node (ref "INSTRUCTION_MEMORY_1") (pin "16") (pinfunction "16_16") (pintype "passive"))
      (node (ref "NOT_GATE1_") (pin "13") (pinfunction "I_13") (pintype "input"))
    )
    (net (code "168") (name "Net-(NOT_GATE2_A-I)") (class "Default")
      (node (ref "NOT_GATE2_") (pin "1") (pinfunction "I_1") (pintype "input"))
      (node (ref "SELECTOR_PARAM_") (pin "5") (pinfunction "Y1_5") (pintype "output"))
    )
    (net (code "169") (name "Net-(NOT_GATE2_A-O)") (class "Default")
      (node (ref "NOT_GATE2_") (pin "2") (pinfunction "O_2") (pintype "output"))
      (node (ref "OUTPUT_BUFFER_PARAM_REG") (pin "19") (pinfunction "G_19") (pintype "input"))
    )
    (net (code "170") (name "Net-(NOT_GATE2_B-I)") (class "Default")
      (node (ref "NOT_GATE2_") (pin "3") (pinfunction "I_3") (pintype "input"))
      (node (ref "SELECTOR_PARAM_") (pin "6") (pinfunction "Y2_6") (pintype "output"))
    )
    (net (code "171") (name "Net-(NOT_GATE2_B-O)") (class "Default")
      (node (ref "NOT_GATE2_") (pin "4") (pinfunction "O_4") (pintype "output"))
      (node (ref "REG_PARAM_LOWER") (pin "10") (pinfunction "G2_10") (pintype "input"))
      (node (ref "REG_PARAM_LOWER") (pin "9") (pinfunction "G1_9") (pintype "input"))
      (node (ref "REG_PARAM_UPPER") (pin "10") (pinfunction "G2_10") (pintype "input"))
      (node (ref "REG_PARAM_UPPER") (pin "9") (pinfunction "G1_9") (pintype "input"))
    )
    (net (code "172") (name "Net-(NOT_GATE2_C-I)") (class "Default")
      (node (ref "NOT_GATE2_") (pin "5") (pinfunction "I_5") (pintype "input"))
      (node (ref "SELECTOR_BRANCH_") (pin "6") (pinfunction "Y2_6") (pintype "output"))
    )
    (net (code "173") (name "Net-(NOT_GATE2_D-I)") (class "Default")
      (node (ref "NOT_GATE2_") (pin "9") (pinfunction "I_9") (pintype "input"))
      (node (ref "SELECTOR_BRANCH_") (pin "5") (pinfunction "Y1_5") (pintype "output"))
    )
    (net (code "174") (name "Net-(NOT_GATE2_E-I)") (class "Default")
      (node (ref "NOT_GATE2_") (pin "11") (pinfunction "I_11") (pintype "input"))
      (node (ref "SELECTOR_STACK_") (pin "7") (pinfunction "Y3_7") (pintype "output"))
    )
    (net (code "175") (name "Net-(NOT_GATE2_E-O)") (class "Default")
      (node (ref "NOT_GATE2_") (pin "10") (pinfunction "O_10") (pintype "output"))
      (node (ref "PROGRAM_COUNTER_LOWER") (pin "10") (pinfunction "10_10") (pintype "passive"))
    )
    (net (code "176") (name "Net-(NOT_GATE2_F-I)") (class "Default")
      (node (ref "NOT_GATE2_") (pin "13") (pinfunction "I_13") (pintype "input"))
      (node (ref "RAM") (pin "22") (pinfunction "22_22") (pintype "passive"))
      (node (ref "SELECTOR_INSRUCTION_UPPER") (pin "7") (pinfunction "2Y_7") (pintype "output"))
    )
    (net (code "177") (name "Net-(NOT_GATE2_F-O)") (class "Default")
      (node (ref "NOT_GATE2_") (pin "12") (pinfunction "O_12") (pintype "output"))
      (node (ref "RAM") (pin "27") (pinfunction "27_27") (pintype "passive"))
    )
    (net (code "178") (name "Net-(NOT_GATE3_B-I)") (class "Default")
      (node (ref "INSTRUCTION_MEMORY_1") (pin "13") (pinfunction "13_13") (pintype "passive"))
      (node (ref "NOT_GATE3_") (pin "3") (pinfunction "I_3") (pintype "input"))
    )
    (net (code "179") (name "Net-(NOT_GATE3_B-O)") (class "Default")
      (node (ref "NOT_GATE3_") (pin "4") (pinfunction "O_4") (pintype "output"))
      (node (ref "OUTPUT_BUFFER_ALU") (pin "19") (pinfunction "G_19") (pintype "input"))
    )
    (net (code "180") (name "Net-(NOT_GATE3_D-I)") (class "Default")
      (node (ref "NOT_GATE3_") (pin "9") (pinfunction "I_9") (pintype "input"))
      (node (ref "NOT_GATE_") (pin "4") (pinfunction "O_4") (pintype "output"))
    )
    (net (code "181") (name "Net-(NOT_GATE3_D-O)") (class "Default")
      (node (ref "NOT_GATE3_") (pin "11") (pinfunction "I_11") (pintype "input"))
      (node (ref "NOT_GATE3_") (pin "8") (pinfunction "O_8") (pintype "output"))
    )
    (net (code "182") (name "Net-(NOT_GATE3_E-O)") (class "Default")
      (node (ref "NOT_GATE3_") (pin "10") (pinfunction "O_10") (pintype "output"))
      (node (ref "NOT_GATE3_") (pin "13") (pinfunction "I_13") (pintype "input"))
    )
    (net (code "183") (name "Net-(NOT_GATE3_F-O)") (class "Default")
      (node (ref "NOT_GATE3_") (pin "12") (pinfunction "O_12") (pintype "output"))
      (node (ref "NOT_GATE_") (pin "5") (pinfunction "I_5") (pintype "input"))
    )
    (net (code "184") (name "Net-(NOT_GATE4_A-I)") (class "Default")
      (node (ref "NOT_GATE4_") (pin "1") (pinfunction "I_1") (pintype "input"))
      (node (ref "SELECTOR_BRANCH_") (pin "4") (pinfunction "Y0_4") (pintype "output"))
    )
    (net (code "185") (name "Net-(NOT_GATE4_B-I)") (class "Default")
      (node (ref "NOT_GATE4_") (pin "3") (pinfunction "I_3") (pintype "input"))
      (node (ref "SELECTOR_INSRUCTION_UPPER") (pin "4") (pinfunction "1Y_4") (pintype "output"))
    )
    (net (code "186") (name "Net-(NOT_GATE4_B-O)") (class "Default")
      (node (ref "NOT_GATE4_") (pin "4") (pinfunction "O_4") (pintype "output"))
      (node (ref "RAM_ADDR_LOWER") (pin "10") (pinfunction "G2_10") (pintype "input"))
      (node (ref "RAM_ADDR_LOWER") (pin "9") (pinfunction "G1_9") (pintype "input"))
      (node (ref "RAM_ADDR_UPPER") (pin "10") (pinfunction "G2_10") (pintype "input"))
      (node (ref "RAM_ADDR_UPPER") (pin "9") (pinfunction "G1_9") (pintype "input"))
    )
    (net (code "187") (name "Net-(NOT_GATE4_C-O)") (class "Default")
      (node (ref "NOT_GATE4_") (pin "6") (pinfunction "O_6") (pintype "output"))
      (node (ref "PROGRAM_COUNTER_LOWER") (pin "9") (pinfunction "9_9") (pintype "passive"))
      (node (ref "PROGRAM_COUNTER_UPPER") (pin "9") (pinfunction "9_9") (pintype "passive"))
    )
    (net (code "188") (name "Net-(NOT_GATE4_D-O)") (class "Default")
      (node (ref "MICRO_COUNTER_LOWER") (pin "9") (pinfunction "9_9") (pintype "passive"))
      (node (ref "MICRO_COUNTER_UPPER") (pin "9") (pinfunction "9_9") (pintype "passive"))
      (node (ref "NOT_GATE4_") (pin "8") (pinfunction "O_8") (pintype "output"))
    )
    (net (code "189") (name "Net-(NOT_GATE4_E-I)") (class "Default")
      (node (ref "INSTRUCTION_MEMORY_1") (pin "17") (pinfunction "17_17") (pintype "passive"))
      (node (ref "NOT_GATE4_") (pin "11") (pinfunction "I_11") (pintype "input"))
    )
    (net (code "190") (name "Net-(NOT_GATE4_E-O)") (class "Default")
      (node (ref "NOT_GATE4_") (pin "10") (pinfunction "O_10") (pintype "output"))
      (node (ref "OUTPUT_BUFFER_RAM") (pin "19") (pinfunction "G_19") (pintype "input"))
    )
    (net (code "191") (name "Net-(NOT_GATE4_F-I)") (class "Default")
      (node (ref "NOT_GATE4_") (pin "13") (pinfunction "I_13") (pintype "input"))
      (node (ref "SELECTOR_BRANCH_") (pin "9") (pinfunction "Y3_9") (pintype "output"))
    )
    (net (code "192") (name "Net-(NOT_GATE_A-I)") (class "Default")
      (node (ref "INSTRUCTION_MEMORY_2") (pin "11") (pinfunction "11_11") (pintype "passive"))
      (node (ref "NOT_GATE_") (pin "1") (pinfunction "I_1") (pintype "input"))
    )
    (net (code "193") (name "Net-(NOT_GATE_A-O)") (class "Default")
      (node (ref "NOT_GATE_") (pin "2") (pinfunction "O_2") (pintype "output"))
      (node (ref "OUTPUT_BUFFER_FLAGS") (pin "19") (pinfunction "G_19") (pintype "input"))
    )
    (net (code "194") (name "Net-(NOT_GATE_D-I)") (class "Default")
      (node (ref "NOT_GATE_") (pin "9") (pinfunction "I_9") (pintype "input"))
      (node (ref "SELECTOR_STACK_") (pin "5") (pinfunction "Y1_5") (pintype "output"))
    )
    (net (code "195") (name "Net-(OUTPUT_BUFFER_CALC_REGA-A1)") (class "Default")
      (node (ref "LED_B_REG_8") (pin "A") (pinfunction "A_A") (pintype "passive"))
      (node (ref "OUTPUT_BUFFER_CALC_REG") (pin "2") (pinfunction "A1_2") (pintype "bidirectional"))
      (node (ref "REG_CALC_UPPER") (pin "3") (pinfunction "Q1_3") (pintype "tri_state"))
      (node (ref "SUBTRACT_INVRTR_UPPER_") (pin "2") (pinfunction "I1_2") (pintype "input"))
    )
    (net (code "196") (name "Net-(OUTPUT_BUFFER_CALC_REGA-A2)") (class "Default")
      (node (ref "LED_B_REG_7") (pin "A") (pinfunction "A_A") (pintype "passive"))
      (node (ref "OUTPUT_BUFFER_CALC_REG") (pin "3") (pinfunction "A2_3") (pintype "bidirectional"))
      (node (ref "REG_CALC_UPPER") (pin "4") (pinfunction "Q2_4") (pintype "tri_state"))
      (node (ref "SUBTRACT_INVRTR_UPPER_") (pin "5") (pinfunction "I1_5") (pintype "input"))
    )
    (net (code "197") (name "Net-(OUTPUT_BUFFER_CALC_REGA-A3)") (class "Default")
      (node (ref "LED_B_REG_6") (pin "A") (pinfunction "A_A") (pintype "passive"))
      (node (ref "OUTPUT_BUFFER_CALC_REG") (pin "4") (pinfunction "A3_4") (pintype "bidirectional"))
      (node (ref "REG_CALC_UPPER") (pin "5") (pinfunction "Q3_5") (pintype "tri_state"))
      (node (ref "SUBTRACT_INVRTR_UPPER_") (pin "10") (pinfunction "I1_10") (pintype "input"))
    )
    (net (code "198") (name "Net-(OUTPUT_BUFFER_CALC_REGA-A4)") (class "Default")
      (node (ref "LED_B_REG_5") (pin "A") (pinfunction "A_A") (pintype "passive"))
      (node (ref "OUTPUT_BUFFER_CALC_REG") (pin "5") (pinfunction "A4_5") (pintype "bidirectional"))
      (node (ref "REG_CALC_UPPER") (pin "6") (pinfunction "Q4_6") (pintype "tri_state"))
      (node (ref "SUBTRACT_INVRTR_UPPER_") (pin "13") (pinfunction "I1_13") (pintype "input"))
    )
    (net (code "199") (name "Net-(OUTPUT_BUFFER_CALC_REGA-A5)") (class "Default")
      (node (ref "LED_B_REG_4") (pin "A") (pinfunction "A_A") (pintype "passive"))
      (node (ref "OUTPUT_BUFFER_CALC_REG") (pin "6") (pinfunction "A5_6") (pintype "bidirectional"))
      (node (ref "REG_CALC_LOWER") (pin "3") (pinfunction "Q1_3") (pintype "tri_state"))
      (node (ref "SUBTRACT_INVRTR_LOWER_") (pin "2") (pinfunction "I1_2") (pintype "input"))
    )
    (net (code "200") (name "Net-(OUTPUT_BUFFER_CALC_REGA-A6)") (class "Default")
      (node (ref "LED_B_REG_3") (pin "A") (pinfunction "A_A") (pintype "passive"))
      (node (ref "OUTPUT_BUFFER_CALC_REG") (pin "7") (pinfunction "A6_7") (pintype "bidirectional"))
      (node (ref "REG_CALC_LOWER") (pin "4") (pinfunction "Q2_4") (pintype "tri_state"))
      (node (ref "SUBTRACT_INVRTR_LOWER_") (pin "5") (pinfunction "I1_5") (pintype "input"))
    )
    (net (code "201") (name "Net-(OUTPUT_BUFFER_CALC_REGA-A7)") (class "Default")
      (node (ref "LED_B_REG_2") (pin "A") (pinfunction "A_A") (pintype "passive"))
      (node (ref "OUTPUT_BUFFER_CALC_REG") (pin "8") (pinfunction "A7_8") (pintype "bidirectional"))
      (node (ref "REG_CALC_LOWER") (pin "5") (pinfunction "Q3_5") (pintype "tri_state"))
      (node (ref "SUBTRACT_INVRTR_LOWER_") (pin "10") (pinfunction "I1_10") (pintype "input"))
    )
    (net (code "202") (name "Net-(OUTPUT_BUFFER_CALC_REGA-A8)") (class "Default")
      (node (ref "LED_B_REG_1") (pin "A") (pinfunction "A_A") (pintype "passive"))
      (node (ref "OUTPUT_BUFFER_CALC_REG") (pin "9") (pinfunction "A8_9") (pintype "bidirectional"))
      (node (ref "REG_CALC_LOWER") (pin "6") (pinfunction "Q4_6") (pintype "tri_state"))
      (node (ref "SUBTRACT_INVRTR_LOWER_") (pin "13") (pinfunction "I1_13") (pintype "input"))
    )
    (net (code "203") (name "Net-(OUTPUT_BUFFER_CALC_REGA-G)") (class "Default")
      (node (ref "OUTPUT_BUFFER_CALC_REG") (pin "19") (pinfunction "G_19") (pintype "input"))
      (node (ref "SELECTOR_LOGIC_") (pin "11") (pinfunction "Y1_11") (pintype "output"))
    )
    (net (code "204") (name "Net-(OUTPUT_BUFFER_INSTRUCTIONA-A1)") (class "Default")
      (node (ref "INSTRUCTION_MEMORY_0") (pin "11") (pinfunction "11_11") (pintype "passive"))
      (node (ref "OUTPUT_BUFFER_INSTRUCTION") (pin "2") (pinfunction "A1_2") (pintype "bidirectional"))
      (node (ref "SELECTOR_INSRUCTION_LOWER") (pin "13") (pinfunction "4B_13") (pintype "input"))
    )
    (net (code "205") (name "Net-(OUTPUT_BUFFER_INSTRUCTIONA-A2)") (class "Default")
      (node (ref "INSTRUCTION_MEMORY_0") (pin "12") (pinfunction "12_12") (pintype "passive"))
      (node (ref "OUTPUT_BUFFER_INSTRUCTION") (pin "3") (pinfunction "A2_3") (pintype "bidirectional"))
      (node (ref "SELECTOR_INSRUCTION_LOWER") (pin "10") (pinfunction "3B_10") (pintype "input"))
    )
    (net (code "206") (name "Net-(OUTPUT_BUFFER_INSTRUCTIONA-A3)") (class "Default")
      (node (ref "INSTRUCTION_MEMORY_0") (pin "13") (pinfunction "13_13") (pintype "passive"))
      (node (ref "OUTPUT_BUFFER_INSTRUCTION") (pin "4") (pinfunction "A3_4") (pintype "bidirectional"))
      (node (ref "SELECTOR_INSRUCTION_LOWER") (pin "6") (pinfunction "2B_6") (pintype "input"))
    )
    (net (code "207") (name "Net-(OUTPUT_BUFFER_INSTRUCTIONA-A4)") (class "Default")
      (node (ref "INSTRUCTION_MEMORY_0") (pin "15") (pinfunction "15_15") (pintype "passive"))
      (node (ref "OUTPUT_BUFFER_INSTRUCTION") (pin "5") (pinfunction "A4_5") (pintype "bidirectional"))
      (node (ref "SELECTOR_INSRUCTION_LOWER") (pin "3") (pinfunction "1B_3") (pintype "input"))
    )
    (net (code "208") (name "Net-(OUTPUT_BUFFER_INSTRUCTIONA-A5)") (class "Default")
      (node (ref "INSTRUCTION_MEMORY_0") (pin "16") (pinfunction "16_16") (pintype "passive"))
      (node (ref "OUTPUT_BUFFER_INSTRUCTION") (pin "6") (pinfunction "A5_6") (pintype "bidirectional"))
      (node (ref "SELECTOR_INSRUCTION_UPPER") (pin "13") (pinfunction "4B_13") (pintype "input"))
    )
    (net (code "209") (name "Net-(OUTPUT_BUFFER_INSTRUCTIONA-A6)") (class "Default")
      (node (ref "INSTRUCTION_MEMORY_0") (pin "17") (pinfunction "17_17") (pintype "passive"))
      (node (ref "OUTPUT_BUFFER_INSTRUCTION") (pin "7") (pinfunction "A6_7") (pintype "bidirectional"))
      (node (ref "SELECTOR_INSRUCTION_UPPER") (pin "10") (pinfunction "3B_10") (pintype "input"))
    )
    (net (code "210") (name "Net-(OUTPUT_BUFFER_INSTRUCTIONA-A7)") (class "Default")
      (node (ref "INSTRUCTION_MEMORY_0") (pin "18") (pinfunction "18_18") (pintype "passive"))
      (node (ref "OUTPUT_BUFFER_INSTRUCTION") (pin "8") (pinfunction "A7_8") (pintype "bidirectional"))
      (node (ref "SELECTOR_INSRUCTION_UPPER") (pin "6") (pinfunction "2B_6") (pintype "input"))
    )
    (net (code "211") (name "Net-(OUTPUT_BUFFER_INSTRUCTIONA-A8)") (class "Default")
      (node (ref "INSTRUCTION_MEMORY_0") (pin "19") (pinfunction "19_19") (pintype "passive"))
      (node (ref "OUTPUT_BUFFER_INSTRUCTION") (pin "9") (pinfunction "A8_9") (pintype "bidirectional"))
      (node (ref "SELECTOR_INSRUCTION_UPPER") (pin "3") (pinfunction "1B_3") (pintype "input"))
    )
    (net (code "212") (name "Net-(OUTPUT_BUFFER_INSTRUCTIONA-G)") (class "Default")
      (node (ref "OUTPUT_BUFFER_INSTRUCTION") (pin "19") (pinfunction "G_19") (pintype "input"))
      (node (ref "SELECTOR_INSRUCTION_LOWER") (pin "1") (pinfunction "~{A}/B_1") (pintype "input"))
      (node (ref "SELECTOR_INSRUCTION_UPPER") (pin "1") (pinfunction "~{A}/B_1") (pintype "input"))
      (node (ref "SELECTOR_LOGIC_") (pin "6") (pinfunction "Y2_6") (pintype "output"))
    )
    (net (code "213") (name "Net-(OUTPUT_BUFFER_KEYBOARDA-B1)") (class "Default")
      (node (ref "KEYBOARD_ASCII_TABLE") (pin "11") (pinfunction "11_11") (pintype "passive"))
      (node (ref "OUTPUT_BUFFER_KEYBOARD") (pin "18") (pinfunction "B1_18") (pintype "bidirectional"))
    )
    (net (code "214") (name "Net-(OUTPUT_BUFFER_KEYBOARDA-B2)") (class "Default")
      (node (ref "KEYBOARD_ASCII_TABLE") (pin "12") (pinfunction "12_12") (pintype "passive"))
      (node (ref "OUTPUT_BUFFER_KEYBOARD") (pin "17") (pinfunction "B2_17") (pintype "bidirectional"))
    )
    (net (code "215") (name "Net-(OUTPUT_BUFFER_KEYBOARDA-B3)") (class "Default")
      (node (ref "KEYBOARD_ASCII_TABLE") (pin "13") (pinfunction "13_13") (pintype "passive"))
      (node (ref "OUTPUT_BUFFER_KEYBOARD") (pin "16") (pinfunction "B3_16") (pintype "bidirectional"))
    )
    (net (code "216") (name "Net-(OUTPUT_BUFFER_KEYBOARDA-B4)") (class "Default")
      (node (ref "KEYBOARD_ASCII_TABLE") (pin "15") (pinfunction "15_15") (pintype "passive"))
      (node (ref "OUTPUT_BUFFER_KEYBOARD") (pin "15") (pinfunction "B4_15") (pintype "bidirectional"))
    )
    (net (code "217") (name "Net-(OUTPUT_BUFFER_KEYBOARDA-B5)") (class "Default")
      (node (ref "KEYBOARD_ASCII_TABLE") (pin "16") (pinfunction "16_16") (pintype "passive"))
      (node (ref "OUTPUT_BUFFER_KEYBOARD") (pin "14") (pinfunction "B5_14") (pintype "bidirectional"))
    )
    (net (code "218") (name "Net-(OUTPUT_BUFFER_KEYBOARDA-B6)") (class "Default")
      (node (ref "KEYBOARD_ASCII_TABLE") (pin "17") (pinfunction "17_17") (pintype "passive"))
      (node (ref "OUTPUT_BUFFER_KEYBOARD") (pin "13") (pinfunction "B6_13") (pintype "bidirectional"))
    )
    (net (code "219") (name "Net-(OUTPUT_BUFFER_KEYBOARDA-B7)") (class "Default")
      (node (ref "KEYBOARD_ASCII_TABLE") (pin "18") (pinfunction "18_18") (pintype "passive"))
      (node (ref "OUTPUT_BUFFER_KEYBOARD") (pin "12") (pinfunction "B7_12") (pintype "bidirectional"))
    )
    (net (code "220") (name "Net-(OUTPUT_BUFFER_KEYBOARDA-B8)") (class "Default")
      (node (ref "KEYBOARD_ASCII_TABLE") (pin "19") (pinfunction "19_19") (pintype "passive"))
      (node (ref "OUTPUT_BUFFER_KEYBOARD") (pin "11") (pinfunction "B8_11") (pintype "bidirectional"))
    )
    (net (code "221") (name "Net-(OUTPUT_BUFFER_KEYBOARDA-G)") (class "Default")
      (node (ref "OUTPUT_BUFFER_KEYBOARD") (pin "19") (pinfunction "G_19") (pintype "input"))
      (node (ref "SELECTOR_PARAM_") (pin "9") (pinfunction "Y3_9") (pintype "output"))
    )
    (net (code "222") (name "Net-(OUTPUT_BUFFER_MEMORYA-A1)") (class "Default")
      (node (ref "MEMORY") (pin "19") (pinfunction "19_19") (pintype "passive"))
      (node (ref "OUTPUT_BUFFER_MEMORY") (pin "2") (pinfunction "A1_2") (pintype "bidirectional"))
    )
    (net (code "223") (name "Net-(OUTPUT_BUFFER_MEMORYA-A2)") (class "Default")
      (node (ref "MEMORY") (pin "18") (pinfunction "18_18") (pintype "passive"))
      (node (ref "OUTPUT_BUFFER_MEMORY") (pin "3") (pinfunction "A2_3") (pintype "bidirectional"))
    )
    (net (code "224") (name "Net-(OUTPUT_BUFFER_MEMORYA-A3)") (class "Default")
      (node (ref "MEMORY") (pin "17") (pinfunction "17_17") (pintype "passive"))
      (node (ref "OUTPUT_BUFFER_MEMORY") (pin "4") (pinfunction "A3_4") (pintype "bidirectional"))
    )
    (net (code "225") (name "Net-(OUTPUT_BUFFER_MEMORYA-A4)") (class "Default")
      (node (ref "MEMORY") (pin "16") (pinfunction "16_16") (pintype "passive"))
      (node (ref "OUTPUT_BUFFER_MEMORY") (pin "5") (pinfunction "A4_5") (pintype "bidirectional"))
    )
    (net (code "226") (name "Net-(OUTPUT_BUFFER_MEMORYA-A5)") (class "Default")
      (node (ref "MEMORY") (pin "15") (pinfunction "15_15") (pintype "passive"))
      (node (ref "OUTPUT_BUFFER_MEMORY") (pin "6") (pinfunction "A5_6") (pintype "bidirectional"))
    )
    (net (code "227") (name "Net-(OUTPUT_BUFFER_MEMORYA-A6)") (class "Default")
      (node (ref "MEMORY") (pin "13") (pinfunction "13_13") (pintype "passive"))
      (node (ref "OUTPUT_BUFFER_MEMORY") (pin "7") (pinfunction "A6_7") (pintype "bidirectional"))
    )
    (net (code "228") (name "Net-(OUTPUT_BUFFER_MEMORYA-A7)") (class "Default")
      (node (ref "MEMORY") (pin "12") (pinfunction "12_12") (pintype "passive"))
      (node (ref "OUTPUT_BUFFER_MEMORY") (pin "8") (pinfunction "A7_8") (pintype "bidirectional"))
    )
    (net (code "229") (name "Net-(OUTPUT_BUFFER_MEMORYA-A8)") (class "Default")
      (node (ref "MEMORY") (pin "11") (pinfunction "11_11") (pintype "passive"))
      (node (ref "OUTPUT_BUFFER_MEMORY") (pin "9") (pinfunction "A8_9") (pintype "bidirectional"))
    )
    (net (code "230") (name "Net-(OUTPUT_BUFFER_PARAM_REGA-A1)") (class "Default")
      (node (ref "OUTPUT_BUFFER_PARAM_REG") (pin "2") (pinfunction "A1_2") (pintype "bidirectional"))
      (node (ref "PARAM_LED_8") (pin "A") (pinfunction "A_A") (pintype "passive"))
      (node (ref "REG_PARAM_UPPER") (pin "3") (pinfunction "Q1_3") (pintype "tri_state"))
    )
    (net (code "231") (name "Net-(OUTPUT_BUFFER_PARAM_REGA-A2)") (class "Default")
      (node (ref "OUTPUT_BUFFER_PARAM_REG") (pin "3") (pinfunction "A2_3") (pintype "bidirectional"))
      (node (ref "PARAM_LED_7") (pin "A") (pinfunction "A_A") (pintype "passive"))
      (node (ref "REG_PARAM_UPPER") (pin "4") (pinfunction "Q2_4") (pintype "tri_state"))
    )
    (net (code "232") (name "Net-(OUTPUT_BUFFER_PARAM_REGA-A3)") (class "Default")
      (node (ref "OUTPUT_BUFFER_PARAM_REG") (pin "4") (pinfunction "A3_4") (pintype "bidirectional"))
      (node (ref "PARAM_LED_6") (pin "A") (pinfunction "A_A") (pintype "passive"))
      (node (ref "REG_PARAM_UPPER") (pin "5") (pinfunction "Q3_5") (pintype "tri_state"))
    )
    (net (code "233") (name "Net-(OUTPUT_BUFFER_PARAM_REGA-A4)") (class "Default")
      (node (ref "OUTPUT_BUFFER_PARAM_REG") (pin "5") (pinfunction "A4_5") (pintype "bidirectional"))
      (node (ref "PARAM_LED_5") (pin "A") (pinfunction "A_A") (pintype "passive"))
      (node (ref "REG_PARAM_UPPER") (pin "6") (pinfunction "Q4_6") (pintype "tri_state"))
    )
    (net (code "234") (name "Net-(OUTPUT_BUFFER_PARAM_REGA-A5)") (class "Default")
      (node (ref "OUTPUT_BUFFER_PARAM_REG") (pin "6") (pinfunction "A5_6") (pintype "bidirectional"))
      (node (ref "PARAM_LED_4") (pin "A") (pinfunction "A_A") (pintype "passive"))
      (node (ref "REG_PARAM_LOWER") (pin "3") (pinfunction "Q1_3") (pintype "tri_state"))
    )
    (net (code "235") (name "Net-(OUTPUT_BUFFER_PARAM_REGA-A6)") (class "Default")
      (node (ref "OUTPUT_BUFFER_PARAM_REG") (pin "7") (pinfunction "A6_7") (pintype "bidirectional"))
      (node (ref "PARAM_LED_3") (pin "A") (pinfunction "A_A") (pintype "passive"))
      (node (ref "REG_PARAM_LOWER") (pin "4") (pinfunction "Q2_4") (pintype "tri_state"))
    )
    (net (code "236") (name "Net-(OUTPUT_BUFFER_PARAM_REGA-A7)") (class "Default")
      (node (ref "OUTPUT_BUFFER_PARAM_REG") (pin "8") (pinfunction "A7_8") (pintype "bidirectional"))
      (node (ref "PARAM_LED_2") (pin "A") (pinfunction "A_A") (pintype "passive"))
      (node (ref "REG_PARAM_LOWER") (pin "5") (pinfunction "Q3_5") (pintype "tri_state"))
    )
    (net (code "237") (name "Net-(OUTPUT_BUFFER_PARAM_REGA-A8)") (class "Default")
      (node (ref "OUTPUT_BUFFER_PARAM_REG") (pin "9") (pinfunction "A8_9") (pintype "bidirectional"))
      (node (ref "PARAM_LED_1") (pin "A") (pinfunction "A_A") (pintype "passive"))
      (node (ref "REG_PARAM_LOWER") (pin "6") (pinfunction "Q4_6") (pintype "tri_state"))
    )
    (net (code "238") (name "Net-(OUTPUT_BUFFER_PCA-A1)") (class "Default")
      (node (ref "OUTPUT_BUFFER_PC") (pin "2") (pinfunction "A1_2") (pintype "bidirectional"))
      (node (ref "PC_8") (pin "A") (pinfunction "A_A") (pintype "passive"))
      (node (ref "PROGRAM_COUNTER_UPPER") (pin "11") (pinfunction "11_11") (pintype "passive"))
    )
    (net (code "239") (name "Net-(OUTPUT_BUFFER_PCA-A2)") (class "Default")
      (node (ref "OUTPUT_BUFFER_PC") (pin "3") (pinfunction "A2_3") (pintype "bidirectional"))
      (node (ref "PC_7") (pin "A") (pinfunction "A_A") (pintype "passive"))
      (node (ref "PROGRAM_COUNTER_UPPER") (pin "12") (pinfunction "12_12") (pintype "passive"))
    )
    (net (code "240") (name "Net-(OUTPUT_BUFFER_PCA-A3)") (class "Default")
      (node (ref "OUTPUT_BUFFER_PC") (pin "4") (pinfunction "A3_4") (pintype "bidirectional"))
      (node (ref "PC_6") (pin "A") (pinfunction "A_A") (pintype "passive"))
      (node (ref "PROGRAM_COUNTER_UPPER") (pin "13") (pinfunction "13_13") (pintype "passive"))
    )
    (net (code "241") (name "Net-(OUTPUT_BUFFER_PCA-A4)") (class "Default")
      (node (ref "OUTPUT_BUFFER_PC") (pin "5") (pinfunction "A4_5") (pintype "bidirectional"))
      (node (ref "PC_5") (pin "A") (pinfunction "A_A") (pintype "passive"))
      (node (ref "PROGRAM_COUNTER_UPPER") (pin "14") (pinfunction "14_14") (pintype "passive"))
    )
    (net (code "242") (name "Net-(OUTPUT_BUFFER_PCA-A5)") (class "Default")
      (node (ref "OUTPUT_BUFFER_PC") (pin "6") (pinfunction "A5_6") (pintype "bidirectional"))
      (node (ref "PC_4") (pin "A") (pinfunction "A_A") (pintype "passive"))
      (node (ref "PROGRAM_COUNTER_LOWER") (pin "11") (pinfunction "11_11") (pintype "passive"))
    )
    (net (code "243") (name "Net-(OUTPUT_BUFFER_PCA-A6)") (class "Default")
      (node (ref "OUTPUT_BUFFER_PC") (pin "7") (pinfunction "A6_7") (pintype "bidirectional"))
      (node (ref "PC_3") (pin "A") (pinfunction "A_A") (pintype "passive"))
      (node (ref "PROGRAM_COUNTER_LOWER") (pin "12") (pinfunction "12_12") (pintype "passive"))
    )
    (net (code "244") (name "Net-(OUTPUT_BUFFER_PCA-A7)") (class "Default")
      (node (ref "OUTPUT_BUFFER_PC") (pin "8") (pinfunction "A7_8") (pintype "bidirectional"))
      (node (ref "PC_2") (pin "A") (pinfunction "A_A") (pintype "passive"))
      (node (ref "PROGRAM_COUNTER_LOWER") (pin "13") (pinfunction "13_13") (pintype "passive"))
    )
    (net (code "245") (name "Net-(OUTPUT_BUFFER_PCA-A8)") (class "Default")
      (node (ref "OUTPUT_BUFFER_PC") (pin "9") (pinfunction "A8_9") (pintype "bidirectional"))
      (node (ref "PC_1") (pin "A") (pinfunction "A_A") (pintype "passive"))
      (node (ref "PROGRAM_COUNTER_LOWER") (pin "14") (pinfunction "14_14") (pintype "passive"))
    )
    (net (code "246") (name "Net-(OUTPUT_BUFFER_PCA-G)") (class "Default")
      (node (ref "OUTPUT_BUFFER_PC") (pin "19") (pinfunction "G_19") (pintype "input"))
      (node (ref "SELECTOR_STACK_") (pin "6") (pinfunction "Y2_6") (pintype "output"))
    )
    (net (code "247") (name "Net-(OUTPUT_BUFFER_RAMA-A1)") (class "Default")
      (node (ref "OUTPUT_BUFFER_RAM") (pin "2") (pinfunction "A1_2") (pintype "bidirectional"))
      (node (ref "RAM") (pin "11") (pinfunction "11_11") (pintype "passive"))
      (node (ref "RAM_LED_1") (pin "A") (pinfunction "A_A") (pintype "passive"))
    )
    (net (code "248") (name "Net-(OUTPUT_BUFFER_RAMA-A2)") (class "Default")
      (node (ref "OUTPUT_BUFFER_RAM") (pin "3") (pinfunction "A2_3") (pintype "bidirectional"))
      (node (ref "RAM") (pin "12") (pinfunction "12_12") (pintype "passive"))
      (node (ref "RAM_LED_2") (pin "A") (pinfunction "A_A") (pintype "passive"))
    )
    (net (code "249") (name "Net-(OUTPUT_BUFFER_RAMA-A3)") (class "Default")
      (node (ref "OUTPUT_BUFFER_RAM") (pin "4") (pinfunction "A3_4") (pintype "bidirectional"))
      (node (ref "RAM") (pin "13") (pinfunction "13_13") (pintype "passive"))
      (node (ref "RAM_LED_3") (pin "A") (pinfunction "A_A") (pintype "passive"))
    )
    (net (code "250") (name "Net-(OUTPUT_BUFFER_RAMA-A4)") (class "Default")
      (node (ref "OUTPUT_BUFFER_RAM") (pin "5") (pinfunction "A4_5") (pintype "bidirectional"))
      (node (ref "RAM") (pin "15") (pinfunction "15_15") (pintype "passive"))
      (node (ref "RAM_LED_4") (pin "A") (pinfunction "A_A") (pintype "passive"))
    )
    (net (code "251") (name "Net-(OUTPUT_BUFFER_RAMA-A5)") (class "Default")
      (node (ref "OUTPUT_BUFFER_RAM") (pin "6") (pinfunction "A5_6") (pintype "bidirectional"))
      (node (ref "RAM") (pin "16") (pinfunction "16_16") (pintype "passive"))
      (node (ref "RAM_LED_5") (pin "A") (pinfunction "A_A") (pintype "passive"))
    )
    (net (code "252") (name "Net-(OUTPUT_BUFFER_RAMA-A6)") (class "Default")
      (node (ref "OUTPUT_BUFFER_RAM") (pin "7") (pinfunction "A6_7") (pintype "bidirectional"))
      (node (ref "RAM") (pin "17") (pinfunction "17_17") (pintype "passive"))
      (node (ref "RAM_LED_6") (pin "A") (pinfunction "A_A") (pintype "passive"))
    )
    (net (code "253") (name "Net-(OUTPUT_BUFFER_RAMA-A7)") (class "Default")
      (node (ref "OUTPUT_BUFFER_RAM") (pin "8") (pinfunction "A7_8") (pintype "bidirectional"))
      (node (ref "RAM") (pin "18") (pinfunction "18_18") (pintype "passive"))
      (node (ref "RAM_LED_7") (pin "A") (pinfunction "A_A") (pintype "passive"))
    )
    (net (code "254") (name "Net-(OUTPUT_BUFFER_RAMA-A8)") (class "Default")
      (node (ref "OUTPUT_BUFFER_RAM") (pin "9") (pinfunction "A8_9") (pintype "bidirectional"))
      (node (ref "RAM") (pin "19") (pinfunction "19_19") (pintype "passive"))
      (node (ref "RAM_LED_8") (pin "A") (pinfunction "A_A") (pintype "passive"))
    )
    (net (code "255") (name "Net-(OUTPUT_BUFFER_RAMA-DIR)") (class "Default")
      (node (ref "OUTPUT_BUFFER_RAM") (pin "1") (pinfunction "DIR_1") (pintype "input"))
      (node (ref "SELECTOR_STACK_") (pin "9") (pinfunction "Y3_9") (pintype "output"))
    )
    (net (code "256") (name "Net-(OUTPUT_BUFFER_REG_AA-G)") (class "Default")
      (node (ref "OUTPUT_BUFFER_REG_A") (pin "19") (pinfunction "G_19") (pintype "input"))
      (node (ref "SELECTOR_BRANCH_") (pin "11") (pinfunction "Y1_11") (pintype "output"))
    )
    (net (code "257") (name "Net-(OUT_REG_LOWERA-G1)") (class "Default")
      (node (ref "INSTRUCTION_MEMORY_2") (pin "15") (pinfunction "15_15") (pintype "passive"))
      (node (ref "OUT_REG_LOWER") (pin "10") (pinfunction "G2_10") (pintype "input"))
      (node (ref "OUT_REG_LOWER") (pin "9") (pinfunction "G1_9") (pintype "input"))
      (node (ref "OUT_REG_UPPER") (pin "10") (pinfunction "G2_10") (pintype "input"))
      (node (ref "OUT_REG_UPPER") (pin "9") (pinfunction "G1_9") (pintype "input"))
    )
    (net (code "258") (name "Net-(OUT_REG_LOWERA-Q1)") (class "Default")
      (node (ref "OUT_REG_LOWER") (pin "3") (pinfunction "Q1_3") (pintype "tri_state"))
      (node (ref "OUT_ROM_LOWER") (pin "7") (pinfunction "7_7") (pintype "passive"))
    )
    (net (code "259") (name "Net-(OUT_REG_LOWERA-Q2)") (class "Default")
      (node (ref "OUT_REG_LOWER") (pin "4") (pinfunction "Q2_4") (pintype "tri_state"))
      (node (ref "OUT_ROM_LOWER") (pin "8") (pinfunction "8_8") (pintype "passive"))
    )
    (net (code "260") (name "Net-(OUT_REG_LOWERA-Q3)") (class "Default")
      (node (ref "OUT_REG_LOWER") (pin "5") (pinfunction "Q3_5") (pintype "tri_state"))
      (node (ref "OUT_ROM_LOWER") (pin "9") (pinfunction "9_9") (pintype "passive"))
    )
    (net (code "261") (name "Net-(OUT_REG_LOWERA-Q4)") (class "Default")
      (node (ref "OUT_REG_LOWER") (pin "6") (pinfunction "Q4_6") (pintype "tri_state"))
      (node (ref "OUT_ROM_LOWER") (pin "10") (pinfunction "10_10") (pintype "passive"))
    )
    (net (code "262") (name "Net-(OUT_REG_UPPERA-Q1)") (class "Default")
      (node (ref "OUT_REG_UPPER") (pin "3") (pinfunction "Q1_3") (pintype "tri_state"))
      (node (ref "OUT_ROM_UPPER") (pin "7") (pinfunction "7_7") (pintype "passive"))
    )
    (net (code "263") (name "Net-(OUT_REG_UPPERA-Q2)") (class "Default")
      (node (ref "OUT_REG_UPPER") (pin "4") (pinfunction "Q2_4") (pintype "tri_state"))
      (node (ref "OUT_ROM_UPPER") (pin "8") (pinfunction "8_8") (pintype "passive"))
    )
    (net (code "264") (name "Net-(OUT_REG_UPPERA-Q3)") (class "Default")
      (node (ref "OUT_REG_UPPER") (pin "5") (pinfunction "Q3_5") (pintype "tri_state"))
      (node (ref "OUT_ROM_UPPER") (pin "9") (pinfunction "9_9") (pintype "passive"))
    )
    (net (code "265") (name "Net-(OUT_REG_UPPERA-Q4)") (class "Default")
      (node (ref "OUT_REG_UPPER") (pin "6") (pinfunction "Q4_6") (pintype "tri_state"))
      (node (ref "OUT_ROM_UPPER") (pin "10") (pinfunction "10_10") (pintype "passive"))
    )
    (net (code "266") (name "Net-(OUT_SEGMENT_LOWER-A)") (class "Default")
      (node (ref "OUT_ROM_LOWER") (pin "16") (pinfunction "16_16") (pintype "passive"))
      (node (ref "OUT_SEGMENT_LOWER") (pin "7") (pinfunction "A_7") (pintype "passive"))
    )
    (net (code "267") (name "Net-(OUT_SEGMENT_LOWER-B)") (class "Default")
      (node (ref "OUT_ROM_LOWER") (pin "15") (pinfunction "15_15") (pintype "passive"))
      (node (ref "OUT_SEGMENT_LOWER") (pin "6") (pinfunction "B_6") (pintype "passive"))
    )
    (net (code "268") (name "Net-(OUT_SEGMENT_LOWER-C)") (class "Default")
      (node (ref "OUT_ROM_LOWER") (pin "13") (pinfunction "13_13") (pintype "passive"))
      (node (ref "OUT_SEGMENT_LOWER") (pin "4") (pinfunction "C_4") (pintype "passive"))
    )
    (net (code "269") (name "Net-(OUT_SEGMENT_LOWER-D)") (class "Default")
      (node (ref "OUT_ROM_LOWER") (pin "12") (pinfunction "12_12") (pintype "passive"))
      (node (ref "OUT_SEGMENT_LOWER") (pin "2") (pinfunction "D_2") (pintype "passive"))
    )
    (net (code "270") (name "Net-(OUT_SEGMENT_LOWER-DP)") (class "Default")
      (node (ref "OUT_ROM_LOWER") (pin "19") (pinfunction "19_19") (pintype "passive"))
      (node (ref "OUT_SEGMENT_LOWER") (pin "5") (pinfunction "DP_5") (pintype "passive"))
    )
    (net (code "271") (name "Net-(OUT_SEGMENT_LOWER-E)") (class "Default")
      (node (ref "OUT_ROM_LOWER") (pin "11") (pinfunction "11_11") (pintype "passive"))
      (node (ref "OUT_SEGMENT_LOWER") (pin "1") (pinfunction "E_1") (pintype "passive"))
    )
    (net (code "272") (name "Net-(OUT_SEGMENT_LOWER-F)") (class "Default")
      (node (ref "OUT_ROM_LOWER") (pin "17") (pinfunction "17_17") (pintype "passive"))
      (node (ref "OUT_SEGMENT_LOWER") (pin "9") (pinfunction "F_9") (pintype "passive"))
    )
    (net (code "273") (name "Net-(OUT_SEGMENT_LOWER-G)") (class "Default")
      (node (ref "OUT_ROM_LOWER") (pin "18") (pinfunction "18_18") (pintype "passive"))
      (node (ref "OUT_SEGMENT_LOWER") (pin "10") (pinfunction "G_10") (pintype "passive"))
    )
    (net (code "274") (name "Net-(OUT_SEGMENT_UPPER-A)") (class "Default")
      (node (ref "OUT_ROM_UPPER") (pin "16") (pinfunction "16_16") (pintype "passive"))
      (node (ref "OUT_SEGMENT_UPPER") (pin "7") (pinfunction "A_7") (pintype "passive"))
    )
    (net (code "275") (name "Net-(OUT_SEGMENT_UPPER-B)") (class "Default")
      (node (ref "OUT_ROM_UPPER") (pin "15") (pinfunction "15_15") (pintype "passive"))
      (node (ref "OUT_SEGMENT_UPPER") (pin "6") (pinfunction "B_6") (pintype "passive"))
    )
    (net (code "276") (name "Net-(OUT_SEGMENT_UPPER-C)") (class "Default")
      (node (ref "OUT_ROM_UPPER") (pin "11") (pinfunction "11_11") (pintype "passive"))
      (node (ref "OUT_SEGMENT_UPPER") (pin "4") (pinfunction "C_4") (pintype "passive"))
    )
    (net (code "277") (name "Net-(OUT_SEGMENT_UPPER-D)") (class "Default")
      (node (ref "OUT_ROM_UPPER") (pin "12") (pinfunction "12_12") (pintype "passive"))
      (node (ref "OUT_SEGMENT_UPPER") (pin "2") (pinfunction "D_2") (pintype "passive"))
    )
    (net (code "278") (name "Net-(OUT_SEGMENT_UPPER-DP)") (class "Default")
      (node (ref "OUT_ROM_UPPER") (pin "17") (pinfunction "17_17") (pintype "passive"))
      (node (ref "OUT_SEGMENT_UPPER") (pin "5") (pinfunction "DP_5") (pintype "passive"))
    )
    (net (code "279") (name "Net-(OUT_SEGMENT_UPPER-E)") (class "Default")
      (node (ref "OUT_ROM_UPPER") (pin "13") (pinfunction "13_13") (pintype "passive"))
      (node (ref "OUT_SEGMENT_UPPER") (pin "1") (pinfunction "E_1") (pintype "passive"))
    )
    (net (code "280") (name "Net-(OUT_SEGMENT_UPPER-F)") (class "Default")
      (node (ref "OUT_ROM_UPPER") (pin "19") (pinfunction "19_19") (pintype "passive"))
      (node (ref "OUT_SEGMENT_UPPER") (pin "9") (pinfunction "F_9") (pintype "passive"))
    )
    (net (code "281") (name "Net-(OUT_SEGMENT_UPPER-G)") (class "Default")
      (node (ref "OUT_ROM_UPPER") (pin "18") (pinfunction "18_18") (pintype "passive"))
      (node (ref "OUT_SEGMENT_UPPER") (pin "10") (pinfunction "G_10") (pintype "passive"))
    )
    (net (code "282") (name "Net-(OVERFLOW_FLAG-C)") (class "Default")
      (node (ref "OVERFLOW_FLAG") (pin "K") (pinfunction "C_K") (pintype "passive"))
      (node (ref "R13") (pin "2") (pinfunction "2_2") (pintype "passive"))
    )
    (net (code "283") (name "Net-(PARAM_LED_1-C)") (class "Default")
      (node (ref "PARAM_LED_1") (pin "K") (pinfunction "C_K") (pintype "passive"))
      (node (ref "R71") (pin "1") (pinfunction "1_1") (pintype "passive"))
    )
    (net (code "284") (name "Net-(PARAM_LED_2-C)") (class "Default")
      (node (ref "PARAM_LED_2") (pin "K") (pinfunction "C_K") (pintype "passive"))
      (node (ref "R70") (pin "1") (pinfunction "1_1") (pintype "passive"))
    )
    (net (code "285") (name "Net-(PARAM_LED_3-C)") (class "Default")
      (node (ref "PARAM_LED_3") (pin "K") (pinfunction "C_K") (pintype "passive"))
      (node (ref "R69") (pin "1") (pinfunction "1_1") (pintype "passive"))
    )
    (net (code "286") (name "Net-(PARAM_LED_4-C)") (class "Default")
      (node (ref "PARAM_LED_4") (pin "K") (pinfunction "C_K") (pintype "passive"))
      (node (ref "R76") (pin "1") (pinfunction "1_1") (pintype "passive"))
    )
    (net (code "287") (name "Net-(PARAM_LED_5-C)") (class "Default")
      (node (ref "PARAM_LED_5") (pin "K") (pinfunction "C_K") (pintype "passive"))
      (node (ref "R72") (pin "1") (pinfunction "1_1") (pintype "passive"))
    )
    (net (code "288") (name "Net-(PARAM_LED_6-C)") (class "Default")
      (node (ref "PARAM_LED_6") (pin "K") (pinfunction "C_K") (pintype "passive"))
      (node (ref "R73") (pin "1") (pinfunction "1_1") (pintype "passive"))
    )
    (net (code "289") (name "Net-(PARAM_LED_7-C)") (class "Default")
      (node (ref "PARAM_LED_7") (pin "K") (pinfunction "C_K") (pintype "passive"))
      (node (ref "R74") (pin "1") (pinfunction "1_1") (pintype "passive"))
    )
    (net (code "290") (name "Net-(PARAM_LED_8-C)") (class "Default")
      (node (ref "PARAM_LED_8") (pin "K") (pinfunction "C_K") (pintype "passive"))
      (node (ref "R75") (pin "1") (pinfunction "1_1") (pintype "passive"))
    )
    (net (code "291") (name "Net-(PC_1-C)") (class "Default")
      (node (ref "PC_1") (pin "K") (pinfunction "C_K") (pintype "passive"))
      (node (ref "R16") (pin "1") (pinfunction "1_1") (pintype "passive"))
    )
    (net (code "292") (name "Net-(PC_2-C)") (class "Default")
      (node (ref "PC_2") (pin "K") (pinfunction "C_K") (pintype "passive"))
      (node (ref "R17") (pin "1") (pinfunction "1_1") (pintype "passive"))
    )
    (net (code "293") (name "Net-(PC_3-C)") (class "Default")
      (node (ref "PC_3") (pin "K") (pinfunction "C_K") (pintype "passive"))
      (node (ref "R18") (pin "1") (pinfunction "1_1") (pintype "passive"))
    )
    (net (code "294") (name "Net-(PC_4-C)") (class "Default")
      (node (ref "PC_4") (pin "K") (pinfunction "C_K") (pintype "passive"))
      (node (ref "R19") (pin "1") (pinfunction "1_1") (pintype "passive"))
    )
    (net (code "295") (name "Net-(PC_5-C)") (class "Default")
      (node (ref "PC_5") (pin "K") (pinfunction "C_K") (pintype "passive"))
      (node (ref "R20") (pin "1") (pinfunction "1_1") (pintype "passive"))
    )
    (net (code "296") (name "Net-(PC_6-C)") (class "Default")
      (node (ref "PC_6") (pin "K") (pinfunction "C_K") (pintype "passive"))
      (node (ref "R21") (pin "1") (pinfunction "1_1") (pintype "passive"))
    )
    (net (code "297") (name "Net-(PC_7-C)") (class "Default")
      (node (ref "PC_7") (pin "K") (pinfunction "C_K") (pintype "passive"))
      (node (ref "R22") (pin "1") (pinfunction "1_1") (pintype "passive"))
    )
    (net (code "298") (name "Net-(PC_8-C)") (class "Default")
      (node (ref "PC_8") (pin "K") (pinfunction "C_K") (pintype "passive"))
      (node (ref "R23") (pin "1") (pinfunction "1_1") (pintype "passive"))
    )
    (net (code "299") (name "Net-(POSITIVE_FLAG-C)") (class "Default")
      (node (ref "POSITIVE_FLAG") (pin "K") (pinfunction "C_K") (pintype "passive"))
      (node (ref "R12") (pin "2") (pinfunction "2_2") (pintype "passive"))
    )
    (net (code "300") (name "Net-(PROGRAM_COUNTER_LOWER-Pad15)") (class "Default")
      (node (ref "PROGRAM_COUNTER_LOWER") (pin "15") (pinfunction "15_15") (pintype "passive"))
      (node (ref "PROGRAM_COUNTER_UPPER") (pin "10") (pinfunction "10_10") (pintype "passive"))
    )
    (net (code "301") (name "Net-(RAM_ADDR_LOWERA-Q1)") (class "Default")
      (node (ref "RAM") (pin "10") (pinfunction "10_10") (pintype "passive"))
      (node (ref "RAM_ADDR_LOWER") (pin "3") (pinfunction "Q1_3") (pintype "tri_state"))
    )
    (net (code "302") (name "Net-(RAM_ADDR_LOWERA-Q2)") (class "Default")
      (node (ref "RAM") (pin "9") (pinfunction "9_9") (pintype "passive"))
      (node (ref "RAM_ADDR_LOWER") (pin "4") (pinfunction "Q2_4") (pintype "tri_state"))
    )
    (net (code "303") (name "Net-(RAM_ADDR_LOWERA-Q3)") (class "Default")
      (node (ref "RAM") (pin "8") (pinfunction "8_8") (pintype "passive"))
      (node (ref "RAM_ADDR_LOWER") (pin "5") (pinfunction "Q3_5") (pintype "tri_state"))
    )
    (net (code "304") (name "Net-(RAM_ADDR_LOWERA-Q4)") (class "Default")
      (node (ref "RAM") (pin "7") (pinfunction "7_7") (pintype "passive"))
      (node (ref "RAM_ADDR_LOWER") (pin "6") (pinfunction "Q4_6") (pintype "tri_state"))
    )
    (net (code "305") (name "Net-(RAM_ADDR_UPPERA-Q1)") (class "Default")
      (node (ref "RAM") (pin "6") (pinfunction "6_6") (pintype "passive"))
      (node (ref "RAM_ADDR_UPPER") (pin "3") (pinfunction "Q1_3") (pintype "tri_state"))
    )
    (net (code "306") (name "Net-(RAM_ADDR_UPPERA-Q2)") (class "Default")
      (node (ref "RAM") (pin "5") (pinfunction "5_5") (pintype "passive"))
      (node (ref "RAM_ADDR_UPPER") (pin "4") (pinfunction "Q2_4") (pintype "tri_state"))
    )
    (net (code "307") (name "Net-(RAM_ADDR_UPPERA-Q3)") (class "Default")
      (node (ref "RAM") (pin "4") (pinfunction "4_4") (pintype "passive"))
      (node (ref "RAM_ADDR_UPPER") (pin "5") (pinfunction "Q3_5") (pintype "tri_state"))
    )
    (net (code "308") (name "Net-(RAM_ADDR_UPPERA-Q4)") (class "Default")
      (node (ref "RAM") (pin "3") (pinfunction "3_3") (pintype "passive"))
      (node (ref "RAM_ADDR_UPPER") (pin "6") (pinfunction "Q4_6") (pintype "tri_state"))
    )
    (net (code "309") (name "Net-(RAM_LED_1-C)") (class "Default")
      (node (ref "R32") (pin "1") (pinfunction "1_1") (pintype "passive"))
      (node (ref "RAM_LED_1") (pin "K") (pinfunction "C_K") (pintype "passive"))
    )
    (net (code "310") (name "Net-(RAM_LED_2-C)") (class "Default")
      (node (ref "R33") (pin "1") (pinfunction "1_1") (pintype "passive"))
      (node (ref "RAM_LED_2") (pin "K") (pinfunction "C_K") (pintype "passive"))
    )
    (net (code "311") (name "Net-(RAM_LED_3-C)") (class "Default")
      (node (ref "R34") (pin "1") (pinfunction "1_1") (pintype "passive"))
      (node (ref "RAM_LED_3") (pin "K") (pinfunction "C_K") (pintype "passive"))
    )
    (net (code "312") (name "Net-(RAM_LED_4-C)") (class "Default")
      (node (ref "R35") (pin "1") (pinfunction "1_1") (pintype "passive"))
      (node (ref "RAM_LED_4") (pin "K") (pinfunction "C_K") (pintype "passive"))
    )
    (net (code "313") (name "Net-(RAM_LED_5-C)") (class "Default")
      (node (ref "R36") (pin "1") (pinfunction "1_1") (pintype "passive"))
      (node (ref "RAM_LED_5") (pin "K") (pinfunction "C_K") (pintype "passive"))
    )
    (net (code "314") (name "Net-(RAM_LED_6-C)") (class "Default")
      (node (ref "R37") (pin "1") (pinfunction "1_1") (pintype "passive"))
      (node (ref "RAM_LED_6") (pin "K") (pinfunction "C_K") (pintype "passive"))
    )
    (net (code "315") (name "Net-(RAM_LED_7-C)") (class "Default")
      (node (ref "R38") (pin "1") (pinfunction "1_1") (pintype "passive"))
      (node (ref "RAM_LED_7") (pin "K") (pinfunction "C_K") (pintype "passive"))
    )
    (net (code "316") (name "Net-(RAM_LED_8-C)") (class "Default")
      (node (ref "R39") (pin "1") (pinfunction "1_1") (pintype "passive"))
      (node (ref "RAM_LED_8") (pin "K") (pinfunction "C_K") (pintype "passive"))
    )
    (net (code "317") (name "Net-(REG_A_LOWERA-G1)") (class "Default")
      (node (ref "REG_A_LOWER") (pin "10") (pinfunction "G2_10") (pintype "input"))
      (node (ref "REG_A_LOWER") (pin "9") (pinfunction "G1_9") (pintype "input"))
      (node (ref "REG_A_UPPER") (pin "10") (pinfunction "G2_10") (pintype "input"))
      (node (ref "REG_A_UPPER") (pin "9") (pinfunction "G1_9") (pintype "input"))
      (node (ref "SELECTOR_BRANCH_") (pin "10") (pinfunction "Y2_10") (pintype "output"))
    )
    (net (code "318") (name "Net-(REG_CALC_LOWERA-G1)") (class "Default")
      (node (ref "REG_CALC_LOWER") (pin "10") (pinfunction "G2_10") (pintype "input"))
      (node (ref "REG_CALC_LOWER") (pin "9") (pinfunction "G1_9") (pintype "input"))
      (node (ref "REG_CALC_UPPER") (pin "10") (pinfunction "G2_10") (pintype "input"))
      (node (ref "REG_CALC_UPPER") (pin "9") (pinfunction "G1_9") (pintype "input"))
      (node (ref "SELECTOR_LOGIC_") (pin "10") (pinfunction "Y2_10") (pintype "output"))
    )
    (net (code "319") (name "Net-(SELECTOR_BRANCH_A-A)") (class "Default")
      (node (ref "INSTRUCTION_MEMORY_2") (pin "19") (pinfunction "19_19") (pintype "passive"))
      (node (ref "SELECTOR_BRANCH_") (pin "2") (pinfunction "A_2") (pintype "input"))
    )
    (net (code "320") (name "Net-(SELECTOR_BRANCH_A-B)") (class "Default")
      (node (ref "INSTRUCTION_MEMORY_2") (pin "18") (pinfunction "18_18") (pintype "passive"))
      (node (ref "SELECTOR_BRANCH_") (pin "3") (pinfunction "B_3") (pintype "input"))
    )
    (net (code "321") (name "Net-(SELECTOR_BRANCH_B-A)") (class "Default")
      (node (ref "SELECTOR_BRANCH_") (pin "14") (pinfunction "A_14") (pintype "input"))
      (node (ref "SELECTOR_INSRUCTION_LOWER") (pin "4") (pinfunction "1Y_4") (pintype "output"))
    )
    (net (code "322") (name "Net-(SELECTOR_BRANCH_B-B)") (class "Default")
      (node (ref "SELECTOR_BRANCH_") (pin "13") (pinfunction "B_13") (pintype "input"))
      (node (ref "SELECTOR_INSRUCTION_LOWER") (pin "7") (pinfunction "2Y_7") (pintype "output"))
    )
    (net (code "323") (name "Net-(SELECTOR_INSRUCTION_LOWERA-3Y)") (class "Default")
      (node (ref "SELECTOR_INSRUCTION_LOWER") (pin "9") (pinfunction "3Y_9") (pintype "output"))
      (node (ref "SELECTOR_PARAM_") (pin "14") (pinfunction "A_14") (pintype "input"))
    )
    (net (code "324") (name "Net-(SELECTOR_INSRUCTION_LOWERA-4Y)") (class "Default")
      (node (ref "SELECTOR_INSRUCTION_LOWER") (pin "12") (pinfunction "4Y_12") (pintype "output"))
      (node (ref "SELECTOR_PARAM_") (pin "13") (pinfunction "B_13") (pintype "input"))
    )
    (net (code "325") (name "Net-(SELECTOR_INSRUCTION_UPPERA-3Y)") (class "Default")
      (node (ref "SELECTOR_INSRUCTION_UPPER") (pin "9") (pinfunction "3Y_9") (pintype "output"))
      (node (ref "SELECTOR_STACK_") (pin "2") (pinfunction "A_2") (pintype "input"))
    )
    (net (code "326") (name "Net-(SELECTOR_INSRUCTION_UPPERA-4Y)") (class "Default")
      (node (ref "SELECTOR_INSRUCTION_UPPER") (pin "12") (pinfunction "4Y_12") (pintype "output"))
      (node (ref "SELECTOR_STACK_") (pin "3") (pinfunction "B_3") (pintype "input"))
    )
    (net (code "327") (name "Net-(SELECTOR_LOGIC_A-A)") (class "Default")
      (node (ref "INSTRUCTION_MEMORY_1") (pin "18") (pinfunction "18_18") (pintype "passive"))
      (node (ref "SELECTOR_LOGIC_") (pin "2") (pinfunction "A_2") (pintype "input"))
    )
    (net (code "328") (name "Net-(SELECTOR_LOGIC_A-B)") (class "Default")
      (node (ref "INSTRUCTION_MEMORY_1") (pin "19") (pinfunction "19_19") (pintype "passive"))
      (node (ref "SELECTOR_LOGIC_") (pin "3") (pinfunction "B_3") (pintype "input"))
    )
    (net (code "329") (name "Net-(SELECTOR_LOGIC_B-A)") (class "Default")
      (node (ref "INSTRUCTION_MEMORY_1") (pin "12") (pinfunction "12_12") (pintype "passive"))
      (node (ref "SELECTOR_LOGIC_") (pin "14") (pinfunction "A_14") (pintype "input"))
    )
    (net (code "330") (name "Net-(SELECTOR_LOGIC_B-B)") (class "Default")
      (node (ref "INSTRUCTION_MEMORY_1") (pin "11") (pinfunction "11_11") (pintype "passive"))
      (node (ref "SELECTOR_LOGIC_") (pin "13") (pinfunction "B_13") (pintype "input"))
    )
    (net (code "331") (name "Net-(SELECTOR_PARAM_A-A)") (class "Default")
      (node (ref "INSTRUCTION_MEMORY_2") (pin "17") (pinfunction "17_17") (pintype "passive"))
      (node (ref "SELECTOR_PARAM_") (pin "2") (pinfunction "A_2") (pintype "input"))
    )
    (net (code "332") (name "Net-(SELECTOR_PARAM_A-B)") (class "Default")
      (node (ref "INSTRUCTION_MEMORY_2") (pin "16") (pinfunction "16_16") (pintype "passive"))
      (node (ref "SELECTOR_PARAM_") (pin "3") (pinfunction "B_3") (pintype "input"))
    )
    (net (code "333") (name "Net-(SELECTOR_STACK_B-A)") (class "Default")
      (node (ref "INSTRUCTION_MEMORY_2") (pin "13") (pinfunction "13_13") (pintype "passive"))
      (node (ref "SELECTOR_STACK_") (pin "14") (pinfunction "A_14") (pintype "input"))
    )
    (net (code "334") (name "Net-(SELECTOR_STACK_B-B)") (class "Default")
      (node (ref "INSTRUCTION_MEMORY_2") (pin "12") (pinfunction "12_12") (pintype "passive"))
      (node (ref "SELECTOR_STACK_") (pin "13") (pinfunction "B_13") (pintype "input"))
    )
    (net (code "335") (name "Net-(SELECTOR_STACK_B-Y1)") (class "Default")
      (node (ref "FIFO_STACK") (pin "15") (pinfunction "15_15") (pintype "passive"))
      (node (ref "SELECTOR_STACK_") (pin "11") (pinfunction "Y1_11") (pintype "output"))
    )
    (net (code "336") (name "Net-(SELECTOR_STACK_B-Y2)") (class "Default")
      (node (ref "FIFO_STACK") (pin "1") (pinfunction "1_1") (pintype "passive"))
      (node (ref "SELECTOR_STACK_") (pin "10") (pinfunction "Y2_10") (pintype "output"))
    )
    (net (code "337") (name "Net-(STEPPER_CLOCK-DIS)") (class "Default")
      (node (ref "C2") (pin "+") (pinfunction "+_+") (pintype "passive"))
      (node (ref "R3") (pin "1") (pinfunction "1_1") (pintype "passive"))
      (node (ref "STEPPER_CLOCK") (pin "6") (pinfunction "THR_6") (pintype "input"))
      (node (ref "STEPPER_CLOCK") (pin "7") (pinfunction "DIS_7") (pintype "input"))
    )
    (net (code "338") (name "Net-(USTEP_1-C)") (class "Default")
      (node (ref "R40") (pin "2") (pinfunction "2_2") (pintype "passive"))
      (node (ref "USTEP_1") (pin "K") (pinfunction "C_K") (pintype "passive"))
    )
    (net (code "339") (name "Net-(USTEP_2-C)") (class "Default")
      (node (ref "R41") (pin "2") (pinfunction "2_2") (pintype "passive"))
      (node (ref "USTEP_2") (pin "K") (pinfunction "C_K") (pintype "passive"))
    )
    (net (code "340") (name "Net-(USTEP_3-C)") (class "Default")
      (node (ref "R42") (pin "2") (pinfunction "2_2") (pintype "passive"))
      (node (ref "USTEP_3") (pin "K") (pinfunction "C_K") (pintype "passive"))
    )
    (net (code "341") (name "Net-(USTEP_4-C)") (class "Default")
      (node (ref "R43") (pin "2") (pinfunction "2_2") (pintype "passive"))
      (node (ref "USTEP_4") (pin "K") (pinfunction "C_K") (pintype "passive"))
    )
    (net (code "342") (name "Net-(USTEP_5-C)") (class "Default")
      (node (ref "R44") (pin "2") (pinfunction "2_2") (pintype "passive"))
      (node (ref "USTEP_5") (pin "K") (pinfunction "C_K") (pintype "passive"))
    )
    (net (code "343") (name "Net-(ZERO_FLAG-C)") (class "Default")
      (node (ref "R14") (pin "2") (pinfunction "2_2") (pintype "passive"))
      (node (ref "ZERO_FLAG") (pin "K") (pinfunction "C_K") (pintype "passive"))
    )
    (net (code "344") (name "VCC") (class "Default")
      (node (ref "4_INP_OR_GATE") (pin "14") (pinfunction "VDD_14") (pintype "power_in"))
      (node (ref "AUTO_CLOCK") (pin "4") (pinfunction "R_4") (pintype "input"))
      (node (ref "AUTO_CLOCK") (pin "8") (pinfunction "V+_8") (pintype "power_in"))
      (node (ref "C3") (pin "+") (pinfunction "+_+") (pintype "passive"))
      (node (ref "CLK_MODE") (pin "2") (pinfunction "2_2") (pintype "passive"))
      (node (ref "EXTENSION") (pin "10") (pinfunction "1_10") (pintype "passive"))
      (node (ref "FIFO_STACK") (pin "28") (pinfunction "28_28") (pintype "passive"))
      (node (ref "INSTRUCTIONS_EXTENSION") (pin "14") (pinfunction "1_14") (pintype "passive"))
      (node (ref "INSTRUCTION_MEMORY_0") (pin "27") (pinfunction "27_27") (pintype "passive"))
      (node (ref "INSTRUCTION_MEMORY_0") (pin "28") (pinfunction "28_28") (pintype "passive"))
      (node (ref "INSTRUCTION_MEMORY_1") (pin "27") (pinfunction "27_27") (pintype "passive"))
      (node (ref "INSTRUCTION_MEMORY_1") (pin "28") (pinfunction "28_28") (pintype "passive"))
      (node (ref "INSTRUCTION_MEMORY_2") (pin "27") (pinfunction "27_27") (pintype "passive"))
      (node (ref "INSTRUCTION_MEMORY_2") (pin "28") (pinfunction "28_28") (pintype "passive"))
      (node (ref "KEYBOARD") (pin "1") (pinfunction "1_1") (pintype "passive"))
      (node (ref "KEYBOARD_ASCII_TABLE") (pin "27") (pinfunction "27_27") (pintype "passive"))
      (node (ref "KEYBOARD_ASCII_TABLE") (pin "28") (pinfunction "28_28") (pintype "passive"))
      (node (ref "KEYBOARD_SHIFT_LOWER") (pin "10") (pinfunction "SCL_10") (pintype "input"))
      (node (ref "KEYBOARD_SHIFT_UPPER") (pin "10") (pinfunction "SCL_10") (pintype "input"))
      (node (ref "MEMORY") (pin "27") (pinfunction "27_27") (pintype "passive"))
      (node (ref "MEMORY") (pin "28") (pinfunction "28_28") (pintype "passive"))
      (node (ref "MICRO_COUNTER_LOWER") (pin "10") (pinfunction "10_10") (pintype "passive"))
      (node (ref "MICRO_COUNTER_LOWER") (pin "16") (pinfunction "16_16") (pintype "passive"))
      (node (ref "MICRO_COUNTER_LOWER") (pin "7") (pinfunction "7_7") (pintype "passive"))
      (node (ref "MICRO_COUNTER_UPPER") (pin "16") (pinfunction "16_16") (pintype "passive"))
      (node (ref "MICRO_COUNTER_UPPER") (pin "7") (pinfunction "7_7") (pintype "passive"))
      (node (ref "OUTPUT_BUFFER_CALC_REG") (pin "1") (pinfunction "DIR_1") (pintype "input"))
      (node (ref "OUTPUT_BUFFER_INSTRUCTION") (pin "1") (pinfunction "DIR_1") (pintype "input"))
      (node (ref "OUTPUT_BUFFER_MEMORY") (pin "1") (pinfunction "DIR_1") (pintype "input"))
      (node (ref "OUTPUT_BUFFER_PARAM_REG") (pin "1") (pinfunction "DIR_1") (pintype "input"))
      (node (ref "OUTPUT_BUFFER_PC") (pin "1") (pinfunction "DIR_1") (pintype "input"))
      (node (ref "OUTPUT_BUFFER_REG_A") (pin "1") (pinfunction "DIR_1") (pintype "input"))
      (node (ref "OUT_ROM_LOWER") (pin "27") (pinfunction "27_27") (pintype "passive"))
      (node (ref "OUT_ROM_LOWER") (pin "28") (pinfunction "28_28") (pintype "passive"))
      (node (ref "OUT_ROM_UPPER") (pin "27") (pinfunction "27_27") (pintype "passive"))
      (node (ref "OUT_ROM_UPPER") (pin "28") (pinfunction "28_28") (pintype "passive"))
      (node (ref "PROGRAM_COUNTER_LOWER") (pin "16") (pinfunction "16_16") (pintype "passive"))
      (node (ref "PROGRAM_COUNTER_LOWER") (pin "7") (pinfunction "7_7") (pintype "passive"))
      (node (ref "PROGRAM_COUNTER_UPPER") (pin "16") (pinfunction "16_16") (pintype "passive"))
      (node (ref "PROGRAM_COUNTER_UPPER") (pin "7") (pinfunction "7_7") (pintype "passive"))
      (node (ref "R1") (pin "1") (pinfunction "1_1") (pintype "passive"))
      (node (ref "R2") (pin "1") (pinfunction "1_1") (pintype "passive"))
      (node (ref "R3") (pin "2") (pinfunction "2_2") (pintype "passive"))
      (node (ref "R80") (pin "2") (pinfunction "2_2") (pintype "passive"))
      (node (ref "RAM") (pin "28") (pinfunction "28_28") (pintype "passive"))
      (node (ref "RESET_REGS") (pin "1") (pinfunction "S_1") (pintype "passive"))
      (node (ref "STEPPER_CLOCK") (pin "8") (pinfunction "V+_8") (pintype "power_in"))
      (node (ref "X1") (pin "2") (pinfunction "1_2") (pintype "passive"))
      (node (ref "ZERO_POS_FLAG_IDENTIFIER") (pin "14") (pinfunction "+UB_14") (pintype "power_in"))
    )
    (net (code "345") (name "unconnected-(AUTO_CLOCK-CV-Pad5)") (class "Default")
      (node (ref "AUTO_CLOCK") (pin "5") (pinfunction "CV_5") (pintype "input"))
    )
    (net (code "346") (name "unconnected-(CLK_TRIGGER-P1-Pad4)") (class "Default")
      (node (ref "CLK_TRIGGER") (pin "4") (pinfunction "P1_4") (pintype "passive"))
    )
    (net (code "347") (name "unconnected-(CLK_TRIGGER-S-Pad1)") (class "Default")
      (node (ref "CLK_TRIGGER") (pin "1") (pinfunction "S_1") (pintype "passive"))
    )
    (net (code "348") (name "unconnected-(FIFO_STACK-Pad8)") (class "Default")
      (node (ref "FIFO_STACK") (pin "8") (pinfunction "8_8") (pintype "passive"))
    )
    (net (code "349") (name "unconnected-(FIFO_STACK-Pad13)") (class "Default")
      (node (ref "FIFO_STACK") (pin "13") (pinfunction "13_13") (pintype "passive"))
    )
    (net (code "350") (name "unconnected-(FIFO_STACK-Pad20)") (class "Default")
      (node (ref "FIFO_STACK") (pin "20") (pinfunction "20_20") (pintype "passive"))
    )
    (net (code "351") (name "unconnected-(FIFO_STACK-Pad21)") (class "Default")
      (node (ref "FIFO_STACK") (pin "21") (pinfunction "21_21") (pintype "passive"))
    )
    (net (code "352") (name "unconnected-(FIFO_STACK-Pad22)") (class "Default")
      (node (ref "FIFO_STACK") (pin "22") (pinfunction "22_22") (pintype "passive"))
    )
    (net (code "353") (name "unconnected-(FIFO_STACK-Pad23)") (class "Default")
      (node (ref "FIFO_STACK") (pin "23") (pinfunction "23_23") (pintype "passive"))
    )
    (net (code "354") (name "unconnected-(FREQUENCY-PadA)") (class "Default")
      (node (ref "FREQUENCY") (pin "A") (pinfunction "A_A") (pintype "passive"))
    )
    (net (code "355") (name "unconnected-(INSTRUCTION_MEMORY_0-Pad1)") (class "Default")
      (node (ref "INSTRUCTION_MEMORY_0") (pin "1") (pinfunction "1_1") (pintype "passive"))
    )
    (net (code "356") (name "unconnected-(INSTRUCTION_MEMORY_0-Pad26)") (class "Default")
      (node (ref "INSTRUCTION_MEMORY_0") (pin "26") (pinfunction "26_26") (pintype "passive"))
    )
    (net (code "357") (name "unconnected-(INSTRUCTION_MEMORY_1-Pad1)") (class "Default")
      (node (ref "INSTRUCTION_MEMORY_1") (pin "1") (pinfunction "1_1") (pintype "passive"))
    )
    (net (code "358") (name "unconnected-(INSTRUCTION_MEMORY_1-Pad26)") (class "Default")
      (node (ref "INSTRUCTION_MEMORY_1") (pin "26") (pinfunction "26_26") (pintype "passive"))
    )
    (net (code "359") (name "unconnected-(INSTRUCTION_MEMORY_2-Pad1)") (class "Default")
      (node (ref "INSTRUCTION_MEMORY_2") (pin "1") (pinfunction "1_1") (pintype "passive"))
    )
    (net (code "360") (name "unconnected-(INSTRUCTION_MEMORY_2-Pad26)") (class "Default")
      (node (ref "INSTRUCTION_MEMORY_2") (pin "26") (pinfunction "26_26") (pintype "passive"))
    )
    (net (code "361") (name "unconnected-(KEYBOARD_ASCII_TABLE-Pad1)") (class "Default")
      (node (ref "KEYBOARD_ASCII_TABLE") (pin "1") (pinfunction "1_1") (pintype "passive"))
    )
    (net (code "362") (name "unconnected-(KEYBOARD_ASCII_TABLE-Pad26)") (class "Default")
      (node (ref "KEYBOARD_ASCII_TABLE") (pin "26") (pinfunction "26_26") (pintype "passive"))
    )
    (net (code "363") (name "unconnected-(KEYBOARD_SHIFT_LOWERA-QC-Pad2)") (class "Default")
      (node (ref "KEYBOARD_SHIFT_LOWER") (pin "2") (pinfunction "QC_2") (pintype "tri_state"))
    )
    (net (code "364") (name "unconnected-(KEYBOARD_SHIFT_LOWERA-QD-Pad3)") (class "Default")
      (node (ref "KEYBOARD_SHIFT_LOWER") (pin "3") (pinfunction "QD_3") (pintype "tri_state"))
    )
    (net (code "365") (name "unconnected-(KEYBOARD_SHIFT_LOWERA-QE-Pad4)") (class "Default")
      (node (ref "KEYBOARD_SHIFT_LOWER") (pin "4") (pinfunction "QE_4") (pintype "tri_state"))
    )
    (net (code "366") (name "unconnected-(KEYBOARD_SHIFT_LOWERA-QF-Pad5)") (class "Default")
      (node (ref "KEYBOARD_SHIFT_LOWER") (pin "5") (pinfunction "QF_5") (pintype "tri_state"))
    )
    (net (code "367") (name "unconnected-(KEYBOARD_SHIFT_LOWERA-QG-Pad6)") (class "Default")
      (node (ref "KEYBOARD_SHIFT_LOWER") (pin "6") (pinfunction "QG_6") (pintype "tri_state"))
    )
    (net (code "368") (name "unconnected-(KEYBOARD_SHIFT_LOWERA-QH*-Pad9)") (class "Default")
      (node (ref "KEYBOARD_SHIFT_LOWER") (pin "9") (pinfunction "QH*_9") (pintype "tri_state"))
    )
    (net (code "369") (name "unconnected-(KEYBOARD_SHIFT_LOWERA-QH-Pad7)") (class "Default")
      (node (ref "KEYBOARD_SHIFT_LOWER") (pin "7") (pinfunction "QH_7") (pintype "tri_state"))
    )
    (net (code "370") (name "unconnected-(KEYBOARD_SHIFT_UPPERA-QA-Pad15)") (class "Default")
      (node (ref "KEYBOARD_SHIFT_UPPER") (pin "15") (pinfunction "QA_15") (pintype "tri_state"))
    )
    (net (code "371") (name "unconnected-(KEYBOARD_SHIFT_UPPERA-QB-Pad1)") (class "Default")
      (node (ref "KEYBOARD_SHIFT_UPPER") (pin "1") (pinfunction "QB_1") (pintype "tri_state"))
    )
    (net (code "372") (name "unconnected-(MEMORY-Pad1)") (class "Default")
      (node (ref "MEMORY") (pin "1") (pinfunction "1_1") (pintype "passive"))
    )
    (net (code "373") (name "unconnected-(MEMORY-Pad26)") (class "Default")
      (node (ref "MEMORY") (pin "26") (pinfunction "26_26") (pintype "passive"))
    )
    (net (code "374") (name "unconnected-(MICRO_COUNTER_UPPER-Pad4)") (class "Default")
      (node (ref "MICRO_COUNTER_UPPER") (pin "4") (pinfunction "4_4") (pintype "passive"))
    )
    (net (code "375") (name "unconnected-(MICRO_COUNTER_UPPER-Pad5)") (class "Default")
      (node (ref "MICRO_COUNTER_UPPER") (pin "5") (pinfunction "5_5") (pintype "passive"))
    )
    (net (code "376") (name "unconnected-(MICRO_COUNTER_UPPER-Pad6)") (class "Default")
      (node (ref "MICRO_COUNTER_UPPER") (pin "6") (pinfunction "6_6") (pintype "passive"))
    )
    (net (code "377") (name "unconnected-(MICRO_COUNTER_UPPER-Pad11)") (class "Default")
      (node (ref "MICRO_COUNTER_UPPER") (pin "11") (pinfunction "11_11") (pintype "passive"))
    )
    (net (code "378") (name "unconnected-(MICRO_COUNTER_UPPER-Pad12)") (class "Default")
      (node (ref "MICRO_COUNTER_UPPER") (pin "12") (pinfunction "12_12") (pintype "passive"))
    )
    (net (code "379") (name "unconnected-(MICRO_COUNTER_UPPER-Pad13)") (class "Default")
      (node (ref "MICRO_COUNTER_UPPER") (pin "13") (pinfunction "13_13") (pintype "passive"))
    )
    (net (code "380") (name "unconnected-(MICRO_COUNTER_UPPER-Pad15)") (class "Default")
      (node (ref "MICRO_COUNTER_UPPER") (pin "15") (pinfunction "15_15") (pintype "passive"))
    )
    (net (code "381") (name "unconnected-(OUT_ROM_LOWER-Pad1)") (class "Default")
      (node (ref "OUT_ROM_LOWER") (pin "1") (pinfunction "1_1") (pintype "passive"))
    )
    (net (code "382") (name "unconnected-(OUT_ROM_LOWER-Pad26)") (class "Default")
      (node (ref "OUT_ROM_LOWER") (pin "26") (pinfunction "26_26") (pintype "passive"))
    )
    (net (code "383") (name "unconnected-(OUT_ROM_UPPER-Pad1)") (class "Default")
      (node (ref "OUT_ROM_UPPER") (pin "1") (pinfunction "1_1") (pintype "passive"))
    )
    (net (code "384") (name "unconnected-(OUT_ROM_UPPER-Pad26)") (class "Default")
      (node (ref "OUT_ROM_UPPER") (pin "26") (pinfunction "26_26") (pintype "passive"))
    )
    (net (code "385") (name "unconnected-(PROGRAM_COUNTER_UPPER-Pad15)") (class "Default")
      (node (ref "PROGRAM_COUNTER_UPPER") (pin "15") (pinfunction "15_15") (pintype "passive"))
    )
    (net (code "386") (name "unconnected-(RESET_PC-P-Pad3)") (class "Default")
      (node (ref "RESET_PC") (pin "3") (pinfunction "P_3") (pintype "passive"))
    )
    (net (code "387") (name "unconnected-(RESET_PC-S1-Pad2)") (class "Default")
      (node (ref "RESET_PC") (pin "2") (pinfunction "S1_2") (pintype "passive"))
    )
    (net (code "388") (name "unconnected-(RESET_REGS-P-Pad3)") (class "Default")
      (node (ref "RESET_REGS") (pin "3") (pinfunction "P_3") (pintype "passive"))
    )
    (net (code "389") (name "unconnected-(RESET_REGS-S1-Pad2)") (class "Default")
      (node (ref "RESET_REGS") (pin "2") (pinfunction "S1_2") (pintype "passive"))
    )
    (net (code "390") (name "unconnected-(SELECTOR_BRANCH_B-Y0-Pad12)") (class "Default")
      (node (ref "SELECTOR_BRANCH_") (pin "12") (pinfunction "Y0_12") (pintype "output"))
    )
    (net (code "391") (name "unconnected-(SELECTOR_LOGIC_A-Y0-Pad4)") (class "Default")
      (node (ref "SELECTOR_LOGIC_") (pin "4") (pinfunction "Y0_4") (pintype "output"))
    )
    (net (code "392") (name "unconnected-(SELECTOR_LOGIC_B-Y0-Pad12)") (class "Default")
      (node (ref "SELECTOR_LOGIC_") (pin "12") (pinfunction "Y0_12") (pintype "output"))
    )
    (net (code "393") (name "unconnected-(SELECTOR_PARAM_A-Y0-Pad4)") (class "Default")
      (node (ref "SELECTOR_PARAM_") (pin "4") (pinfunction "Y0_4") (pintype "output"))
    )
    (net (code "394") (name "unconnected-(SELECTOR_PARAM_B-Y0-Pad12)") (class "Default")
      (node (ref "SELECTOR_PARAM_") (pin "12") (pinfunction "Y0_12") (pintype "output"))
    )
    (net (code "395") (name "unconnected-(SELECTOR_STACK_A-Y0-Pad4)") (class "Default")
      (node (ref "SELECTOR_STACK_") (pin "4") (pinfunction "Y0_4") (pintype "output"))
    )
    (net (code "396") (name "unconnected-(SELECTOR_STACK_B-Y0-Pad12)") (class "Default")
      (node (ref "SELECTOR_STACK_") (pin "12") (pinfunction "Y0_12") (pintype "output"))
    )
    (net (code "397") (name "unconnected-(STEPPER_CLOCK-CV-Pad5)") (class "Default")
      (node (ref "STEPPER_CLOCK") (pin "5") (pinfunction "CV_5") (pintype "input"))
    )
    (net (code "398") (name "unconnected-(STEPPER_CLOCK-R-Pad4)") (class "Default")
      (node (ref "STEPPER_CLOCK") (pin "4") (pinfunction "R_4") (pintype "input"))
    )
    (net (code "399") (name "unconnected-(X1C-1-Pad3)") (class "Default")
      (node (ref "X1") (pin "3") (pinfunction "1_3") (pintype "passive"))
    )
  )
)
